# MKRFOX1200-LargePrototype.net
KiCad netlist of a schematic drawn in EAGLE
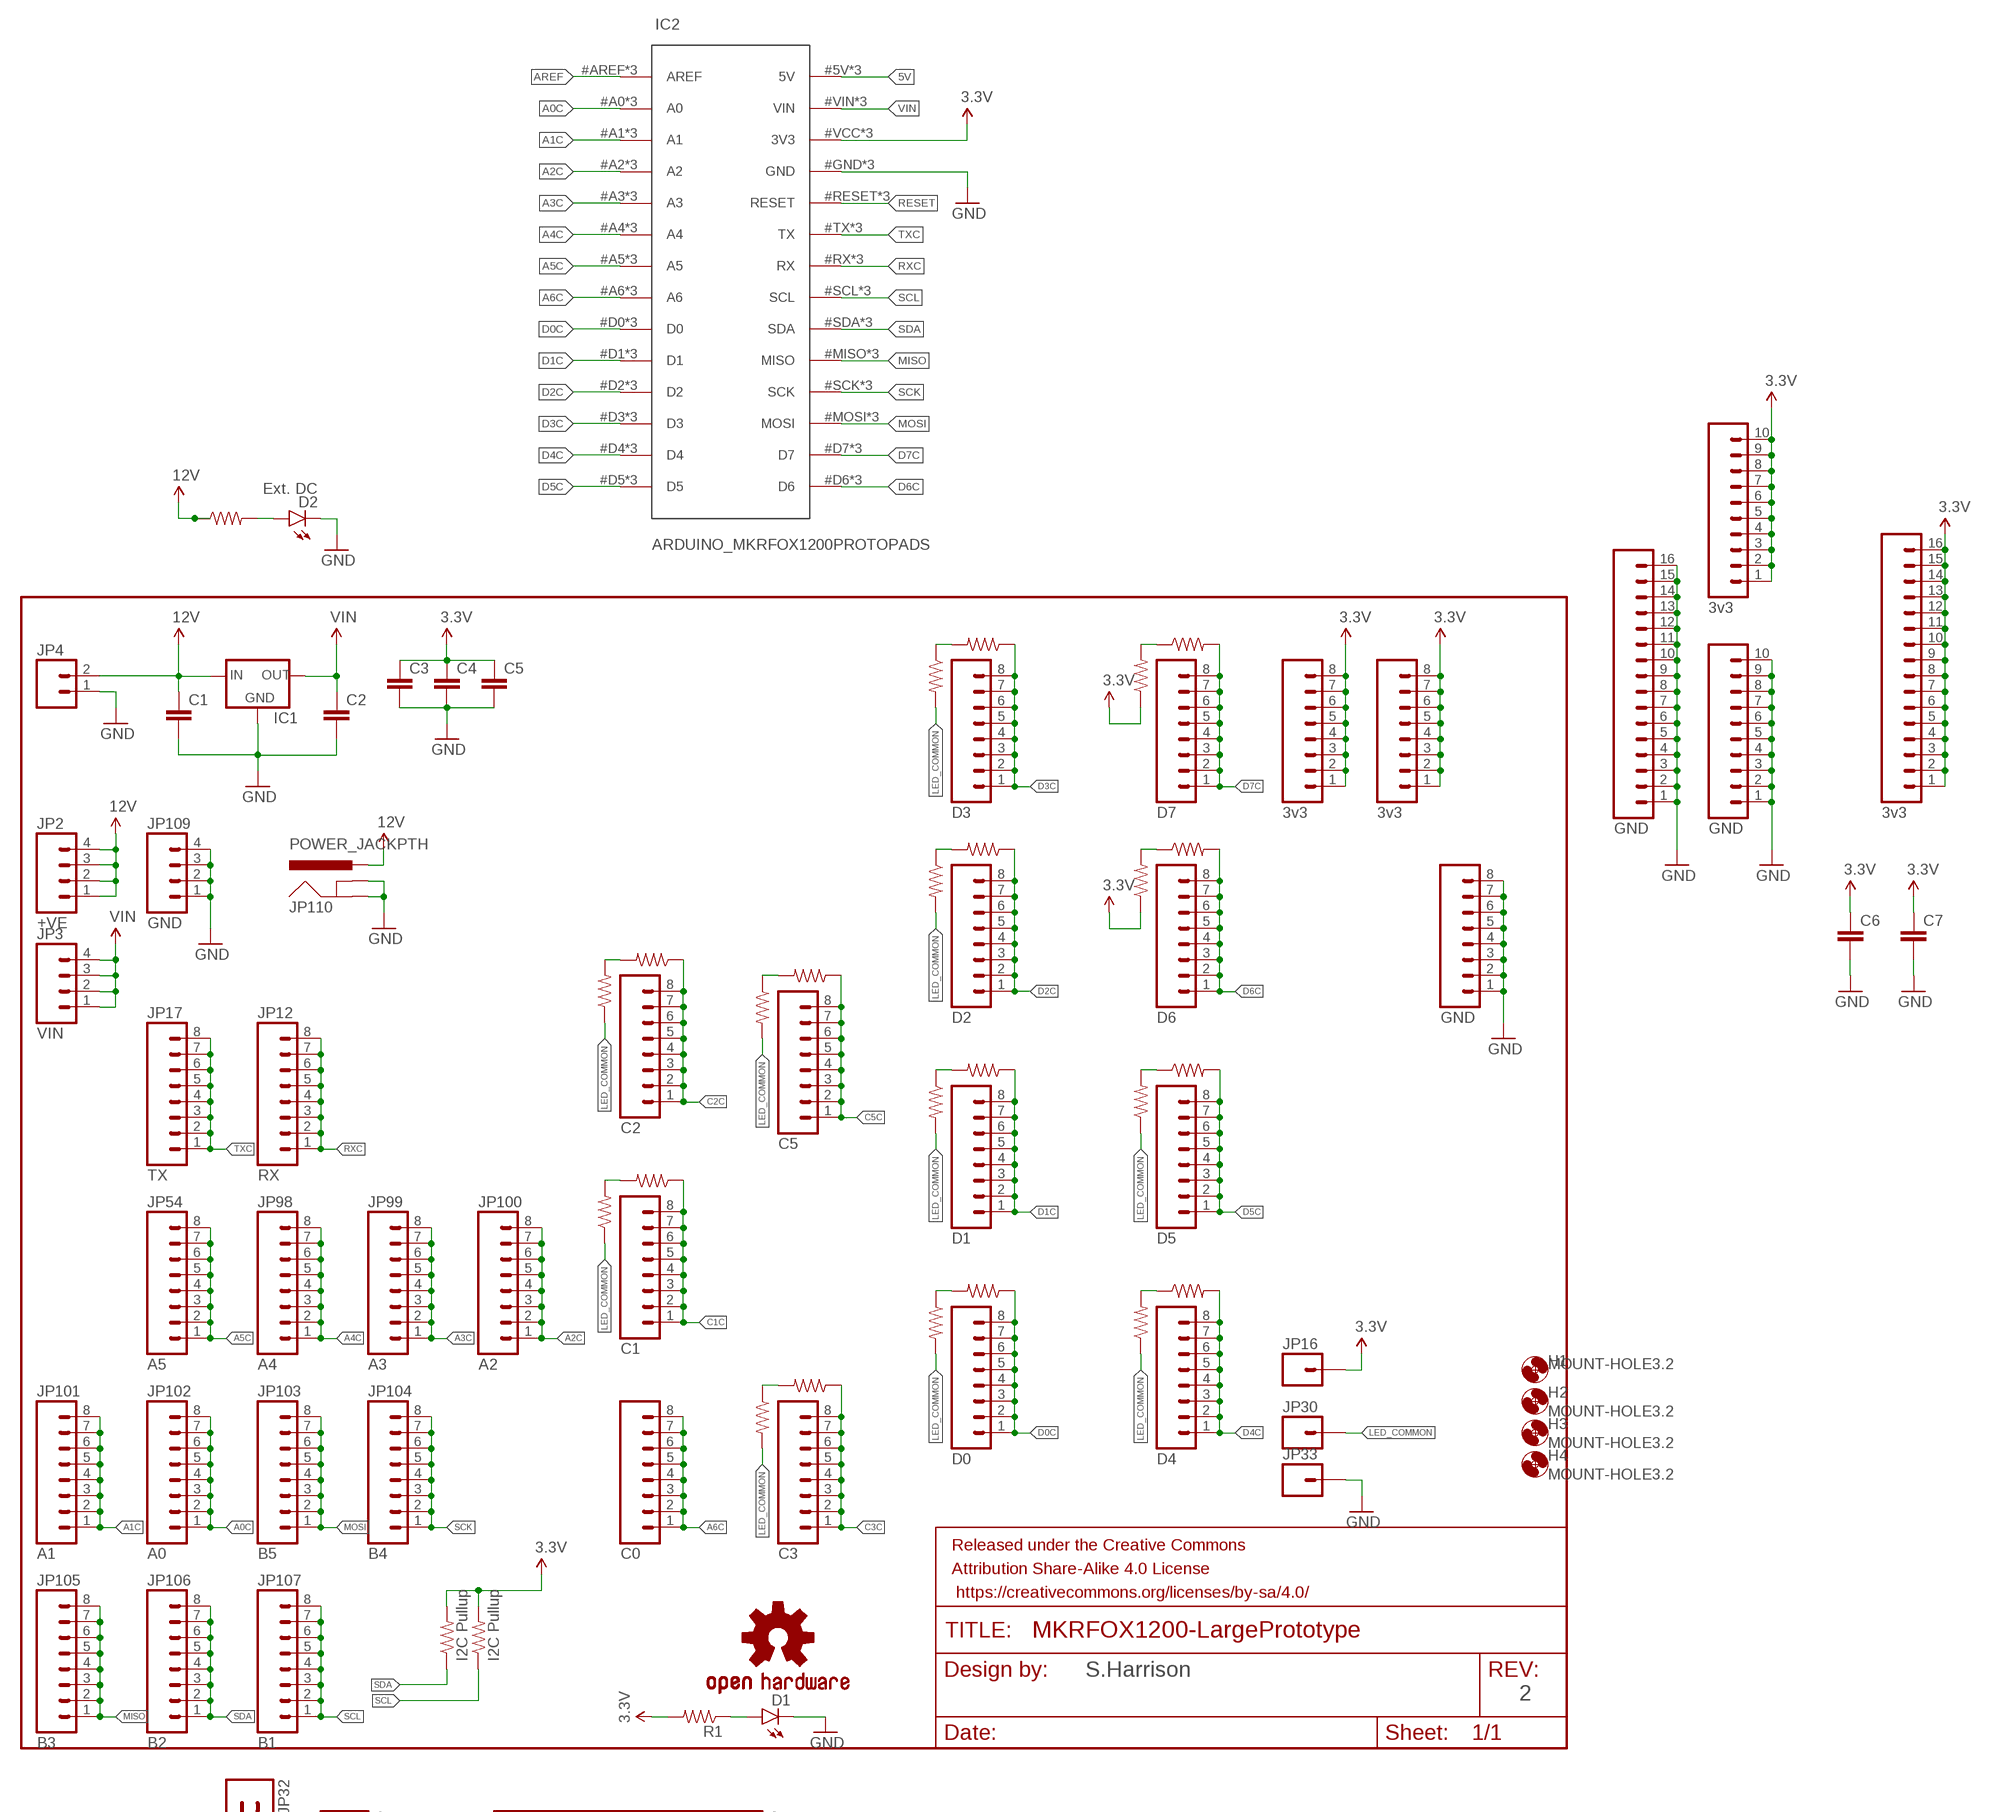
[diagram p0: schematic, sheet 1, part 1 of 2]
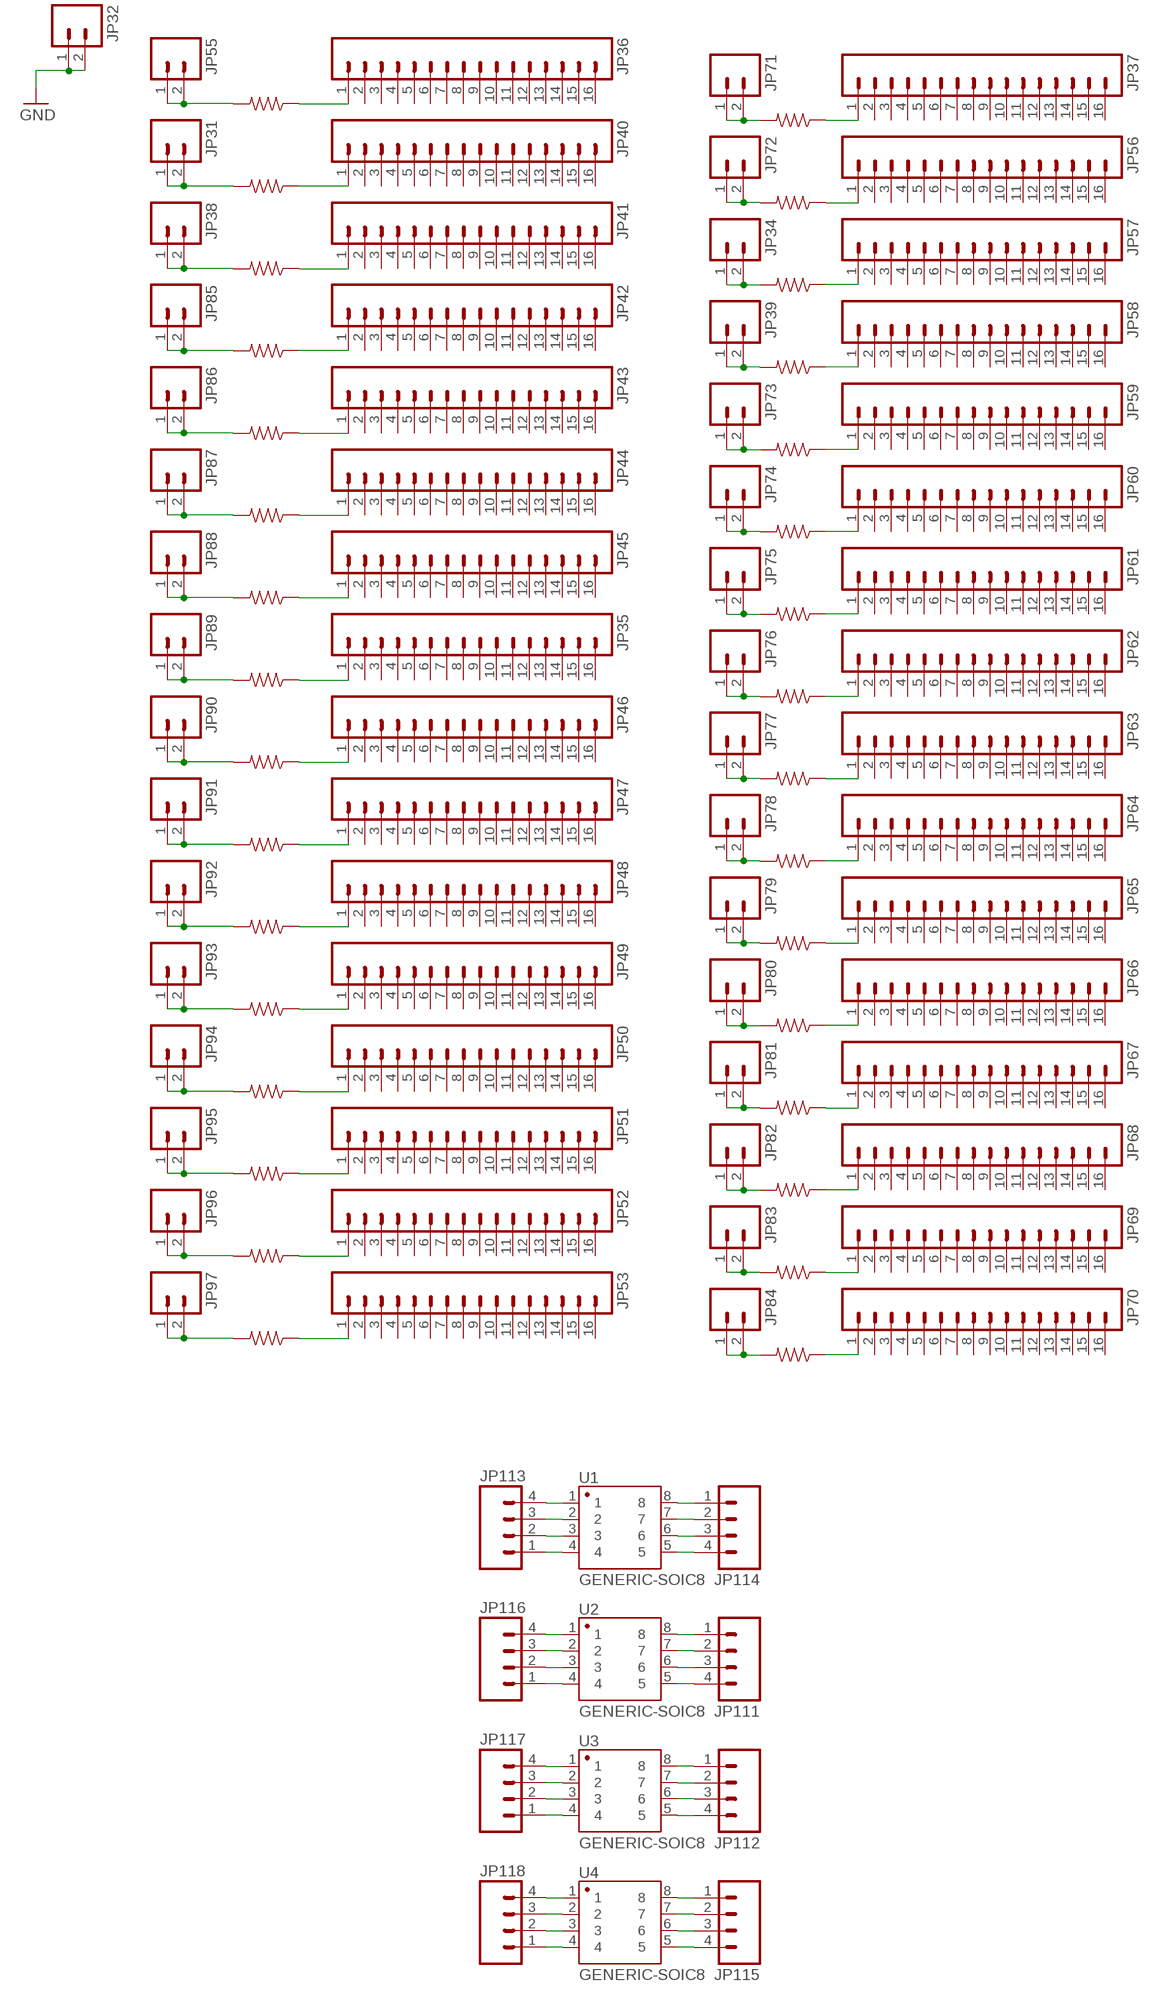
[diagram p1: schematic, sheet 1, part 2 of 2]

(export (version "E")
  (design (tool "Eeschema 10.0.6"))
  (components
    (comp (ref "3V1")
      (value "3v3")
      (footprint "eagle-import:1X08_ROUND")
      (libsource (lib "eagle-import") (part "M08"))
    )
    (comp (ref "3V3")
      (value "3v3")
      (footprint "eagle-import:1X08_ROUND")
      (libsource (lib "eagle-import") (part "M08"))
    )
    (comp (ref "C1")
      (value "1UF-25V-10%(0805)\"")
      (footprint "eagle-import:0805-CAP")
      (libsource (lib "eagle-import") (part "1UF-25V-10%(0805){dblquote}"))
    )
    (comp (ref "C2")
      (value "1UF-25V-10%(0805)\"")
      (footprint "eagle-import:0805-CAP")
      (libsource (lib "eagle-import") (part "1UF-25V-10%(0805){dblquote}"))
    )
    (comp (ref "C3")
      (value "1UF-25V-10%(0805)\"")
      (footprint "eagle-import:0805-CAP")
      (libsource (lib "eagle-import") (part "1UF-25V-10%(0805){dblquote}"))
    )
    (comp (ref "C4")
      (value "1UF-25V-10%(0805)\"")
      (footprint "eagle-import:0805-CAP")
      (libsource (lib "eagle-import") (part "1UF-25V-10%(0805){dblquote}"))
    )
    (comp (ref "C5")
      (value "1UF-25V-10%(0805)\"")
      (footprint "eagle-import:0805-CAP")
      (libsource (lib "eagle-import") (part "1UF-25V-10%(0805){dblquote}"))
    )
    (comp (ref "C6")
      (value "1UF-25V-10%(0805)\"")
      (footprint "eagle-import:0805-CAP")
      (libsource (lib "eagle-import") (part "1UF-25V-10%(0805){dblquote}"))
    )
    (comp (ref "C7")
      (value "1UF-25V-10%(0805)\"")
      (footprint "eagle-import:0805-CAP")
      (libsource (lib "eagle-import") (part "1UF-25V-10%(0805){dblquote}"))
    )
    (comp (ref "D1")
      (value "LED1206-BOTTOM")
      (footprint "eagle-import:LED-1206-BOTTOM")
      (libsource (lib "eagle-import") (part "LED1206-BOTTOM"))
    )
    (comp (ref "D2")
      (value "Ext. DC")
      (footprint "eagle-import:LED-1206")
      (libsource (lib "eagle-import") (part "LED-RED1206"))
    )
    (comp (ref "FRAME1")
      (value "FRAME-LETTER")
      (footprint "eagle-import:CREATIVE_COMMONS")
      (libsource (lib "eagle-import") (part "FRAME-LETTER"))
    )
    (comp (ref "H1")
      (value "MOUNT-HOLE3.2")
      (footprint "eagle-import:3,2")
      (libsource (lib "eagle-import") (part "MOUNT-HOLE3.2"))
    )
    (comp (ref "H2")
      (value "MOUNT-HOLE3.2")
      (footprint "eagle-import:3,2")
      (libsource (lib "eagle-import") (part "MOUNT-HOLE3.2"))
    )
    (comp (ref "H3")
      (value "MOUNT-HOLE3.2")
      (footprint "eagle-import:3,2")
      (libsource (lib "eagle-import") (part "MOUNT-HOLE3.2"))
    )
    (comp (ref "H4")
      (value "MOUNT-HOLE3.2")
      (footprint "eagle-import:3,2")
      (libsource (lib "eagle-import") (part "MOUNT-HOLE3.2"))
    )
    (comp (ref "IC1")
      (value "78XXS")
      (footprint "eagle-import:78XXS")
      (libsource (lib "eagle-import") (part "78XXS"))
    )
    (comp (ref "IC2")
      (value "ARDUINO_MKRFOX1200PROTOPADS")
      (footprint "eagle-import:ARDUINO_MKRFOX1200_PROTOPADS")
      (libsource (lib "eagle-import") (part "ARDUINO_MKRFOX1200PROTOPADS"))
    )
    (comp (ref "JP1")
      (value "D7")
      (footprint "eagle-import:1X08_ROUND")
      (libsource (lib "eagle-import") (part "M08"))
    )
    (comp (ref "JP2")
      (value "+VE")
      (footprint "eagle-import:1X04")
      (libsource (lib "eagle-import") (part "M04PTH"))
    )
    (comp (ref "JP3")
      (value "VIN")
      (footprint "eagle-import:1X04")
      (libsource (lib "eagle-import") (part "M04PTH"))
    )
    (comp (ref "JP4")
      (value "M025MM")
      (footprint "eagle-import:SCREWTERMINAL-5MM-2")
      (libsource (lib "eagle-import") (part "M025MM"))
    )
    (comp (ref "JP5")
      (value "3v3")
      (footprint "eagle-import:1X10")
      (libsource (lib "eagle-import") (part "M10SILK_FEMALE_PTH"))
    )
    (comp (ref "JP7")
      (value "D6")
      (footprint "eagle-import:1X08_ROUND")
      (libsource (lib "eagle-import") (part "M08"))
    )
    (comp (ref "JP10")
      (value "D5")
      (footprint "eagle-import:1X08_ROUND")
      (libsource (lib "eagle-import") (part "M08"))
    )
    (comp (ref "JP11")
      (value "GND")
      (footprint "eagle-import:1X10")
      (libsource (lib "eagle-import") (part "M10SILK_FEMALE_PTH"))
    )
    (comp (ref "JP12")
      (value "RX")
      (footprint "eagle-import:1X08_ROUND")
      (libsource (lib "eagle-import") (part "M08"))
    )
    (comp (ref "JP13")
      (value "3v3")
      (footprint "eagle-import:1X16")
      (libsource (lib "eagle-import") (part "M16PTH"))
    )
    (comp (ref "JP14")
      (value "GND")
      (footprint "eagle-import:1X16")
      (libsource (lib "eagle-import") (part "M16PTH"))
    )
    (comp (ref "JP16")
      (value "M01PTH")
      (footprint "eagle-import:1X01")
      (libsource (lib "eagle-import") (part "M01PTH"))
    )
    (comp (ref "JP17")
      (value "TX")
      (footprint "eagle-import:1X08_ROUND")
      (libsource (lib "eagle-import") (part "M08"))
    )
    (comp (ref "JP18")
      (value "D4")
      (footprint "eagle-import:1X08_ROUND")
      (libsource (lib "eagle-import") (part "M08"))
    )
    (comp (ref "JP19")
      (value "D3")
      (footprint "eagle-import:1X08_ROUND")
      (libsource (lib "eagle-import") (part "M08"))
    )
    (comp (ref "JP20")
      (value "D2")
      (footprint "eagle-import:1X08_ROUND")
      (libsource (lib "eagle-import") (part "M08"))
    )
    (comp (ref "JP21")
      (value "D1")
      (footprint "eagle-import:1X08_ROUND")
      (libsource (lib "eagle-import") (part "M08"))
    )
    (comp (ref "JP22")
      (value "D0")
      (footprint "eagle-import:1X08_ROUND")
      (libsource (lib "eagle-import") (part "M08"))
    )
    (comp (ref "JP23")
      (value "GND")
      (footprint "eagle-import:1X08_ROUND")
      (libsource (lib "eagle-import") (part "M08"))
    )
    (comp (ref "JP24")
      (value "C5")
      (footprint "eagle-import:1X08_ROUND")
      (libsource (lib "eagle-import") (part "M08"))
    )
    (comp (ref "JP26")
      (value "C3")
      (footprint "eagle-import:1X08_ROUND")
      (libsource (lib "eagle-import") (part "M08"))
    )
    (comp (ref "JP27")
      (value "C2")
      (footprint "eagle-import:1X08_ROUND")
      (libsource (lib "eagle-import") (part "M08"))
    )
    (comp (ref "JP28")
      (value "C1")
      (footprint "eagle-import:1X08_ROUND")
      (libsource (lib "eagle-import") (part "M08"))
    )
    (comp (ref "JP29")
      (value "C0")
      (footprint "eagle-import:1X08_ROUND")
      (libsource (lib "eagle-import") (part "M08"))
    )
    (comp (ref "JP30")
      (value "M01PTH")
      (footprint "eagle-import:1X01")
      (libsource (lib "eagle-import") (part "M01PTH"))
    )
    (comp (ref "JP31")
      (value "M02PTH")
      (footprint "eagle-import:1X02")
      (libsource (lib "eagle-import") (part "M02PTH"))
    )
    (comp (ref "JP32")
      (value "M02PTH")
      (footprint "eagle-import:1X02")
      (libsource (lib "eagle-import") (part "M02PTH"))
    )
    (comp (ref "JP33")
      (value "M01PTH")
      (footprint "eagle-import:1X01")
      (libsource (lib "eagle-import") (part "M01PTH"))
    )
    (comp (ref "JP34")
      (value "M02PTH")
      (footprint "eagle-import:1X02")
      (libsource (lib "eagle-import") (part "M02PTH"))
    )
    (comp (ref "JP35")
      (value "M161X16_NO_SILK")
      (footprint "eagle-import:1X16_NO_SILK")
      (libsource (lib "eagle-import") (part "M161X16_NO_SILK"))
    )
    (comp (ref "JP36")
      (value "M161X16_NO_SILK")
      (footprint "eagle-import:1X16_NO_SILK")
      (libsource (lib "eagle-import") (part "M161X16_NO_SILK"))
    )
    (comp (ref "JP37")
      (value "M161X16_NO_SILK")
      (footprint "eagle-import:1X16_NO_SILK")
      (libsource (lib "eagle-import") (part "M161X16_NO_SILK"))
    )
    (comp (ref "JP38")
      (value "M02PTH")
      (footprint "eagle-import:1X02")
      (libsource (lib "eagle-import") (part "M02PTH"))
    )
    (comp (ref "JP39")
      (value "M02PTH")
      (footprint "eagle-import:1X02")
      (libsource (lib "eagle-import") (part "M02PTH"))
    )
    (comp (ref "JP40")
      (value "M161X16_NO_SILK")
      (footprint "eagle-import:1X16_NO_SILK")
      (libsource (lib "eagle-import") (part "M161X16_NO_SILK"))
    )
    (comp (ref "JP41")
      (value "M161X16_NO_SILK")
      (footprint "eagle-import:1X16_NO_SILK")
      (libsource (lib "eagle-import") (part "M161X16_NO_SILK"))
    )
    (comp (ref "JP42")
      (value "M161X16_NO_SILK")
      (footprint "eagle-import:1X16_NO_SILK")
      (libsource (lib "eagle-import") (part "M161X16_NO_SILK"))
    )
    (comp (ref "JP43")
      (value "M161X16_NO_SILK")
      (footprint "eagle-import:1X16_NO_SILK")
      (libsource (lib "eagle-import") (part "M161X16_NO_SILK"))
    )
    (comp (ref "JP44")
      (value "M161X16_NO_SILK")
      (footprint "eagle-import:1X16_NO_SILK")
      (libsource (lib "eagle-import") (part "M161X16_NO_SILK"))
    )
    (comp (ref "JP45")
      (value "M161X16_NO_SILK")
      (footprint "eagle-import:1X16_NO_SILK")
      (libsource (lib "eagle-import") (part "M161X16_NO_SILK"))
    )
    (comp (ref "JP46")
      (value "M161X16_NO_SILK")
      (footprint "eagle-import:1X16_NO_SILK")
      (libsource (lib "eagle-import") (part "M161X16_NO_SILK"))
    )
    (comp (ref "JP47")
      (value "M161X16_NO_SILK")
      (footprint "eagle-import:1X16_NO_SILK")
      (libsource (lib "eagle-import") (part "M161X16_NO_SILK"))
    )
    (comp (ref "JP48")
      (value "M161X16_NO_SILK")
      (footprint "eagle-import:1X16_NO_SILK")
      (libsource (lib "eagle-import") (part "M161X16_NO_SILK"))
    )
    (comp (ref "JP49")
      (value "M161X16_NO_SILK")
      (footprint "eagle-import:1X16_NO_SILK")
      (libsource (lib "eagle-import") (part "M161X16_NO_SILK"))
    )
    (comp (ref "JP50")
      (value "M161X16_NO_SILK")
      (footprint "eagle-import:1X16_NO_SILK")
      (libsource (lib "eagle-import") (part "M161X16_NO_SILK"))
    )
    (comp (ref "JP51")
      (value "M161X16_NO_SILK")
      (footprint "eagle-import:1X16_NO_SILK")
      (libsource (lib "eagle-import") (part "M161X16_NO_SILK"))
    )
    (comp (ref "JP52")
      (value "M161X16_NO_SILK")
      (footprint "eagle-import:1X16_NO_SILK")
      (libsource (lib "eagle-import") (part "M161X16_NO_SILK"))
    )
    (comp (ref "JP53")
      (value "M161X16_NO_SILK")
      (footprint "eagle-import:1X16_NO_SILK")
      (libsource (lib "eagle-import") (part "M161X16_NO_SILK"))
    )
    (comp (ref "JP54")
      (value "A5")
      (footprint "eagle-import:1X08_ROUND")
      (libsource (lib "eagle-import") (part "M08"))
    )
    (comp (ref "JP55")
      (value "M02PTH")
      (footprint "eagle-import:1X02")
      (libsource (lib "eagle-import") (part "M02PTH"))
    )
    (comp (ref "JP56")
      (value "M161X16_NO_SILK")
      (footprint "eagle-import:1X16_NO_SILK")
      (libsource (lib "eagle-import") (part "M161X16_NO_SILK"))
    )
    (comp (ref "JP57")
      (value "M161X16_NO_SILK")
      (footprint "eagle-import:1X16_NO_SILK")
      (libsource (lib "eagle-import") (part "M161X16_NO_SILK"))
    )
    (comp (ref "JP58")
      (value "M161X16_NO_SILK")
      (footprint "eagle-import:1X16_NO_SILK")
      (libsource (lib "eagle-import") (part "M161X16_NO_SILK"))
    )
    (comp (ref "JP59")
      (value "M161X16_NO_SILK")
      (footprint "eagle-import:1X16_NO_SILK")
      (libsource (lib "eagle-import") (part "M161X16_NO_SILK"))
    )
    (comp (ref "JP60")
      (value "M161X16_NO_SILK")
      (footprint "eagle-import:1X16_NO_SILK")
      (libsource (lib "eagle-import") (part "M161X16_NO_SILK"))
    )
    (comp (ref "JP61")
      (value "M161X16_NO_SILK")
      (footprint "eagle-import:1X16_NO_SILK")
      (libsource (lib "eagle-import") (part "M161X16_NO_SILK"))
    )
    (comp (ref "JP62")
      (value "M161X16_NO_SILK")
      (footprint "eagle-import:1X16_NO_SILK")
      (libsource (lib "eagle-import") (part "M161X16_NO_SILK"))
    )
    (comp (ref "JP63")
      (value "M161X16_NO_SILK")
      (footprint "eagle-import:1X16_NO_SILK")
      (libsource (lib "eagle-import") (part "M161X16_NO_SILK"))
    )
    (comp (ref "JP64")
      (value "M161X16_NO_SILK")
      (footprint "eagle-import:1X16_NO_SILK")
      (libsource (lib "eagle-import") (part "M161X16_NO_SILK"))
    )
    (comp (ref "JP65")
      (value "M161X16_NO_SILK")
      (footprint "eagle-import:1X16_NO_SILK")
      (libsource (lib "eagle-import") (part "M161X16_NO_SILK"))
    )
    (comp (ref "JP66")
      (value "M161X16_NO_SILK")
      (footprint "eagle-import:1X16_NO_SILK")
      (libsource (lib "eagle-import") (part "M161X16_NO_SILK"))
    )
    (comp (ref "JP67")
      (value "M161X16_NO_SILK")
      (footprint "eagle-import:1X16_NO_SILK")
      (libsource (lib "eagle-import") (part "M161X16_NO_SILK"))
    )
    (comp (ref "JP68")
      (value "M161X16_NO_SILK")
      (footprint "eagle-import:1X16_NO_SILK")
      (libsource (lib "eagle-import") (part "M161X16_NO_SILK"))
    )
    (comp (ref "JP69")
      (value "M161X16_NO_SILK")
      (footprint "eagle-import:1X16_NO_SILK")
      (libsource (lib "eagle-import") (part "M161X16_NO_SILK"))
    )
    (comp (ref "JP70")
      (value "M161X16_NO_SILK")
      (footprint "eagle-import:1X16_NO_SILK")
      (libsource (lib "eagle-import") (part "M161X16_NO_SILK"))
    )
    (comp (ref "JP71")
      (value "M02PTH")
      (footprint "eagle-import:1X02")
      (libsource (lib "eagle-import") (part "M02PTH"))
    )
    (comp (ref "JP72")
      (value "M02PTH")
      (footprint "eagle-import:1X02")
      (libsource (lib "eagle-import") (part "M02PTH"))
    )
    (comp (ref "JP73")
      (value "M02PTH")
      (footprint "eagle-import:1X02")
      (libsource (lib "eagle-import") (part "M02PTH"))
    )
    (comp (ref "JP74")
      (value "M02PTH")
      (footprint "eagle-import:1X02")
      (libsource (lib "eagle-import") (part "M02PTH"))
    )
    (comp (ref "JP75")
      (value "M02PTH")
      (footprint "eagle-import:1X02")
      (libsource (lib "eagle-import") (part "M02PTH"))
    )
    (comp (ref "JP76")
      (value "M02PTH")
      (footprint "eagle-import:1X02")
      (libsource (lib "eagle-import") (part "M02PTH"))
    )
    (comp (ref "JP77")
      (value "M02PTH")
      (footprint "eagle-import:1X02")
      (libsource (lib "eagle-import") (part "M02PTH"))
    )
    (comp (ref "JP78")
      (value "M02PTH")
      (footprint "eagle-import:1X02")
      (libsource (lib "eagle-import") (part "M02PTH"))
    )
    (comp (ref "JP79")
      (value "M02PTH")
      (footprint "eagle-import:1X02")
      (libsource (lib "eagle-import") (part "M02PTH"))
    )
    (comp (ref "JP80")
      (value "M02PTH")
      (footprint "eagle-import:1X02")
      (libsource (lib "eagle-import") (part "M02PTH"))
    )
    (comp (ref "JP81")
      (value "M02PTH")
      (footprint "eagle-import:1X02")
      (libsource (lib "eagle-import") (part "M02PTH"))
    )
    (comp (ref "JP82")
      (value "M02PTH")
      (footprint "eagle-import:1X02")
      (libsource (lib "eagle-import") (part "M02PTH"))
    )
    (comp (ref "JP83")
      (value "M02PTH")
      (footprint "eagle-import:1X02")
      (libsource (lib "eagle-import") (part "M02PTH"))
    )
    (comp (ref "JP84")
      (value "M02PTH")
      (footprint "eagle-import:1X02")
      (libsource (lib "eagle-import") (part "M02PTH"))
    )
    (comp (ref "JP85")
      (value "M02PTH")
      (footprint "eagle-import:1X02")
      (libsource (lib "eagle-import") (part "M02PTH"))
    )
    (comp (ref "JP86")
      (value "M02PTH")
      (footprint "eagle-import:1X02")
      (libsource (lib "eagle-import") (part "M02PTH"))
    )
    (comp (ref "JP87")
      (value "M02PTH")
      (footprint "eagle-import:1X02")
      (libsource (lib "eagle-import") (part "M02PTH"))
    )
    (comp (ref "JP88")
      (value "M02PTH")
      (footprint "eagle-import:1X02")
      (libsource (lib "eagle-import") (part "M02PTH"))
    )
    (comp (ref "JP89")
      (value "M02PTH")
      (footprint "eagle-import:1X02")
      (libsource (lib "eagle-import") (part "M02PTH"))
    )
    (comp (ref "JP90")
      (value "M02PTH")
      (footprint "eagle-import:1X02")
      (libsource (lib "eagle-import") (part "M02PTH"))
    )
    (comp (ref "JP91")
      (value "M02PTH")
      (footprint "eagle-import:1X02")
      (libsource (lib "eagle-import") (part "M02PTH"))
    )
    (comp (ref "JP92")
      (value "M02PTH")
      (footprint "eagle-import:1X02")
      (libsource (lib "eagle-import") (part "M02PTH"))
    )
    (comp (ref "JP93")
      (value "M02PTH")
      (footprint "eagle-import:1X02")
      (libsource (lib "eagle-import") (part "M02PTH"))
    )
    (comp (ref "JP94")
      (value "M02PTH")
      (footprint "eagle-import:1X02")
      (libsource (lib "eagle-import") (part "M02PTH"))
    )
    (comp (ref "JP95")
      (value "M02PTH")
      (footprint "eagle-import:1X02")
      (libsource (lib "eagle-import") (part "M02PTH"))
    )
    (comp (ref "JP96")
      (value "M02PTH")
      (footprint "eagle-import:1X02")
      (libsource (lib "eagle-import") (part "M02PTH"))
    )
    (comp (ref "JP97")
      (value "M02PTH")
      (footprint "eagle-import:1X02")
      (libsource (lib "eagle-import") (part "M02PTH"))
    )
    (comp (ref "JP98")
      (value "A4")
      (footprint "eagle-import:1X08_ROUND")
      (libsource (lib "eagle-import") (part "M08"))
    )
    (comp (ref "JP99")
      (value "A3")
      (footprint "eagle-import:1X08_ROUND")
      (libsource (lib "eagle-import") (part "M08"))
    )
    (comp (ref "JP100")
      (value "A2")
      (footprint "eagle-import:1X08_ROUND")
      (libsource (lib "eagle-import") (part "M08"))
    )
    (comp (ref "JP101")
      (value "A1")
      (footprint "eagle-import:1X08_ROUND")
      (libsource (lib "eagle-import") (part "M08"))
    )
    (comp (ref "JP102")
      (value "A0")
      (footprint "eagle-import:1X08_ROUND")
      (libsource (lib "eagle-import") (part "M08"))
    )
    (comp (ref "JP103")
      (value "B5")
      (footprint "eagle-import:1X08_ROUND")
      (libsource (lib "eagle-import") (part "M08"))
    )
    (comp (ref "JP104")
      (value "B4")
      (footprint "eagle-import:1X08_ROUND")
      (libsource (lib "eagle-import") (part "M08"))
    )
    (comp (ref "JP105")
      (value "B3")
      (footprint "eagle-import:1X08_ROUND")
      (libsource (lib "eagle-import") (part "M08"))
    )
    (comp (ref "JP106")
      (value "B2")
      (footprint "eagle-import:1X08_ROUND")
      (libsource (lib "eagle-import") (part "M08"))
    )
    (comp (ref "JP107")
      (value "B1")
      (footprint "eagle-import:1X08_ROUND")
      (libsource (lib "eagle-import") (part "M08"))
    )
    (comp (ref "JP109")
      (value "GND")
      (footprint "eagle-import:1X04")
      (libsource (lib "eagle-import") (part "M04PTH"))
    )
    (comp (ref "JP110")
      (value "POWER_JACKPTH")
      (footprint "eagle-import:POWER_JACK_PTH")
      (libsource (lib "eagle-import") (part "POWER_JACKPTH"))
    )
    (comp (ref "JP111")
      (value "M04NO_SILK_ALL_ROUND")
      (footprint "eagle-import:1X04_NO_SILK_ALL_ROUND")
      (libsource (lib "eagle-import") (part "M04NO_SILK_ALL_ROUND"))
    )
    (comp (ref "JP112")
      (value "M04NO_SILK_ALL_ROUND")
      (footprint "eagle-import:1X04_NO_SILK_ALL_ROUND")
      (libsource (lib "eagle-import") (part "M04NO_SILK_ALL_ROUND"))
    )
    (comp (ref "JP113")
      (value "M04NO_SILK_ALL_ROUND")
      (footprint "eagle-import:1X04_NO_SILK_ALL_ROUND")
      (libsource (lib "eagle-import") (part "M04NO_SILK_ALL_ROUND"))
    )
    (comp (ref "JP114")
      (value "M04NO_SILK_ALL_ROUND")
      (footprint "eagle-import:1X04_NO_SILK_ALL_ROUND")
      (libsource (lib "eagle-import") (part "M04NO_SILK_ALL_ROUND"))
    )
    (comp (ref "JP115")
      (value "M04NO_SILK_ALL_ROUND")
      (footprint "eagle-import:1X04_NO_SILK_ALL_ROUND")
      (libsource (lib "eagle-import") (part "M04NO_SILK_ALL_ROUND"))
    )
    (comp (ref "JP116")
      (value "M04NO_SILK_ALL_ROUND")
      (footprint "eagle-import:1X04_NO_SILK_ALL_ROUND")
      (libsource (lib "eagle-import") (part "M04NO_SILK_ALL_ROUND"))
    )
    (comp (ref "JP117")
      (value "M04NO_SILK_ALL_ROUND")
      (footprint "eagle-import:1X04_NO_SILK_ALL_ROUND")
      (libsource (lib "eagle-import") (part "M04NO_SILK_ALL_ROUND"))
    )
    (comp (ref "JP118")
      (value "M04NO_SILK_ALL_ROUND")
      (footprint "eagle-import:1X04_NO_SILK_ALL_ROUND")
      (libsource (lib "eagle-import") (part "M04NO_SILK_ALL_ROUND"))
    )
    (comp (ref "LOGO3")
      (value "OSHW-LOGOM")
      (footprint "eagle-import:OSHW-LOGO-M")
      (libsource (lib "eagle-import") (part "OSHW-LOGOM"))
    )
    (comp (ref "R1")
      (value "RESISTOR1206")
      (footprint "eagle-import:1206")
      (libsource (lib "eagle-import") (part "RESISTOR1206"))
    )
    (comp (ref "R2")
      (value "RESISTOR1206")
      (footprint "eagle-import:1206")
      (libsource (lib "eagle-import") (part "RESISTOR1206"))
    )
    (comp (ref "R3")
      (value "RESISTOR1206")
      (footprint "eagle-import:1206")
      (libsource (lib "eagle-import") (part "RESISTOR1206"))
    )
    (comp (ref "R4")
      (value "RESISTOR1206")
      (footprint "eagle-import:1206")
      (libsource (lib "eagle-import") (part "RESISTOR1206"))
    )
    (comp (ref "R5")
      (value "RESISTOR1206")
      (footprint "eagle-import:1206")
      (libsource (lib "eagle-import") (part "RESISTOR1206"))
    )
    (comp (ref "R6")
      (value "RESISTOR1206")
      (footprint "eagle-import:1206")
      (libsource (lib "eagle-import") (part "RESISTOR1206"))
    )
    (comp (ref "R7")
      (value "RESISTOR1206")
      (footprint "eagle-import:1206")
      (libsource (lib "eagle-import") (part "RESISTOR1206"))
    )
    (comp (ref "R8")
      (value "RESISTOR1206")
      (footprint "eagle-import:1206")
      (libsource (lib "eagle-import") (part "RESISTOR1206"))
    )
    (comp (ref "R9")
      (value "RESISTOR1206")
      (footprint "eagle-import:1206")
      (libsource (lib "eagle-import") (part "RESISTOR1206"))
    )
    (comp (ref "R10")
      (value "RESISTOR1206")
      (footprint "eagle-import:1206")
      (libsource (lib "eagle-import") (part "RESISTOR1206"))
    )
    (comp (ref "R11")
      (value "RESISTOR1206")
      (footprint "eagle-import:1206")
      (libsource (lib "eagle-import") (part "RESISTOR1206"))
    )
    (comp (ref "R12")
      (value "RESISTOR1206")
      (footprint "eagle-import:1206")
      (libsource (lib "eagle-import") (part "RESISTOR1206"))
    )
    (comp (ref "R13")
      (value "RESISTOR1206")
      (footprint "eagle-import:1206")
      (libsource (lib "eagle-import") (part "RESISTOR1206"))
    )
    (comp (ref "R14")
      (value "RESISTOR1206")
      (footprint "eagle-import:1206")
      (libsource (lib "eagle-import") (part "RESISTOR1206"))
    )
    (comp (ref "R15")
      (value "RESISTOR1206")
      (footprint "eagle-import:1206")
      (libsource (lib "eagle-import") (part "RESISTOR1206"))
    )
    (comp (ref "R16")
      (value "RESISTOR1206")
      (footprint "eagle-import:1206")
      (libsource (lib "eagle-import") (part "RESISTOR1206"))
    )
    (comp (ref "R17")
      (value "RESISTOR1206")
      (footprint "eagle-import:1206")
      (libsource (lib "eagle-import") (part "RESISTOR1206"))
    )
    (comp (ref "R18")
      (value "RESISTOR1206")
      (footprint "eagle-import:1206")
      (libsource (lib "eagle-import") (part "RESISTOR1206"))
    )
    (comp (ref "R19")
      (value "RESISTOR1206")
      (footprint "eagle-import:1206")
      (libsource (lib "eagle-import") (part "RESISTOR1206"))
    )
    (comp (ref "R22")
      (value "RESISTOR1206")
      (footprint "eagle-import:1206")
      (libsource (lib "eagle-import") (part "RESISTOR1206"))
    )
    (comp (ref "R23")
      (value "RESISTOR1206")
      (footprint "eagle-import:1206")
      (libsource (lib "eagle-import") (part "RESISTOR1206"))
    )
    (comp (ref "R24")
      (value "RESISTOR1206")
      (footprint "eagle-import:1206")
      (libsource (lib "eagle-import") (part "RESISTOR1206"))
    )
    (comp (ref "R25")
      (value "RESISTOR1206")
      (footprint "eagle-import:1206")
      (libsource (lib "eagle-import") (part "RESISTOR1206"))
    )
    (comp (ref "R26")
      (value "RESISTOR1206")
      (footprint "eagle-import:1206")
      (libsource (lib "eagle-import") (part "RESISTOR1206"))
    )
    (comp (ref "R27")
      (value "RESISTOR1206")
      (footprint "eagle-import:1206")
      (libsource (lib "eagle-import") (part "RESISTOR1206"))
    )
    (comp (ref "R28")
      (value "RESISTOR1206")
      (footprint "eagle-import:1206")
      (libsource (lib "eagle-import") (part "RESISTOR1206"))
    )
    (comp (ref "R30")
      (value "RESISTOR1206")
      (footprint "eagle-import:1206")
      (libsource (lib "eagle-import") (part "RESISTOR1206"))
    )
    (comp (ref "R31")
      (value "RESISTOR1206")
      (footprint "eagle-import:1206")
      (libsource (lib "eagle-import") (part "RESISTOR1206"))
    )
    (comp (ref "R32")
      (value "RESISTOR1206")
      (footprint "eagle-import:1206")
      (libsource (lib "eagle-import") (part "RESISTOR1206"))
    )
    (comp (ref "R33")
      (value "RESISTOR1206")
      (footprint "eagle-import:1206")
      (libsource (lib "eagle-import") (part "RESISTOR1206"))
    )
    (comp (ref "R34")
      (value "RESISTOR1206")
      (footprint "eagle-import:1206")
      (libsource (lib "eagle-import") (part "RESISTOR1206"))
    )
    (comp (ref "R35")
      (value "RESISTOR1206")
      (footprint "eagle-import:1206")
      (libsource (lib "eagle-import") (part "RESISTOR1206"))
    )
    (comp (ref "R36")
      (value "RESISTOR1206")
      (footprint "eagle-import:1206")
      (libsource (lib "eagle-import") (part "RESISTOR1206"))
    )
    (comp (ref "R37")
      (value "RESISTOR1206")
      (footprint "eagle-import:1206")
      (libsource (lib "eagle-import") (part "RESISTOR1206"))
    )
    (comp (ref "R38")
      (value "RESISTOR1206")
      (footprint "eagle-import:1206")
      (libsource (lib "eagle-import") (part "RESISTOR1206"))
    )
    (comp (ref "R39")
      (value "RESISTOR1206")
      (footprint "eagle-import:1206")
      (libsource (lib "eagle-import") (part "RESISTOR1206"))
    )
    (comp (ref "R40")
      (value "RESISTOR1206")
      (footprint "eagle-import:1206")
      (libsource (lib "eagle-import") (part "RESISTOR1206"))
    )
    (comp (ref "R41")
      (value "RESISTOR1206")
      (footprint "eagle-import:1206")
      (libsource (lib "eagle-import") (part "RESISTOR1206"))
    )
    (comp (ref "R42")
      (value "RESISTOR1206")
      (footprint "eagle-import:1206")
      (libsource (lib "eagle-import") (part "RESISTOR1206"))
    )
    (comp (ref "R43")
      (value "RESISTOR1206")
      (footprint "eagle-import:1206")
      (libsource (lib "eagle-import") (part "RESISTOR1206"))
    )
    (comp (ref "R44")
      (value "RESISTOR1206")
      (footprint "eagle-import:1206")
      (libsource (lib "eagle-import") (part "RESISTOR1206"))
    )
    (comp (ref "R45")
      (value "RESISTOR1206")
      (footprint "eagle-import:1206")
      (libsource (lib "eagle-import") (part "RESISTOR1206"))
    )
    (comp (ref "R46")
      (value "RESISTOR1206")
      (footprint "eagle-import:1206")
      (libsource (lib "eagle-import") (part "RESISTOR1206"))
    )
    (comp (ref "R47")
      (value "RESISTOR1206")
      (footprint "eagle-import:1206")
      (libsource (lib "eagle-import") (part "RESISTOR1206"))
    )
    (comp (ref "R48")
      (value "RESISTOR1206")
      (footprint "eagle-import:1206")
      (libsource (lib "eagle-import") (part "RESISTOR1206"))
    )
    (comp (ref "R49")
      (value "RESISTOR1206")
      (footprint "eagle-import:1206")
      (libsource (lib "eagle-import") (part "RESISTOR1206"))
    )
    (comp (ref "R50")
      (value "RESISTOR1206")
      (footprint "eagle-import:1206")
      (libsource (lib "eagle-import") (part "RESISTOR1206"))
    )
    (comp (ref "R51")
      (value "RESISTOR1206")
      (footprint "eagle-import:1206")
      (libsource (lib "eagle-import") (part "RESISTOR1206"))
    )
    (comp (ref "R52")
      (value "RESISTOR1206")
      (footprint "eagle-import:1206")
      (libsource (lib "eagle-import") (part "RESISTOR1206"))
    )
    (comp (ref "R53")
      (value "RESISTOR1206")
      (footprint "eagle-import:1206")
      (libsource (lib "eagle-import") (part "RESISTOR1206"))
    )
    (comp (ref "R54")
      (value "RESISTOR1206")
      (footprint "eagle-import:1206")
      (libsource (lib "eagle-import") (part "RESISTOR1206"))
    )
    (comp (ref "R55")
      (value "RESISTOR1206")
      (footprint "eagle-import:1206")
      (libsource (lib "eagle-import") (part "RESISTOR1206"))
    )
    (comp (ref "R56")
      (value "RESISTOR1206")
      (footprint "eagle-import:1206")
      (libsource (lib "eagle-import") (part "RESISTOR1206"))
    )
    (comp (ref "R57")
      (value "RESISTOR1206")
      (footprint "eagle-import:1206")
      (libsource (lib "eagle-import") (part "RESISTOR1206"))
    )
    (comp (ref "R58")
      (value "RESISTOR1206")
      (footprint "eagle-import:1206")
      (libsource (lib "eagle-import") (part "RESISTOR1206"))
    )
    (comp (ref "R59")
      (value "RESISTOR1206")
      (footprint "eagle-import:1206")
      (libsource (lib "eagle-import") (part "RESISTOR1206"))
    )
    (comp (ref "R60")
      (value "RESISTOR1206")
      (footprint "eagle-import:1206")
      (libsource (lib "eagle-import") (part "RESISTOR1206"))
    )
    (comp (ref "R61")
      (value "RESISTOR1206")
      (footprint "eagle-import:1206")
      (libsource (lib "eagle-import") (part "RESISTOR1206"))
    )
    (comp (ref "R64")
      (value "I2C Pullup")
      (footprint "eagle-import:1206")
      (libsource (lib "eagle-import") (part "RESISTOR1206"))
    )
    (comp (ref "R65")
      (value "I2C Pullup")
      (footprint "eagle-import:1206")
      (libsource (lib "eagle-import") (part "RESISTOR1206"))
    )
    (comp (ref "U1")
      (value "GENERIC-SOIC8")
      (footprint "eagle-import:SO08-UNIVERSAL")
      (libsource (lib "eagle-import") (part "GENERIC-SOIC8"))
    )
    (comp (ref "U2")
      (value "GENERIC-SOIC8")
      (footprint "eagle-import:SO08-UNIVERSAL")
      (libsource (lib "eagle-import") (part "GENERIC-SOIC8"))
    )
    (comp (ref "U3")
      (value "GENERIC-SOIC8")
      (footprint "eagle-import:SO08-UNIVERSAL")
      (libsource (lib "eagle-import") (part "GENERIC-SOIC8"))
    )
    (comp (ref "U4")
      (value "GENERIC-SOIC8")
      (footprint "eagle-import:SO08-UNIVERSAL")
      (libsource (lib "eagle-import") (part "GENERIC-SOIC8"))
    )
  )
  (nets
    (net (code "1") (name "3.3V") (class "Default")
      (node (ref "3V1") (pin "1") (pinfunction "1_1") (pintype "passive"))
      (node (ref "3V1") (pin "2") (pinfunction "2_2") (pintype "passive"))
      (node (ref "3V1") (pin "3") (pinfunction "3_3") (pintype "passive"))
      (node (ref "3V1") (pin "4") (pinfunction "4_4") (pintype "passive"))
      (node (ref "3V1") (pin "5") (pinfunction "5_5") (pintype "passive"))
      (node (ref "3V1") (pin "6") (pinfunction "6_6") (pintype "passive"))
      (node (ref "3V1") (pin "7") (pinfunction "7_7") (pintype "passive"))
      (node (ref "3V1") (pin "8") (pinfunction "8_8") (pintype "passive"))
      (node (ref "3V3") (pin "1") (pinfunction "1_1") (pintype "passive"))
      (node (ref "3V3") (pin "2") (pinfunction "2_2") (pintype "passive"))
      (node (ref "3V3") (pin "3") (pinfunction "3_3") (pintype "passive"))
      (node (ref "3V3") (pin "4") (pinfunction "4_4") (pintype "passive"))
      (node (ref "3V3") (pin "5") (pinfunction "5_5") (pintype "passive"))
      (node (ref "3V3") (pin "6") (pinfunction "6_6") (pintype "passive"))
      (node (ref "3V3") (pin "7") (pinfunction "7_7") (pintype "passive"))
      (node (ref "3V3") (pin "8") (pinfunction "8_8") (pintype "passive"))
      (node (ref "C3") (pin "1") (pinfunction "1_1") (pintype "passive"))
      (node (ref "C4") (pin "1") (pinfunction "1_1") (pintype "passive"))
      (node (ref "C5") (pin "1") (pinfunction "1_1") (pintype "passive"))
      (node (ref "C6") (pin "1") (pinfunction "1_1") (pintype "passive"))
      (node (ref "C7") (pin "1") (pinfunction "1_1") (pintype "passive"))
      (node (ref "IC2") (pin "#VCC") (pinfunction "3V3_#VCC") (pintype "output"))
      (node (ref "IC2") (pin "@VCC") (pinfunction "3V3_@VCC") (pintype "output"))
      (node (ref "IC2") (pin "VCC") (pinfunction "3V3_VCC") (pintype "output"))
      (node (ref "JP13") (pin "1") (pinfunction "1_1") (pintype "passive"))
      (node (ref "JP13") (pin "10") (pinfunction "10_10") (pintype "passive"))
      (node (ref "JP13") (pin "11") (pinfunction "11_11") (pintype "passive"))
      (node (ref "JP13") (pin "12") (pinfunction "12_12") (pintype "passive"))
      (node (ref "JP13") (pin "13") (pinfunction "13_13") (pintype "passive"))
      (node (ref "JP13") (pin "14") (pinfunction "14_14") (pintype "passive"))
      (node (ref "JP13") (pin "15") (pinfunction "15_15") (pintype "passive"))
      (node (ref "JP13") (pin "16") (pinfunction "16_16") (pintype "passive"))
      (node (ref "JP13") (pin "2") (pinfunction "2_2") (pintype "passive"))
      (node (ref "JP13") (pin "3") (pinfunction "3_3") (pintype "passive"))
      (node (ref "JP13") (pin "4") (pinfunction "4_4") (pintype "passive"))
      (node (ref "JP13") (pin "5") (pinfunction "5_5") (pintype "passive"))
      (node (ref "JP13") (pin "6") (pinfunction "6_6") (pintype "passive"))
      (node (ref "JP13") (pin "7") (pinfunction "7_7") (pintype "passive"))
      (node (ref "JP13") (pin "8") (pinfunction "8_8") (pintype "passive"))
      (node (ref "JP13") (pin "9") (pinfunction "9_9") (pintype "passive"))
      (node (ref "JP16") (pin "1") (pinfunction "1_1") (pintype "passive"))
      (node (ref "JP5") (pin "1") (pinfunction "1_1") (pintype "passive"))
      (node (ref "JP5") (pin "10") (pinfunction "10_10") (pintype "passive"))
      (node (ref "JP5") (pin "2") (pinfunction "2_2") (pintype "passive"))
      (node (ref "JP5") (pin "3") (pinfunction "3_3") (pintype "passive"))
      (node (ref "JP5") (pin "4") (pinfunction "4_4") (pintype "passive"))
      (node (ref "JP5") (pin "5") (pinfunction "5_5") (pintype "passive"))
      (node (ref "JP5") (pin "6") (pinfunction "6_6") (pintype "passive"))
      (node (ref "JP5") (pin "7") (pinfunction "7_7") (pintype "passive"))
      (node (ref "JP5") (pin "8") (pinfunction "8_8") (pintype "passive"))
      (node (ref "JP5") (pin "9") (pinfunction "9_9") (pintype "passive"))
      (node (ref "R1") (pin "2") (pinfunction "2_2") (pintype "passive"))
      (node (ref "R2") (pin "1") (pinfunction "1_1") (pintype "passive"))
      (node (ref "R5") (pin "1") (pinfunction "1_1") (pintype "passive"))
      (node (ref "R64") (pin "2") (pinfunction "2_2") (pintype "passive"))
      (node (ref "R65") (pin "2") (pinfunction "2_2") (pintype "passive"))
    )
    (net (code "2") (name "5V") (class "Default")
      (node (ref "IC2") (pin "#5V") (pinfunction "5V_#5V") (pintype "output"))
      (node (ref "IC2") (pin "5V") (pinfunction "5V_5V") (pintype "output"))
      (node (ref "IC2") (pin "@5V") (pinfunction "5V_@5V") (pintype "output"))
    )
    (net (code "3") (name "12V") (class "Default")
      (node (ref "C1") (pin "1") (pinfunction "1_1") (pintype "passive"))
      (node (ref "IC1") (pin "IN") (pinfunction "IN_IN") (pintype "input"))
      (node (ref "JP110") (pin "PWR") (pinfunction "PWR_PWR") (pintype "bidirectional"))
      (node (ref "JP2") (pin "1") (pinfunction "1_1") (pintype "passive"))
      (node (ref "JP2") (pin "2") (pinfunction "2_2") (pintype "passive"))
      (node (ref "JP2") (pin "3") (pinfunction "3_3") (pintype "passive"))
      (node (ref "JP2") (pin "4") (pinfunction "4_4") (pintype "passive"))
      (node (ref "JP4") (pin "2") (pinfunction "2_2") (pintype "passive"))
      (node (ref "R28") (pin "1") (pinfunction "1_1") (pintype "passive"))
    )
    (net (code "4") (name "A0C") (class "Default")
      (node (ref "IC2") (pin "#A0") (pinfunction "A0_#A0") (pintype "bidirectional"))
      (node (ref "IC2") (pin "@A0") (pinfunction "A0_@A0") (pintype "bidirectional"))
      (node (ref "IC2") (pin "A0") (pinfunction "A0_A0") (pintype "bidirectional"))
      (node (ref "JP102") (pin "1") (pinfunction "1_1") (pintype "passive"))
      (node (ref "JP102") (pin "2") (pinfunction "2_2") (pintype "passive"))
      (node (ref "JP102") (pin "3") (pinfunction "3_3") (pintype "passive"))
      (node (ref "JP102") (pin "4") (pinfunction "4_4") (pintype "passive"))
      (node (ref "JP102") (pin "5") (pinfunction "5_5") (pintype "passive"))
      (node (ref "JP102") (pin "6") (pinfunction "6_6") (pintype "passive"))
      (node (ref "JP102") (pin "7") (pinfunction "7_7") (pintype "passive"))
      (node (ref "JP102") (pin "8") (pinfunction "8_8") (pintype "passive"))
    )
    (net (code "5") (name "A1C") (class "Default")
      (node (ref "IC2") (pin "#A1") (pinfunction "A1_#A1") (pintype "bidirectional"))
      (node (ref "IC2") (pin "@A1") (pinfunction "A1_@A1") (pintype "bidirectional"))
      (node (ref "IC2") (pin "A1") (pinfunction "A1_A1") (pintype "bidirectional"))
      (node (ref "JP101") (pin "1") (pinfunction "1_1") (pintype "passive"))
      (node (ref "JP101") (pin "2") (pinfunction "2_2") (pintype "passive"))
      (node (ref "JP101") (pin "3") (pinfunction "3_3") (pintype "passive"))
      (node (ref "JP101") (pin "4") (pinfunction "4_4") (pintype "passive"))
      (node (ref "JP101") (pin "5") (pinfunction "5_5") (pintype "passive"))
      (node (ref "JP101") (pin "6") (pinfunction "6_6") (pintype "passive"))
      (node (ref "JP101") (pin "7") (pinfunction "7_7") (pintype "passive"))
      (node (ref "JP101") (pin "8") (pinfunction "8_8") (pintype "passive"))
    )
    (net (code "6") (name "A2C") (class "Default")
      (node (ref "IC2") (pin "#A2") (pinfunction "A2_#A2") (pintype "bidirectional"))
      (node (ref "IC2") (pin "@A2") (pinfunction "A2_@A2") (pintype "bidirectional"))
      (node (ref "IC2") (pin "A2") (pinfunction "A2_A2") (pintype "bidirectional"))
      (node (ref "JP100") (pin "1") (pinfunction "1_1") (pintype "passive"))
      (node (ref "JP100") (pin "2") (pinfunction "2_2") (pintype "passive"))
      (node (ref "JP100") (pin "3") (pinfunction "3_3") (pintype "passive"))
      (node (ref "JP100") (pin "4") (pinfunction "4_4") (pintype "passive"))
      (node (ref "JP100") (pin "5") (pinfunction "5_5") (pintype "passive"))
      (node (ref "JP100") (pin "6") (pinfunction "6_6") (pintype "passive"))
      (node (ref "JP100") (pin "7") (pinfunction "7_7") (pintype "passive"))
      (node (ref "JP100") (pin "8") (pinfunction "8_8") (pintype "passive"))
    )
    (net (code "7") (name "A3C") (class "Default")
      (node (ref "IC2") (pin "#A3") (pinfunction "A3_#A3") (pintype "bidirectional"))
      (node (ref "IC2") (pin "@A3") (pinfunction "A3_@A3") (pintype "bidirectional"))
      (node (ref "IC2") (pin "A3") (pinfunction "A3_A3") (pintype "bidirectional"))
      (node (ref "JP99") (pin "1") (pinfunction "1_1") (pintype "passive"))
      (node (ref "JP99") (pin "2") (pinfunction "2_2") (pintype "passive"))
      (node (ref "JP99") (pin "3") (pinfunction "3_3") (pintype "passive"))
      (node (ref "JP99") (pin "4") (pinfunction "4_4") (pintype "passive"))
      (node (ref "JP99") (pin "5") (pinfunction "5_5") (pintype "passive"))
      (node (ref "JP99") (pin "6") (pinfunction "6_6") (pintype "passive"))
      (node (ref "JP99") (pin "7") (pinfunction "7_7") (pintype "passive"))
      (node (ref "JP99") (pin "8") (pinfunction "8_8") (pintype "passive"))
    )
    (net (code "8") (name "A4C") (class "Default")
      (node (ref "IC2") (pin "#A4") (pinfunction "A4_#A4") (pintype "bidirectional"))
      (node (ref "IC2") (pin "@A4") (pinfunction "A4_@A4") (pintype "bidirectional"))
      (node (ref "IC2") (pin "A4") (pinfunction "A4_A4") (pintype "bidirectional"))
      (node (ref "JP98") (pin "1") (pinfunction "1_1") (pintype "passive"))
      (node (ref "JP98") (pin "2") (pinfunction "2_2") (pintype "passive"))
      (node (ref "JP98") (pin "3") (pinfunction "3_3") (pintype "passive"))
      (node (ref "JP98") (pin "4") (pinfunction "4_4") (pintype "passive"))
      (node (ref "JP98") (pin "5") (pinfunction "5_5") (pintype "passive"))
      (node (ref "JP98") (pin "6") (pinfunction "6_6") (pintype "passive"))
      (node (ref "JP98") (pin "7") (pinfunction "7_7") (pintype "passive"))
      (node (ref "JP98") (pin "8") (pinfunction "8_8") (pintype "passive"))
    )
    (net (code "9") (name "A5C") (class "Default")
      (node (ref "IC2") (pin "#A5") (pinfunction "A5_#A5") (pintype "bidirectional"))
      (node (ref "IC2") (pin "@A5") (pinfunction "A5_@A5") (pintype "bidirectional"))
      (node (ref "IC2") (pin "A5") (pinfunction "A5_A5") (pintype "bidirectional"))
      (node (ref "JP54") (pin "1") (pinfunction "1_1") (pintype "passive"))
      (node (ref "JP54") (pin "2") (pinfunction "2_2") (pintype "passive"))
      (node (ref "JP54") (pin "3") (pinfunction "3_3") (pintype "passive"))
      (node (ref "JP54") (pin "4") (pinfunction "4_4") (pintype "passive"))
      (node (ref "JP54") (pin "5") (pinfunction "5_5") (pintype "passive"))
      (node (ref "JP54") (pin "6") (pinfunction "6_6") (pintype "passive"))
      (node (ref "JP54") (pin "7") (pinfunction "7_7") (pintype "passive"))
      (node (ref "JP54") (pin "8") (pinfunction "8_8") (pintype "passive"))
    )
    (net (code "10") (name "A6C") (class "Default")
      (node (ref "IC2") (pin "#A6") (pinfunction "A6_#A6") (pintype "bidirectional"))
      (node (ref "IC2") (pin "@A6") (pinfunction "A6_@A6") (pintype "bidirectional"))
      (node (ref "IC2") (pin "A6") (pinfunction "A6_A6") (pintype "bidirectional"))
      (node (ref "JP29") (pin "1") (pinfunction "1_1") (pintype "passive"))
      (node (ref "JP29") (pin "2") (pinfunction "2_2") (pintype "passive"))
      (node (ref "JP29") (pin "3") (pinfunction "3_3") (pintype "passive"))
      (node (ref "JP29") (pin "4") (pinfunction "4_4") (pintype "passive"))
      (node (ref "JP29") (pin "5") (pinfunction "5_5") (pintype "passive"))
      (node (ref "JP29") (pin "6") (pinfunction "6_6") (pintype "passive"))
      (node (ref "JP29") (pin "7") (pinfunction "7_7") (pintype "passive"))
      (node (ref "JP29") (pin "8") (pinfunction "8_8") (pintype "passive"))
    )
    (net (code "11") (name "AREF") (class "Default")
      (node (ref "IC2") (pin "#AREF") (pinfunction "AREF_#AREF") (pintype "bidirectional"))
      (node (ref "IC2") (pin "@AREF") (pinfunction "AREF_@AREF") (pintype "bidirectional"))
      (node (ref "IC2") (pin "AREF") (pinfunction "AREF_AREF") (pintype "bidirectional"))
    )
    (net (code "12") (name "C1C") (class "Default")
      (node (ref "JP28") (pin "1") (pinfunction "1_1") (pintype "passive"))
      (node (ref "JP28") (pin "2") (pinfunction "2_2") (pintype "passive"))
      (node (ref "JP28") (pin "3") (pinfunction "3_3") (pintype "passive"))
      (node (ref "JP28") (pin "4") (pinfunction "4_4") (pintype "passive"))
      (node (ref "JP28") (pin "5") (pinfunction "5_5") (pintype "passive"))
      (node (ref "JP28") (pin "6") (pinfunction "6_6") (pintype "passive"))
      (node (ref "JP28") (pin "7") (pinfunction "7_7") (pintype "passive"))
      (node (ref "JP28") (pin "8") (pinfunction "8_8") (pintype "passive"))
      (node (ref "R26") (pin "1") (pinfunction "1_1") (pintype "passive"))
    )
    (net (code "13") (name "C2C") (class "Default")
      (node (ref "JP27") (pin "1") (pinfunction "1_1") (pintype "passive"))
      (node (ref "JP27") (pin "2") (pinfunction "2_2") (pintype "passive"))
      (node (ref "JP27") (pin "3") (pinfunction "3_3") (pintype "passive"))
      (node (ref "JP27") (pin "4") (pinfunction "4_4") (pintype "passive"))
      (node (ref "JP27") (pin "5") (pinfunction "5_5") (pintype "passive"))
      (node (ref "JP27") (pin "6") (pinfunction "6_6") (pintype "passive"))
      (node (ref "JP27") (pin "7") (pinfunction "7_7") (pintype "passive"))
      (node (ref "JP27") (pin "8") (pinfunction "8_8") (pintype "passive"))
      (node (ref "R24") (pin "1") (pinfunction "1_1") (pintype "passive"))
    )
    (net (code "14") (name "C3C") (class "Default")
      (node (ref "JP26") (pin "1") (pinfunction "1_1") (pintype "passive"))
      (node (ref "JP26") (pin "2") (pinfunction "2_2") (pintype "passive"))
      (node (ref "JP26") (pin "3") (pinfunction "3_3") (pintype "passive"))
      (node (ref "JP26") (pin "4") (pinfunction "4_4") (pintype "passive"))
      (node (ref "JP26") (pin "5") (pinfunction "5_5") (pintype "passive"))
      (node (ref "JP26") (pin "6") (pinfunction "6_6") (pintype "passive"))
      (node (ref "JP26") (pin "7") (pinfunction "7_7") (pintype "passive"))
      (node (ref "JP26") (pin "8") (pinfunction "8_8") (pintype "passive"))
      (node (ref "R22") (pin "1") (pinfunction "1_1") (pintype "passive"))
    )
    (net (code "15") (name "C5C") (class "Default")
      (node (ref "JP24") (pin "1") (pinfunction "1_1") (pintype "passive"))
      (node (ref "JP24") (pin "2") (pinfunction "2_2") (pintype "passive"))
      (node (ref "JP24") (pin "3") (pinfunction "3_3") (pintype "passive"))
      (node (ref "JP24") (pin "4") (pinfunction "4_4") (pintype "passive"))
      (node (ref "JP24") (pin "5") (pinfunction "5_5") (pintype "passive"))
      (node (ref "JP24") (pin "6") (pinfunction "6_6") (pintype "passive"))
      (node (ref "JP24") (pin "7") (pinfunction "7_7") (pintype "passive"))
      (node (ref "JP24") (pin "8") (pinfunction "8_8") (pintype "passive"))
      (node (ref "R18") (pin "1") (pinfunction "1_1") (pintype "passive"))
    )
    (net (code "16") (name "D0C") (class "Default")
      (node (ref "IC2") (pin "#D0") (pinfunction "D0_#D0") (pintype "bidirectional"))
      (node (ref "IC2") (pin "@D0") (pinfunction "D0_@D0") (pintype "bidirectional"))
      (node (ref "IC2") (pin "D0") (pinfunction "D0_D0") (pintype "bidirectional"))
      (node (ref "JP22") (pin "1") (pinfunction "1_1") (pintype "passive"))
      (node (ref "JP22") (pin "2") (pinfunction "2_2") (pintype "passive"))
      (node (ref "JP22") (pin "3") (pinfunction "3_3") (pintype "passive"))
      (node (ref "JP22") (pin "4") (pinfunction "4_4") (pintype "passive"))
      (node (ref "JP22") (pin "5") (pinfunction "5_5") (pintype "passive"))
      (node (ref "JP22") (pin "6") (pinfunction "6_6") (pintype "passive"))
      (node (ref "JP22") (pin "7") (pinfunction "7_7") (pintype "passive"))
      (node (ref "JP22") (pin "8") (pinfunction "8_8") (pintype "passive"))
      (node (ref "R16") (pin "1") (pinfunction "1_1") (pintype "passive"))
    )
    (net (code "17") (name "D1C") (class "Default")
      (node (ref "IC2") (pin "#D1") (pinfunction "D1_#D1") (pintype "bidirectional"))
      (node (ref "IC2") (pin "@D1") (pinfunction "D1_@D1") (pintype "bidirectional"))
      (node (ref "IC2") (pin "D1") (pinfunction "D1_D1") (pintype "bidirectional"))
      (node (ref "JP21") (pin "1") (pinfunction "1_1") (pintype "passive"))
      (node (ref "JP21") (pin "2") (pinfunction "2_2") (pintype "passive"))
      (node (ref "JP21") (pin "3") (pinfunction "3_3") (pintype "passive"))
      (node (ref "JP21") (pin "4") (pinfunction "4_4") (pintype "passive"))
      (node (ref "JP21") (pin "5") (pinfunction "5_5") (pintype "passive"))
      (node (ref "JP21") (pin "6") (pinfunction "6_6") (pintype "passive"))
      (node (ref "JP21") (pin "7") (pinfunction "7_7") (pintype "passive"))
      (node (ref "JP21") (pin "8") (pinfunction "8_8") (pintype "passive"))
      (node (ref "R14") (pin "1") (pinfunction "1_1") (pintype "passive"))
    )
    (net (code "18") (name "D2C") (class "Default")
      (node (ref "IC2") (pin "#D2") (pinfunction "D2_#D2") (pintype "bidirectional"))
      (node (ref "IC2") (pin "@D2") (pinfunction "D2_@D2") (pintype "bidirectional"))
      (node (ref "IC2") (pin "D2") (pinfunction "D2_D2") (pintype "bidirectional"))
      (node (ref "JP20") (pin "1") (pinfunction "1_1") (pintype "passive"))
      (node (ref "JP20") (pin "2") (pinfunction "2_2") (pintype "passive"))
      (node (ref "JP20") (pin "3") (pinfunction "3_3") (pintype "passive"))
      (node (ref "JP20") (pin "4") (pinfunction "4_4") (pintype "passive"))
      (node (ref "JP20") (pin "5") (pinfunction "5_5") (pintype "passive"))
      (node (ref "JP20") (pin "6") (pinfunction "6_6") (pintype "passive"))
      (node (ref "JP20") (pin "7") (pinfunction "7_7") (pintype "passive"))
      (node (ref "JP20") (pin "8") (pinfunction "8_8") (pintype "passive"))
      (node (ref "R12") (pin "1") (pinfunction "1_1") (pintype "passive"))
    )
    (net (code "19") (name "D3C") (class "Default")
      (node (ref "IC2") (pin "#D3") (pinfunction "D3_#D3") (pintype "bidirectional"))
      (node (ref "IC2") (pin "@D3") (pinfunction "D3_@D3") (pintype "bidirectional"))
      (node (ref "IC2") (pin "D3") (pinfunction "D3_D3") (pintype "bidirectional"))
      (node (ref "JP19") (pin "1") (pinfunction "1_1") (pintype "passive"))
      (node (ref "JP19") (pin "2") (pinfunction "2_2") (pintype "passive"))
      (node (ref "JP19") (pin "3") (pinfunction "3_3") (pintype "passive"))
      (node (ref "JP19") (pin "4") (pinfunction "4_4") (pintype "passive"))
      (node (ref "JP19") (pin "5") (pinfunction "5_5") (pintype "passive"))
      (node (ref "JP19") (pin "6") (pinfunction "6_6") (pintype "passive"))
      (node (ref "JP19") (pin "7") (pinfunction "7_7") (pintype "passive"))
      (node (ref "JP19") (pin "8") (pinfunction "8_8") (pintype "passive"))
      (node (ref "R10") (pin "1") (pinfunction "1_1") (pintype "passive"))
    )
    (net (code "20") (name "D4C") (class "Default")
      (node (ref "IC2") (pin "#D4") (pinfunction "D4_#D4") (pintype "bidirectional"))
      (node (ref "IC2") (pin "@D4") (pinfunction "D4_@D4") (pintype "bidirectional"))
      (node (ref "IC2") (pin "D4") (pinfunction "D4_D4") (pintype "bidirectional"))
      (node (ref "JP18") (pin "1") (pinfunction "1_1") (pintype "passive"))
      (node (ref "JP18") (pin "2") (pinfunction "2_2") (pintype "passive"))
      (node (ref "JP18") (pin "3") (pinfunction "3_3") (pintype "passive"))
      (node (ref "JP18") (pin "4") (pinfunction "4_4") (pintype "passive"))
      (node (ref "JP18") (pin "5") (pinfunction "5_5") (pintype "passive"))
      (node (ref "JP18") (pin "6") (pinfunction "6_6") (pintype "passive"))
      (node (ref "JP18") (pin "7") (pinfunction "7_7") (pintype "passive"))
      (node (ref "JP18") (pin "8") (pinfunction "8_8") (pintype "passive"))
      (node (ref "R8") (pin "2") (pinfunction "2_2") (pintype "passive"))
    )
    (net (code "21") (name "D5C") (class "Default")
      (node (ref "IC2") (pin "#D5") (pinfunction "D5_#D5") (pintype "bidirectional"))
      (node (ref "IC2") (pin "@D5") (pinfunction "D5_@D5") (pintype "bidirectional"))
      (node (ref "IC2") (pin "D5") (pinfunction "D5_D5") (pintype "bidirectional"))
      (node (ref "JP10") (pin "1") (pinfunction "1_1") (pintype "passive"))
      (node (ref "JP10") (pin "2") (pinfunction "2_2") (pintype "passive"))
      (node (ref "JP10") (pin "3") (pinfunction "3_3") (pintype "passive"))
      (node (ref "JP10") (pin "4") (pinfunction "4_4") (pintype "passive"))
      (node (ref "JP10") (pin "5") (pinfunction "5_5") (pintype "passive"))
      (node (ref "JP10") (pin "6") (pinfunction "6_6") (pintype "passive"))
      (node (ref "JP10") (pin "7") (pinfunction "7_7") (pintype "passive"))
      (node (ref "JP10") (pin "8") (pinfunction "8_8") (pintype "passive"))
      (node (ref "R6") (pin "2") (pinfunction "2_2") (pintype "passive"))
    )
    (net (code "22") (name "D6C") (class "Default")
      (node (ref "IC2") (pin "#D6") (pinfunction "D6_#D6") (pintype "bidirectional"))
      (node (ref "IC2") (pin "@D6") (pinfunction "D6_@D6") (pintype "bidirectional"))
      (node (ref "IC2") (pin "D6") (pinfunction "D6_D6") (pintype "bidirectional"))
      (node (ref "JP7") (pin "1") (pinfunction "1_1") (pintype "passive"))
      (node (ref "JP7") (pin "2") (pinfunction "2_2") (pintype "passive"))
      (node (ref "JP7") (pin "3") (pinfunction "3_3") (pintype "passive"))
      (node (ref "JP7") (pin "4") (pinfunction "4_4") (pintype "passive"))
      (node (ref "JP7") (pin "5") (pinfunction "5_5") (pintype "passive"))
      (node (ref "JP7") (pin "6") (pinfunction "6_6") (pintype "passive"))
      (node (ref "JP7") (pin "7") (pinfunction "7_7") (pintype "passive"))
      (node (ref "JP7") (pin "8") (pinfunction "8_8") (pintype "passive"))
      (node (ref "R4") (pin "2") (pinfunction "2_2") (pintype "passive"))
    )
    (net (code "23") (name "D7C") (class "Default")
      (node (ref "IC2") (pin "#D7") (pinfunction "D7_#D7") (pintype "bidirectional"))
      (node (ref "IC2") (pin "@D7") (pinfunction "D7_@D7") (pintype "bidirectional"))
      (node (ref "IC2") (pin "D7") (pinfunction "D7_D7") (pintype "bidirectional"))
      (node (ref "JP1") (pin "1") (pinfunction "1_1") (pintype "passive"))
      (node (ref "JP1") (pin "2") (pinfunction "2_2") (pintype "passive"))
      (node (ref "JP1") (pin "3") (pinfunction "3_3") (pintype "passive"))
      (node (ref "JP1") (pin "4") (pinfunction "4_4") (pintype "passive"))
      (node (ref "JP1") (pin "5") (pinfunction "5_5") (pintype "passive"))
      (node (ref "JP1") (pin "6") (pinfunction "6_6") (pintype "passive"))
      (node (ref "JP1") (pin "7") (pinfunction "7_7") (pintype "passive"))
      (node (ref "JP1") (pin "8") (pinfunction "8_8") (pintype "passive"))
      (node (ref "R3") (pin "2") (pinfunction "2_2") (pintype "passive"))
    )
    (net (code "24") (name "GND") (class "Default")
      (node (ref "C1") (pin "2") (pinfunction "2_2") (pintype "passive"))
      (node (ref "C2") (pin "2") (pinfunction "2_2") (pintype "passive"))
      (node (ref "C3") (pin "2") (pinfunction "2_2") (pintype "passive"))
      (node (ref "C4") (pin "2") (pinfunction "2_2") (pintype "passive"))
      (node (ref "C5") (pin "2") (pinfunction "2_2") (pintype "passive"))
      (node (ref "C6") (pin "2") (pinfunction "2_2") (pintype "passive"))
      (node (ref "C7") (pin "2") (pinfunction "2_2") (pintype "passive"))
      (node (ref "D1") (pin "C") (pinfunction "C_C") (pintype "passive"))
      (node (ref "D2") (pin "C") (pinfunction "C_C") (pintype "passive"))
      (node (ref "IC1") (pin "GND") (pinfunction "GND_GND") (pintype "input"))
      (node (ref "IC2") (pin "#GND") (pinfunction "GND_#GND") (pintype "power_in"))
      (node (ref "IC2") (pin "@GND") (pinfunction "GND_@GND") (pintype "power_in"))
      (node (ref "IC2") (pin "GND") (pinfunction "GND_GND") (pintype "power_in"))
      (node (ref "JP109") (pin "1") (pinfunction "1_1") (pintype "passive"))
      (node (ref "JP109") (pin "2") (pinfunction "2_2") (pintype "passive"))
      (node (ref "JP109") (pin "3") (pinfunction "3_3") (pintype "passive"))
      (node (ref "JP109") (pin "4") (pinfunction "4_4") (pintype "passive"))
      (node (ref "JP11") (pin "1") (pinfunction "1_1") (pintype "passive"))
      (node (ref "JP11") (pin "10") (pinfunction "10_10") (pintype "passive"))
      (node (ref "JP11") (pin "2") (pinfunction "2_2") (pintype "passive"))
      (node (ref "JP11") (pin "3") (pinfunction "3_3") (pintype "passive"))
      (node (ref "JP11") (pin "4") (pinfunction "4_4") (pintype "passive"))
      (node (ref "JP11") (pin "5") (pinfunction "5_5") (pintype "passive"))
      (node (ref "JP11") (pin "6") (pinfunction "6_6") (pintype "passive"))
      (node (ref "JP11") (pin "7") (pinfunction "7_7") (pintype "passive"))
      (node (ref "JP11") (pin "8") (pinfunction "8_8") (pintype "passive"))
      (node (ref "JP11") (pin "9") (pinfunction "9_9") (pintype "passive"))
      (node (ref "JP110") (pin "GND") (pinfunction "GND_GND") (pintype "bidirectional"))
      (node (ref "JP110") (pin "GNDBREAK") (pinfunction "GNDBREAK_GNDBREAK") (pintype "bidirectional"))
      (node (ref "JP14") (pin "1") (pinfunction "1_1") (pintype "passive"))
      (node (ref "JP14") (pin "10") (pinfunction "10_10") (pintype "passive"))
      (node (ref "JP14") (pin "11") (pinfunction "11_11") (pintype "passive"))
      (node (ref "JP14") (pin "12") (pinfunction "12_12") (pintype "passive"))
      (node (ref "JP14") (pin "13") (pinfunction "13_13") (pintype "passive"))
      (node (ref "JP14") (pin "14") (pinfunction "14_14") (pintype "passive"))
      (node (ref "JP14") (pin "15") (pinfunction "15_15") (pintype "passive"))
      (node (ref "JP14") (pin "16") (pinfunction "16_16") (pintype "passive"))
      (node (ref "JP14") (pin "2") (pinfunction "2_2") (pintype "passive"))
      (node (ref "JP14") (pin "3") (pinfunction "3_3") (pintype "passive"))
      (node (ref "JP14") (pin "4") (pinfunction "4_4") (pintype "passive"))
      (node (ref "JP14") (pin "5") (pinfunction "5_5") (pintype "passive"))
      (node (ref "JP14") (pin "6") (pinfunction "6_6") (pintype "passive"))
      (node (ref "JP14") (pin "7") (pinfunction "7_7") (pintype "passive"))
      (node (ref "JP14") (pin "8") (pinfunction "8_8") (pintype "passive"))
      (node (ref "JP14") (pin "9") (pinfunction "9_9") (pintype "passive"))
      (node (ref "JP23") (pin "1") (pinfunction "1_1") (pintype "passive"))
      (node (ref "JP23") (pin "2") (pinfunction "2_2") (pintype "passive"))
      (node (ref "JP23") (pin "3") (pinfunction "3_3") (pintype "passive"))
      (node (ref "JP23") (pin "4") (pinfunction "4_4") (pintype "passive"))
      (node (ref "JP23") (pin "5") (pinfunction "5_5") (pintype "passive"))
      (node (ref "JP23") (pin "6") (pinfunction "6_6") (pintype "passive"))
      (node (ref "JP23") (pin "7") (pinfunction "7_7") (pintype "passive"))
      (node (ref "JP23") (pin "8") (pinfunction "8_8") (pintype "passive"))
      (node (ref "JP32") (pin "1") (pinfunction "1_1") (pintype "passive"))
      (node (ref "JP32") (pin "2") (pinfunction "2_2") (pintype "passive"))
      (node (ref "JP33") (pin "1") (pinfunction "1_1") (pintype "passive"))
      (node (ref "JP4") (pin "1") (pinfunction "1_1") (pintype "passive"))
    )
    (net (code "25") (name "LED_COMMON") (class "Default")
      (node (ref "JP30") (pin "1") (pinfunction "1_1") (pintype "passive"))
      (node (ref "R11") (pin "2") (pinfunction "2_2") (pintype "passive"))
      (node (ref "R13") (pin "2") (pinfunction "2_2") (pintype "passive"))
      (node (ref "R15") (pin "2") (pinfunction "2_2") (pintype "passive"))
      (node (ref "R17") (pin "2") (pinfunction "2_2") (pintype "passive"))
      (node (ref "R19") (pin "2") (pinfunction "2_2") (pintype "passive"))
      (node (ref "R23") (pin "2") (pinfunction "2_2") (pintype "passive"))
      (node (ref "R25") (pin "1") (pinfunction "1_1") (pintype "passive"))
      (node (ref "R27") (pin "1") (pinfunction "1_1") (pintype "passive"))
      (node (ref "R7") (pin "1") (pinfunction "1_1") (pintype "passive"))
      (node (ref "R9") (pin "1") (pinfunction "1_1") (pintype "passive"))
    )
    (net (code "26") (name "MISO") (class "Default")
      (node (ref "IC2") (pin "#MISO") (pinfunction "MISO_#MISO") (pintype "bidirectional"))
      (node (ref "IC2") (pin "@MISO") (pinfunction "MISO_@MISO") (pintype "bidirectional"))
      (node (ref "IC2") (pin "MISO") (pinfunction "MISO_MISO") (pintype "bidirectional"))
      (node (ref "JP105") (pin "1") (pinfunction "1_1") (pintype "passive"))
      (node (ref "JP105") (pin "2") (pinfunction "2_2") (pintype "passive"))
      (node (ref "JP105") (pin "3") (pinfunction "3_3") (pintype "passive"))
      (node (ref "JP105") (pin "4") (pinfunction "4_4") (pintype "passive"))
      (node (ref "JP105") (pin "5") (pinfunction "5_5") (pintype "passive"))
      (node (ref "JP105") (pin "6") (pinfunction "6_6") (pintype "passive"))
      (node (ref "JP105") (pin "7") (pinfunction "7_7") (pintype "passive"))
      (node (ref "JP105") (pin "8") (pinfunction "8_8") (pintype "passive"))
    )
    (net (code "27") (name "MOSI") (class "Default")
      (node (ref "IC2") (pin "#MOSI") (pinfunction "MOSI_#MOSI") (pintype "bidirectional"))
      (node (ref "IC2") (pin "@MOSI") (pinfunction "MOSI_@MOSI") (pintype "bidirectional"))
      (node (ref "IC2") (pin "MOSI") (pinfunction "MOSI_MOSI") (pintype "bidirectional"))
      (node (ref "JP103") (pin "1") (pinfunction "1_1") (pintype "passive"))
      (node (ref "JP103") (pin "2") (pinfunction "2_2") (pintype "passive"))
      (node (ref "JP103") (pin "3") (pinfunction "3_3") (pintype "passive"))
      (node (ref "JP103") (pin "4") (pinfunction "4_4") (pintype "passive"))
      (node (ref "JP103") (pin "5") (pinfunction "5_5") (pintype "passive"))
      (node (ref "JP103") (pin "6") (pinfunction "6_6") (pintype "passive"))
      (node (ref "JP103") (pin "7") (pinfunction "7_7") (pintype "passive"))
      (node (ref "JP103") (pin "8") (pinfunction "8_8") (pintype "passive"))
    )
    (net (code "28") (name "Net-(D1-PadA)") (class "Default")
      (node (ref "D1") (pin "A") (pinfunction "A_A") (pintype "passive"))
      (node (ref "R1") (pin "1") (pinfunction "1_1") (pintype "passive"))
    )
    (net (code "29") (name "Net-(D2-PadA)") (class "Default")
      (node (ref "D2") (pin "A") (pinfunction "A_A") (pintype "passive"))
      (node (ref "R28") (pin "2") (pinfunction "2_2") (pintype "passive"))
    )
    (net (code "30") (name "Net-(JP31-Pad1)") (class "Default")
      (node (ref "JP31") (pin "1") (pinfunction "1_1") (pintype "passive"))
      (node (ref "JP31") (pin "2") (pinfunction "2_2") (pintype "passive"))
      (node (ref "R31") (pin "2") (pinfunction "2_2") (pintype "passive"))
    )
    (net (code "31") (name "Net-(JP34-Pad1)") (class "Default")
      (node (ref "JP34") (pin "1") (pinfunction "1_1") (pintype "passive"))
      (node (ref "JP34") (pin "2") (pinfunction "2_2") (pintype "passive"))
      (node (ref "R48") (pin "2") (pinfunction "2_2") (pintype "passive"))
    )
    (net (code "32") (name "Net-(JP35-Pad1)") (class "Default")
      (node (ref "JP35") (pin "1") (pinfunction "1_1") (pintype "passive"))
      (node (ref "R37") (pin "1") (pinfunction "1_1") (pintype "passive"))
    )
    (net (code "33") (name "Net-(JP36-Pad1)") (class "Default")
      (node (ref "JP36") (pin "1") (pinfunction "1_1") (pintype "passive"))
      (node (ref "R30") (pin "1") (pinfunction "1_1") (pintype "passive"))
    )
    (net (code "34") (name "Net-(JP37-Pad1)") (class "Default")
      (node (ref "JP37") (pin "1") (pinfunction "1_1") (pintype "passive"))
      (node (ref "R46") (pin "1") (pinfunction "1_1") (pintype "passive"))
    )
    (net (code "35") (name "Net-(JP38-Pad1)") (class "Default")
      (node (ref "JP38") (pin "1") (pinfunction "1_1") (pintype "passive"))
      (node (ref "JP38") (pin "2") (pinfunction "2_2") (pintype "passive"))
      (node (ref "R32") (pin "2") (pinfunction "2_2") (pintype "passive"))
    )
    (net (code "36") (name "Net-(JP39-Pad1)") (class "Default")
      (node (ref "JP39") (pin "1") (pinfunction "1_1") (pintype "passive"))
      (node (ref "JP39") (pin "2") (pinfunction "2_2") (pintype "passive"))
      (node (ref "R49") (pin "2") (pinfunction "2_2") (pintype "passive"))
    )
    (net (code "37") (name "Net-(JP40-Pad1)") (class "Default")
      (node (ref "JP40") (pin "1") (pinfunction "1_1") (pintype "passive"))
      (node (ref "R31") (pin "1") (pinfunction "1_1") (pintype "passive"))
    )
    (net (code "38") (name "Net-(JP41-Pad1)") (class "Default")
      (node (ref "JP41") (pin "1") (pinfunction "1_1") (pintype "passive"))
      (node (ref "R32") (pin "1") (pinfunction "1_1") (pintype "passive"))
    )
    (net (code "39") (name "Net-(JP42-Pad1)") (class "Default")
      (node (ref "JP42") (pin "1") (pinfunction "1_1") (pintype "passive"))
      (node (ref "R33") (pin "1") (pinfunction "1_1") (pintype "passive"))
    )
    (net (code "40") (name "Net-(JP43-Pad1)") (class "Default")
      (node (ref "JP43") (pin "1") (pinfunction "1_1") (pintype "passive"))
      (node (ref "R34") (pin "1") (pinfunction "1_1") (pintype "passive"))
    )
    (net (code "41") (name "Net-(JP44-Pad1)") (class "Default")
      (node (ref "JP44") (pin "1") (pinfunction "1_1") (pintype "passive"))
      (node (ref "R35") (pin "1") (pinfunction "1_1") (pintype "passive"))
    )
    (net (code "42") (name "Net-(JP45-Pad1)") (class "Default")
      (node (ref "JP45") (pin "1") (pinfunction "1_1") (pintype "passive"))
      (node (ref "R36") (pin "1") (pinfunction "1_1") (pintype "passive"))
    )
    (net (code "43") (name "Net-(JP46-Pad1)") (class "Default")
      (node (ref "JP46") (pin "1") (pinfunction "1_1") (pintype "passive"))
      (node (ref "R38") (pin "1") (pinfunction "1_1") (pintype "passive"))
    )
    (net (code "44") (name "Net-(JP47-Pad1)") (class "Default")
      (node (ref "JP47") (pin "1") (pinfunction "1_1") (pintype "passive"))
      (node (ref "R39") (pin "1") (pinfunction "1_1") (pintype "passive"))
    )
    (net (code "45") (name "Net-(JP48-Pad1)") (class "Default")
      (node (ref "JP48") (pin "1") (pinfunction "1_1") (pintype "passive"))
      (node (ref "R40") (pin "1") (pinfunction "1_1") (pintype "passive"))
    )
    (net (code "46") (name "Net-(JP49-Pad1)") (class "Default")
      (node (ref "JP49") (pin "1") (pinfunction "1_1") (pintype "passive"))
      (node (ref "R41") (pin "1") (pinfunction "1_1") (pintype "passive"))
    )
    (net (code "47") (name "Net-(JP50-Pad1)") (class "Default")
      (node (ref "JP50") (pin "1") (pinfunction "1_1") (pintype "passive"))
      (node (ref "R42") (pin "1") (pinfunction "1_1") (pintype "passive"))
    )
    (net (code "48") (name "Net-(JP51-Pad1)") (class "Default")
      (node (ref "JP51") (pin "1") (pinfunction "1_1") (pintype "passive"))
      (node (ref "R43") (pin "1") (pinfunction "1_1") (pintype "passive"))
    )
    (net (code "49") (name "Net-(JP52-Pad1)") (class "Default")
      (node (ref "JP52") (pin "1") (pinfunction "1_1") (pintype "passive"))
      (node (ref "R44") (pin "1") (pinfunction "1_1") (pintype "passive"))
    )
    (net (code "50") (name "Net-(JP53-Pad1)") (class "Default")
      (node (ref "JP53") (pin "1") (pinfunction "1_1") (pintype "passive"))
      (node (ref "R45") (pin "1") (pinfunction "1_1") (pintype "passive"))
    )
    (net (code "51") (name "Net-(JP55-Pad1)") (class "Default")
      (node (ref "JP55") (pin "1") (pinfunction "1_1") (pintype "passive"))
      (node (ref "JP55") (pin "2") (pinfunction "2_2") (pintype "passive"))
      (node (ref "R30") (pin "2") (pinfunction "2_2") (pintype "passive"))
    )
    (net (code "52") (name "Net-(JP56-Pad1)") (class "Default")
      (node (ref "JP56") (pin "1") (pinfunction "1_1") (pintype "passive"))
      (node (ref "R47") (pin "1") (pinfunction "1_1") (pintype "passive"))
    )
    (net (code "53") (name "Net-(JP57-Pad1)") (class "Default")
      (node (ref "JP57") (pin "1") (pinfunction "1_1") (pintype "passive"))
      (node (ref "R48") (pin "1") (pinfunction "1_1") (pintype "passive"))
    )
    (net (code "54") (name "Net-(JP58-Pad1)") (class "Default")
      (node (ref "JP58") (pin "1") (pinfunction "1_1") (pintype "passive"))
      (node (ref "R49") (pin "1") (pinfunction "1_1") (pintype "passive"))
    )
    (net (code "55") (name "Net-(JP59-Pad1)") (class "Default")
      (node (ref "JP59") (pin "1") (pinfunction "1_1") (pintype "passive"))
      (node (ref "R50") (pin "1") (pinfunction "1_1") (pintype "passive"))
    )
    (net (code "56") (name "Net-(JP60-Pad1)") (class "Default")
      (node (ref "JP60") (pin "1") (pinfunction "1_1") (pintype "passive"))
      (node (ref "R51") (pin "1") (pinfunction "1_1") (pintype "passive"))
    )
    (net (code "57") (name "Net-(JP61-Pad1)") (class "Default")
      (node (ref "JP61") (pin "1") (pinfunction "1_1") (pintype "passive"))
      (node (ref "R52") (pin "1") (pinfunction "1_1") (pintype "passive"))
    )
    (net (code "58") (name "Net-(JP62-Pad1)") (class "Default")
      (node (ref "JP62") (pin "1") (pinfunction "1_1") (pintype "passive"))
      (node (ref "R53") (pin "1") (pinfunction "1_1") (pintype "passive"))
    )
    (net (code "59") (name "Net-(JP63-Pad1)") (class "Default")
      (node (ref "JP63") (pin "1") (pinfunction "1_1") (pintype "passive"))
      (node (ref "R54") (pin "1") (pinfunction "1_1") (pintype "passive"))
    )
    (net (code "60") (name "Net-(JP64-Pad1)") (class "Default")
      (node (ref "JP64") (pin "1") (pinfunction "1_1") (pintype "passive"))
      (node (ref "R55") (pin "1") (pinfunction "1_1") (pintype "passive"))
    )
    (net (code "61") (name "Net-(JP65-Pad1)") (class "Default")
      (node (ref "JP65") (pin "1") (pinfunction "1_1") (pintype "passive"))
      (node (ref "R56") (pin "1") (pinfunction "1_1") (pintype "passive"))
    )
    (net (code "62") (name "Net-(JP66-Pad1)") (class "Default")
      (node (ref "JP66") (pin "1") (pinfunction "1_1") (pintype "passive"))
      (node (ref "R57") (pin "1") (pinfunction "1_1") (pintype "passive"))
    )
    (net (code "63") (name "Net-(JP67-Pad1)") (class "Default")
      (node (ref "JP67") (pin "1") (pinfunction "1_1") (pintype "passive"))
      (node (ref "R58") (pin "1") (pinfunction "1_1") (pintype "passive"))
    )
    (net (code "64") (name "Net-(JP68-Pad1)") (class "Default")
      (node (ref "JP68") (pin "1") (pinfunction "1_1") (pintype "passive"))
      (node (ref "R59") (pin "1") (pinfunction "1_1") (pintype "passive"))
    )
    (net (code "65") (name "Net-(JP69-Pad1)") (class "Default")
      (node (ref "JP69") (pin "1") (pinfunction "1_1") (pintype "passive"))
      (node (ref "R60") (pin "1") (pinfunction "1_1") (pintype "passive"))
    )
    (net (code "66") (name "Net-(JP70-Pad1)") (class "Default")
      (node (ref "JP70") (pin "1") (pinfunction "1_1") (pintype "passive"))
      (node (ref "R61") (pin "1") (pinfunction "1_1") (pintype "passive"))
    )
    (net (code "67") (name "Net-(JP71-Pad1)") (class "Default")
      (node (ref "JP71") (pin "1") (pinfunction "1_1") (pintype "passive"))
      (node (ref "JP71") (pin "2") (pinfunction "2_2") (pintype "passive"))
      (node (ref "R46") (pin "2") (pinfunction "2_2") (pintype "passive"))
    )
    (net (code "68") (name "Net-(JP72-Pad1)") (class "Default")
      (node (ref "JP72") (pin "1") (pinfunction "1_1") (pintype "passive"))
      (node (ref "JP72") (pin "2") (pinfunction "2_2") (pintype "passive"))
      (node (ref "R47") (pin "2") (pinfunction "2_2") (pintype "passive"))
    )
    (net (code "69") (name "Net-(JP73-Pad1)") (class "Default")
      (node (ref "JP73") (pin "1") (pinfunction "1_1") (pintype "passive"))
      (node (ref "JP73") (pin "2") (pinfunction "2_2") (pintype "passive"))
      (node (ref "R50") (pin "2") (pinfunction "2_2") (pintype "passive"))
    )
    (net (code "70") (name "Net-(JP74-Pad1)") (class "Default")
      (node (ref "JP74") (pin "1") (pinfunction "1_1") (pintype "passive"))
      (node (ref "JP74") (pin "2") (pinfunction "2_2") (pintype "passive"))
      (node (ref "R51") (pin "2") (pinfunction "2_2") (pintype "passive"))
    )
    (net (code "71") (name "Net-(JP75-Pad1)") (class "Default")
      (node (ref "JP75") (pin "1") (pinfunction "1_1") (pintype "passive"))
      (node (ref "JP75") (pin "2") (pinfunction "2_2") (pintype "passive"))
      (node (ref "R52") (pin "2") (pinfunction "2_2") (pintype "passive"))
    )
    (net (code "72") (name "Net-(JP76-Pad1)") (class "Default")
      (node (ref "JP76") (pin "1") (pinfunction "1_1") (pintype "passive"))
      (node (ref "JP76") (pin "2") (pinfunction "2_2") (pintype "passive"))
      (node (ref "R53") (pin "2") (pinfunction "2_2") (pintype "passive"))
    )
    (net (code "73") (name "Net-(JP77-Pad1)") (class "Default")
      (node (ref "JP77") (pin "1") (pinfunction "1_1") (pintype "passive"))
      (node (ref "JP77") (pin "2") (pinfunction "2_2") (pintype "passive"))
      (node (ref "R54") (pin "2") (pinfunction "2_2") (pintype "passive"))
    )
    (net (code "74") (name "Net-(JP78-Pad1)") (class "Default")
      (node (ref "JP78") (pin "1") (pinfunction "1_1") (pintype "passive"))
      (node (ref "JP78") (pin "2") (pinfunction "2_2") (pintype "passive"))
      (node (ref "R55") (pin "2") (pinfunction "2_2") (pintype "passive"))
    )
    (net (code "75") (name "Net-(JP79-Pad1)") (class "Default")
      (node (ref "JP79") (pin "1") (pinfunction "1_1") (pintype "passive"))
      (node (ref "JP79") (pin "2") (pinfunction "2_2") (pintype "passive"))
      (node (ref "R56") (pin "2") (pinfunction "2_2") (pintype "passive"))
    )
    (net (code "76") (name "Net-(JP80-Pad1)") (class "Default")
      (node (ref "JP80") (pin "1") (pinfunction "1_1") (pintype "passive"))
      (node (ref "JP80") (pin "2") (pinfunction "2_2") (pintype "passive"))
      (node (ref "R57") (pin "2") (pinfunction "2_2") (pintype "passive"))
    )
    (net (code "77") (name "Net-(JP81-Pad1)") (class "Default")
      (node (ref "JP81") (pin "1") (pinfunction "1_1") (pintype "passive"))
      (node (ref "JP81") (pin "2") (pinfunction "2_2") (pintype "passive"))
      (node (ref "R58") (pin "2") (pinfunction "2_2") (pintype "passive"))
    )
    (net (code "78") (name "Net-(JP82-Pad1)") (class "Default")
      (node (ref "JP82") (pin "1") (pinfunction "1_1") (pintype "passive"))
      (node (ref "JP82") (pin "2") (pinfunction "2_2") (pintype "passive"))
      (node (ref "R59") (pin "2") (pinfunction "2_2") (pintype "passive"))
    )
    (net (code "79") (name "Net-(JP83-Pad1)") (class "Default")
      (node (ref "JP83") (pin "1") (pinfunction "1_1") (pintype "passive"))
      (node (ref "JP83") (pin "2") (pinfunction "2_2") (pintype "passive"))
      (node (ref "R60") (pin "2") (pinfunction "2_2") (pintype "passive"))
    )
    (net (code "80") (name "Net-(JP84-Pad1)") (class "Default")
      (node (ref "JP84") (pin "1") (pinfunction "1_1") (pintype "passive"))
      (node (ref "JP84") (pin "2") (pinfunction "2_2") (pintype "passive"))
      (node (ref "R61") (pin "2") (pinfunction "2_2") (pintype "passive"))
    )
    (net (code "81") (name "Net-(JP85-Pad1)") (class "Default")
      (node (ref "JP85") (pin "1") (pinfunction "1_1") (pintype "passive"))
      (node (ref "JP85") (pin "2") (pinfunction "2_2") (pintype "passive"))
      (node (ref "R33") (pin "2") (pinfunction "2_2") (pintype "passive"))
    )
    (net (code "82") (name "Net-(JP86-Pad1)") (class "Default")
      (node (ref "JP86") (pin "1") (pinfunction "1_1") (pintype "passive"))
      (node (ref "JP86") (pin "2") (pinfunction "2_2") (pintype "passive"))
      (node (ref "R34") (pin "2") (pinfunction "2_2") (pintype "passive"))
    )
    (net (code "83") (name "Net-(JP87-Pad1)") (class "Default")
      (node (ref "JP87") (pin "1") (pinfunction "1_1") (pintype "passive"))
      (node (ref "JP87") (pin "2") (pinfunction "2_2") (pintype "passive"))
      (node (ref "R35") (pin "2") (pinfunction "2_2") (pintype "passive"))
    )
    (net (code "84") (name "Net-(JP88-Pad1)") (class "Default")
      (node (ref "JP88") (pin "1") (pinfunction "1_1") (pintype "passive"))
      (node (ref "JP88") (pin "2") (pinfunction "2_2") (pintype "passive"))
      (node (ref "R36") (pin "2") (pinfunction "2_2") (pintype "passive"))
    )
    (net (code "85") (name "Net-(JP89-Pad1)") (class "Default")
      (node (ref "JP89") (pin "1") (pinfunction "1_1") (pintype "passive"))
      (node (ref "JP89") (pin "2") (pinfunction "2_2") (pintype "passive"))
      (node (ref "R37") (pin "2") (pinfunction "2_2") (pintype "passive"))
    )
    (net (code "86") (name "Net-(JP90-Pad1)") (class "Default")
      (node (ref "JP90") (pin "1") (pinfunction "1_1") (pintype "passive"))
      (node (ref "JP90") (pin "2") (pinfunction "2_2") (pintype "passive"))
      (node (ref "R38") (pin "2") (pinfunction "2_2") (pintype "passive"))
    )
    (net (code "87") (name "Net-(JP91-Pad1)") (class "Default")
      (node (ref "JP91") (pin "1") (pinfunction "1_1") (pintype "passive"))
      (node (ref "JP91") (pin "2") (pinfunction "2_2") (pintype "passive"))
      (node (ref "R39") (pin "2") (pinfunction "2_2") (pintype "passive"))
    )
    (net (code "88") (name "Net-(JP92-Pad1)") (class "Default")
      (node (ref "JP92") (pin "1") (pinfunction "1_1") (pintype "passive"))
      (node (ref "JP92") (pin "2") (pinfunction "2_2") (pintype "passive"))
      (node (ref "R40") (pin "2") (pinfunction "2_2") (pintype "passive"))
    )
    (net (code "89") (name "Net-(JP93-Pad1)") (class "Default")
      (node (ref "JP93") (pin "1") (pinfunction "1_1") (pintype "passive"))
      (node (ref "JP93") (pin "2") (pinfunction "2_2") (pintype "passive"))
      (node (ref "R41") (pin "2") (pinfunction "2_2") (pintype "passive"))
    )
    (net (code "90") (name "Net-(JP94-Pad1)") (class "Default")
      (node (ref "JP94") (pin "1") (pinfunction "1_1") (pintype "passive"))
      (node (ref "JP94") (pin "2") (pinfunction "2_2") (pintype "passive"))
      (node (ref "R42") (pin "2") (pinfunction "2_2") (pintype "passive"))
    )
    (net (code "91") (name "Net-(JP95-Pad1)") (class "Default")
      (node (ref "JP95") (pin "1") (pinfunction "1_1") (pintype "passive"))
      (node (ref "JP95") (pin "2") (pinfunction "2_2") (pintype "passive"))
      (node (ref "R43") (pin "2") (pinfunction "2_2") (pintype "passive"))
    )
    (net (code "92") (name "Net-(JP96-Pad1)") (class "Default")
      (node (ref "JP96") (pin "1") (pinfunction "1_1") (pintype "passive"))
      (node (ref "JP96") (pin "2") (pinfunction "2_2") (pintype "passive"))
      (node (ref "R44") (pin "2") (pinfunction "2_2") (pintype "passive"))
    )
    (net (code "93") (name "Net-(JP97-Pad1)") (class "Default")
      (node (ref "JP97") (pin "1") (pinfunction "1_1") (pintype "passive"))
      (node (ref "JP97") (pin "2") (pinfunction "2_2") (pintype "passive"))
      (node (ref "R45") (pin "2") (pinfunction "2_2") (pintype "passive"))
    )
    (net (code "94") (name "Net-(JP111-Pad1)") (class "Default")
      (node (ref "JP111") (pin "1") (pinfunction "1_1") (pintype "passive"))
      (node (ref "U2") (pin "8") (pinfunction "8_8") (pintype "bidirectional"))
    )
    (net (code "95") (name "Net-(JP111-Pad2)") (class "Default")
      (node (ref "JP111") (pin "2") (pinfunction "2_2") (pintype "passive"))
      (node (ref "U2") (pin "7") (pinfunction "7_7") (pintype "bidirectional"))
    )
    (net (code "96") (name "Net-(JP111-Pad3)") (class "Default")
      (node (ref "JP111") (pin "3") (pinfunction "3_3") (pintype "passive"))
      (node (ref "U2") (pin "6") (pinfunction "6_6") (pintype "bidirectional"))
    )
    (net (code "97") (name "Net-(JP111-Pad4)") (class "Default")
      (node (ref "JP111") (pin "4") (pinfunction "4_4") (pintype "passive"))
      (node (ref "U2") (pin "5") (pinfunction "5_5") (pintype "bidirectional"))
    )
    (net (code "98") (name "Net-(JP112-Pad1)") (class "Default")
      (node (ref "JP112") (pin "1") (pinfunction "1_1") (pintype "passive"))
      (node (ref "U3") (pin "8") (pinfunction "8_8") (pintype "bidirectional"))
    )
    (net (code "99") (name "Net-(JP112-Pad2)") (class "Default")
      (node (ref "JP112") (pin "2") (pinfunction "2_2") (pintype "passive"))
      (node (ref "U3") (pin "7") (pinfunction "7_7") (pintype "bidirectional"))
    )
    (net (code "100") (name "Net-(JP112-Pad3)") (class "Default")
      (node (ref "JP112") (pin "3") (pinfunction "3_3") (pintype "passive"))
      (node (ref "U3") (pin "6") (pinfunction "6_6") (pintype "bidirectional"))
    )
    (net (code "101") (name "Net-(JP112-Pad4)") (class "Default")
      (node (ref "JP112") (pin "4") (pinfunction "4_4") (pintype "passive"))
      (node (ref "U3") (pin "5") (pinfunction "5_5") (pintype "bidirectional"))
    )
    (net (code "102") (name "Net-(JP113-Pad1)") (class "Default")
      (node (ref "JP113") (pin "1") (pinfunction "1_1") (pintype "passive"))
      (node (ref "U1") (pin "4") (pinfunction "4_4") (pintype "bidirectional"))
    )
    (net (code "103") (name "Net-(JP113-Pad2)") (class "Default")
      (node (ref "JP113") (pin "2") (pinfunction "2_2") (pintype "passive"))
      (node (ref "U1") (pin "3") (pinfunction "3_3") (pintype "bidirectional"))
    )
    (net (code "104") (name "Net-(JP113-Pad3)") (class "Default")
      (node (ref "JP113") (pin "3") (pinfunction "3_3") (pintype "passive"))
      (node (ref "U1") (pin "2") (pinfunction "2_2") (pintype "bidirectional"))
    )
    (net (code "105") (name "Net-(JP113-Pad4)") (class "Default")
      (node (ref "JP113") (pin "4") (pinfunction "4_4") (pintype "passive"))
      (node (ref "U1") (pin "1") (pinfunction "1_1") (pintype "bidirectional"))
    )
    (net (code "106") (name "Net-(JP114-Pad1)") (class "Default")
      (node (ref "JP114") (pin "1") (pinfunction "1_1") (pintype "passive"))
      (node (ref "U1") (pin "8") (pinfunction "8_8") (pintype "bidirectional"))
    )
    (net (code "107") (name "Net-(JP114-Pad2)") (class "Default")
      (node (ref "JP114") (pin "2") (pinfunction "2_2") (pintype "passive"))
      (node (ref "U1") (pin "7") (pinfunction "7_7") (pintype "bidirectional"))
    )
    (net (code "108") (name "Net-(JP114-Pad3)") (class "Default")
      (node (ref "JP114") (pin "3") (pinfunction "3_3") (pintype "passive"))
      (node (ref "U1") (pin "6") (pinfunction "6_6") (pintype "bidirectional"))
    )
    (net (code "109") (name "Net-(JP114-Pad4)") (class "Default")
      (node (ref "JP114") (pin "4") (pinfunction "4_4") (pintype "passive"))
      (node (ref "U1") (pin "5") (pinfunction "5_5") (pintype "bidirectional"))
    )
    (net (code "110") (name "Net-(JP115-Pad1)") (class "Default")
      (node (ref "JP115") (pin "1") (pinfunction "1_1") (pintype "passive"))
      (node (ref "U4") (pin "8") (pinfunction "8_8") (pintype "bidirectional"))
    )
    (net (code "111") (name "Net-(JP115-Pad2)") (class "Default")
      (node (ref "JP115") (pin "2") (pinfunction "2_2") (pintype "passive"))
      (node (ref "U4") (pin "7") (pinfunction "7_7") (pintype "bidirectional"))
    )
    (net (code "112") (name "Net-(JP115-Pad3)") (class "Default")
      (node (ref "JP115") (pin "3") (pinfunction "3_3") (pintype "passive"))
      (node (ref "U4") (pin "6") (pinfunction "6_6") (pintype "bidirectional"))
    )
    (net (code "113") (name "Net-(JP115-Pad4)") (class "Default")
      (node (ref "JP115") (pin "4") (pinfunction "4_4") (pintype "passive"))
      (node (ref "U4") (pin "5") (pinfunction "5_5") (pintype "bidirectional"))
    )
    (net (code "114") (name "Net-(JP116-Pad1)") (class "Default")
      (node (ref "JP116") (pin "1") (pinfunction "1_1") (pintype "passive"))
      (node (ref "U2") (pin "4") (pinfunction "4_4") (pintype "bidirectional"))
    )
    (net (code "115") (name "Net-(JP116-Pad2)") (class "Default")
      (node (ref "JP116") (pin "2") (pinfunction "2_2") (pintype "passive"))
      (node (ref "U2") (pin "3") (pinfunction "3_3") (pintype "bidirectional"))
    )
    (net (code "116") (name "Net-(JP116-Pad3)") (class "Default")
      (node (ref "JP116") (pin "3") (pinfunction "3_3") (pintype "passive"))
      (node (ref "U2") (pin "2") (pinfunction "2_2") (pintype "bidirectional"))
    )
    (net (code "117") (name "Net-(JP116-Pad4)") (class "Default")
      (node (ref "JP116") (pin "4") (pinfunction "4_4") (pintype "passive"))
      (node (ref "U2") (pin "1") (pinfunction "1_1") (pintype "bidirectional"))
    )
    (net (code "118") (name "Net-(JP117-Pad1)") (class "Default")
      (node (ref "JP117") (pin "1") (pinfunction "1_1") (pintype "passive"))
      (node (ref "U3") (pin "4") (pinfunction "4_4") (pintype "bidirectional"))
    )
    (net (code "119") (name "Net-(JP117-Pad2)") (class "Default")
      (node (ref "JP117") (pin "2") (pinfunction "2_2") (pintype "passive"))
      (node (ref "U3") (pin "3") (pinfunction "3_3") (pintype "bidirectional"))
    )
    (net (code "120") (name "Net-(JP117-Pad3)") (class "Default")
      (node (ref "JP117") (pin "3") (pinfunction "3_3") (pintype "passive"))
      (node (ref "U3") (pin "2") (pinfunction "2_2") (pintype "bidirectional"))
    )
    (net (code "121") (name "Net-(JP117-Pad4)") (class "Default")
      (node (ref "JP117") (pin "4") (pinfunction "4_4") (pintype "passive"))
      (node (ref "U3") (pin "1") (pinfunction "1_1") (pintype "bidirectional"))
    )
    (net (code "122") (name "Net-(JP118-Pad1)") (class "Default")
      (node (ref "JP118") (pin "1") (pinfunction "1_1") (pintype "passive"))
      (node (ref "U4") (pin "4") (pinfunction "4_4") (pintype "bidirectional"))
    )
    (net (code "123") (name "Net-(JP118-Pad2)") (class "Default")
      (node (ref "JP118") (pin "2") (pinfunction "2_2") (pintype "passive"))
      (node (ref "U4") (pin "3") (pinfunction "3_3") (pintype "bidirectional"))
    )
    (net (code "124") (name "Net-(JP118-Pad3)") (class "Default")
      (node (ref "JP118") (pin "3") (pinfunction "3_3") (pintype "passive"))
      (node (ref "U4") (pin "2") (pinfunction "2_2") (pintype "bidirectional"))
    )
    (net (code "125") (name "Net-(JP118-Pad4)") (class "Default")
      (node (ref "JP118") (pin "4") (pinfunction "4_4") (pintype "passive"))
      (node (ref "U4") (pin "1") (pinfunction "1_1") (pintype "bidirectional"))
    )
    (net (code "126") (name "Net-(R2-Pad2)") (class "Default")
      (node (ref "R2") (pin "2") (pinfunction "2_2") (pintype "passive"))
      (node (ref "R3") (pin "1") (pinfunction "1_1") (pintype "passive"))
    )
    (net (code "127") (name "Net-(R4-Pad1)") (class "Default")
      (node (ref "R4") (pin "1") (pinfunction "1_1") (pintype "passive"))
      (node (ref "R5") (pin "2") (pinfunction "2_2") (pintype "passive"))
    )
    (net (code "128") (name "Net-(R6-Pad1)") (class "Default")
      (node (ref "R6") (pin "1") (pinfunction "1_1") (pintype "passive"))
      (node (ref "R7") (pin "2") (pinfunction "2_2") (pintype "passive"))
    )
    (net (code "129") (name "Net-(R8-Pad1)") (class "Default")
      (node (ref "R8") (pin "1") (pinfunction "1_1") (pintype "passive"))
      (node (ref "R9") (pin "2") (pinfunction "2_2") (pintype "passive"))
    )
    (net (code "130") (name "Net-(R10-Pad2)") (class "Default")
      (node (ref "R10") (pin "2") (pinfunction "2_2") (pintype "passive"))
      (node (ref "R11") (pin "1") (pinfunction "1_1") (pintype "passive"))
    )
    (net (code "131") (name "Net-(R12-Pad2)") (class "Default")
      (node (ref "R12") (pin "2") (pinfunction "2_2") (pintype "passive"))
      (node (ref "R13") (pin "1") (pinfunction "1_1") (pintype "passive"))
    )
    (net (code "132") (name "Net-(R14-Pad2)") (class "Default")
      (node (ref "R14") (pin "2") (pinfunction "2_2") (pintype "passive"))
      (node (ref "R15") (pin "1") (pinfunction "1_1") (pintype "passive"))
    )
    (net (code "133") (name "Net-(R16-Pad2)") (class "Default")
      (node (ref "R16") (pin "2") (pinfunction "2_2") (pintype "passive"))
      (node (ref "R17") (pin "1") (pinfunction "1_1") (pintype "passive"))
    )
    (net (code "134") (name "Net-(R18-Pad2)") (class "Default")
      (node (ref "R18") (pin "2") (pinfunction "2_2") (pintype "passive"))
      (node (ref "R19") (pin "1") (pinfunction "1_1") (pintype "passive"))
    )
    (net (code "135") (name "Net-(R22-Pad2)") (class "Default")
      (node (ref "R22") (pin "2") (pinfunction "2_2") (pintype "passive"))
      (node (ref "R23") (pin "1") (pinfunction "1_1") (pintype "passive"))
    )
    (net (code "136") (name "Net-(R24-Pad2)") (class "Default")
      (node (ref "R24") (pin "2") (pinfunction "2_2") (pintype "passive"))
      (node (ref "R25") (pin "2") (pinfunction "2_2") (pintype "passive"))
    )
    (net (code "137") (name "Net-(R26-Pad2)") (class "Default")
      (node (ref "R26") (pin "2") (pinfunction "2_2") (pintype "passive"))
      (node (ref "R27") (pin "2") (pinfunction "2_2") (pintype "passive"))
    )
    (net (code "138") (name "RESET") (class "Default")
      (node (ref "IC2") (pin "#RESET") (pinfunction "RESET_#RESET") (pintype "bidirectional"))
      (node (ref "IC2") (pin "@RESET") (pinfunction "RESET_@RESET") (pintype "bidirectional"))
      (node (ref "IC2") (pin "RESET") (pinfunction "RESET_RESET") (pintype "bidirectional"))
    )
    (net (code "139") (name "RXC") (class "Default")
      (node (ref "IC2") (pin "#RX") (pinfunction "RX_#RX") (pintype "bidirectional"))
      (node (ref "IC2") (pin "@RX") (pinfunction "RX_@RX") (pintype "bidirectional"))
      (node (ref "IC2") (pin "RX") (pinfunction "RX_RX") (pintype "bidirectional"))
      (node (ref "JP12") (pin "1") (pinfunction "1_1") (pintype "passive"))
      (node (ref "JP12") (pin "2") (pinfunction "2_2") (pintype "passive"))
      (node (ref "JP12") (pin "3") (pinfunction "3_3") (pintype "passive"))
      (node (ref "JP12") (pin "4") (pinfunction "4_4") (pintype "passive"))
      (node (ref "JP12") (pin "5") (pinfunction "5_5") (pintype "passive"))
      (node (ref "JP12") (pin "6") (pinfunction "6_6") (pintype "passive"))
      (node (ref "JP12") (pin "7") (pinfunction "7_7") (pintype "passive"))
      (node (ref "JP12") (pin "8") (pinfunction "8_8") (pintype "passive"))
    )
    (net (code "140") (name "SCK") (class "Default")
      (node (ref "IC2") (pin "#SCK") (pinfunction "SCK_#SCK") (pintype "bidirectional"))
      (node (ref "IC2") (pin "@SCK") (pinfunction "SCK_@SCK") (pintype "bidirectional"))
      (node (ref "IC2") (pin "SCK") (pinfunction "SCK_SCK") (pintype "bidirectional"))
      (node (ref "JP104") (pin "1") (pinfunction "1_1") (pintype "passive"))
      (node (ref "JP104") (pin "2") (pinfunction "2_2") (pintype "passive"))
      (node (ref "JP104") (pin "3") (pinfunction "3_3") (pintype "passive"))
      (node (ref "JP104") (pin "4") (pinfunction "4_4") (pintype "passive"))
      (node (ref "JP104") (pin "5") (pinfunction "5_5") (pintype "passive"))
      (node (ref "JP104") (pin "6") (pinfunction "6_6") (pintype "passive"))
      (node (ref "JP104") (pin "7") (pinfunction "7_7") (pintype "passive"))
      (node (ref "JP104") (pin "8") (pinfunction "8_8") (pintype "passive"))
    )
    (net (code "141") (name "SCL") (class "Default")
      (node (ref "IC2") (pin "#SCL") (pinfunction "SCL_#SCL") (pintype "bidirectional"))
      (node (ref "IC2") (pin "@SCL") (pinfunction "SCL_@SCL") (pintype "bidirectional"))
      (node (ref "IC2") (pin "SCL") (pinfunction "SCL_SCL") (pintype "bidirectional"))
      (node (ref "JP107") (pin "1") (pinfunction "1_1") (pintype "passive"))
      (node (ref "JP107") (pin "2") (pinfunction "2_2") (pintype "passive"))
      (node (ref "JP107") (pin "3") (pinfunction "3_3") (pintype "passive"))
      (node (ref "JP107") (pin "4") (pinfunction "4_4") (pintype "passive"))
      (node (ref "JP107") (pin "5") (pinfunction "5_5") (pintype "passive"))
      (node (ref "JP107") (pin "6") (pinfunction "6_6") (pintype "passive"))
      (node (ref "JP107") (pin "7") (pinfunction "7_7") (pintype "passive"))
      (node (ref "JP107") (pin "8") (pinfunction "8_8") (pintype "passive"))
      (node (ref "R64") (pin "1") (pinfunction "1_1") (pintype "passive"))
    )
    (net (code "142") (name "SDA") (class "Default")
      (node (ref "IC2") (pin "#SDA") (pinfunction "SDA_#SDA") (pintype "bidirectional"))
      (node (ref "IC2") (pin "@SDA") (pinfunction "SDA_@SDA") (pintype "bidirectional"))
      (node (ref "IC2") (pin "SDA") (pinfunction "SDA_SDA") (pintype "bidirectional"))
      (node (ref "JP106") (pin "1") (pinfunction "1_1") (pintype "passive"))
      (node (ref "JP106") (pin "2") (pinfunction "2_2") (pintype "passive"))
      (node (ref "JP106") (pin "3") (pinfunction "3_3") (pintype "passive"))
      (node (ref "JP106") (pin "4") (pinfunction "4_4") (pintype "passive"))
      (node (ref "JP106") (pin "5") (pinfunction "5_5") (pintype "passive"))
      (node (ref "JP106") (pin "6") (pinfunction "6_6") (pintype "passive"))
      (node (ref "JP106") (pin "7") (pinfunction "7_7") (pintype "passive"))
      (node (ref "JP106") (pin "8") (pinfunction "8_8") (pintype "passive"))
      (node (ref "R65") (pin "1") (pinfunction "1_1") (pintype "passive"))
    )
    (net (code "143") (name "TXC") (class "Default")
      (node (ref "IC2") (pin "#TX") (pinfunction "TX_#TX") (pintype "bidirectional"))
      (node (ref "IC2") (pin "@TX") (pinfunction "TX_@TX") (pintype "bidirectional"))
      (node (ref "IC2") (pin "TX") (pinfunction "TX_TX") (pintype "bidirectional"))
      (node (ref "JP17") (pin "1") (pinfunction "1_1") (pintype "passive"))
      (node (ref "JP17") (pin "2") (pinfunction "2_2") (pintype "passive"))
      (node (ref "JP17") (pin "3") (pinfunction "3_3") (pintype "passive"))
      (node (ref "JP17") (pin "4") (pinfunction "4_4") (pintype "passive"))
      (node (ref "JP17") (pin "5") (pinfunction "5_5") (pintype "passive"))
      (node (ref "JP17") (pin "6") (pinfunction "6_6") (pintype "passive"))
      (node (ref "JP17") (pin "7") (pinfunction "7_7") (pintype "passive"))
      (node (ref "JP17") (pin "8") (pinfunction "8_8") (pintype "passive"))
    )
    (net (code "144") (name "VIN") (class "Default")
      (node (ref "C2") (pin "1") (pinfunction "1_1") (pintype "passive"))
      (node (ref "IC1") (pin "OUT") (pinfunction "OUT_OUT") (pintype "passive"))
      (node (ref "IC2") (pin "#VIN") (pinfunction "VIN_#VIN") (pintype "input"))
      (node (ref "IC2") (pin "@VIN") (pinfunction "VIN_@VIN") (pintype "input"))
      (node (ref "IC2") (pin "VIN") (pinfunction "VIN_VIN") (pintype "input"))
      (node (ref "JP3") (pin "1") (pinfunction "1_1") (pintype "passive"))
      (node (ref "JP3") (pin "2") (pinfunction "2_2") (pintype "passive"))
      (node (ref "JP3") (pin "3") (pinfunction "3_3") (pintype "passive"))
      (node (ref "JP3") (pin "4") (pinfunction "4_4") (pintype "passive"))
    )
    (net (code "145") (name "unconnected-(JP35-Pad2)") (class "Default")
      (node (ref "JP35") (pin "2") (pinfunction "2_2") (pintype "passive"))
    )
    (net (code "146") (name "unconnected-(JP35-Pad3)") (class "Default")
      (node (ref "JP35") (pin "3") (pinfunction "3_3") (pintype "passive"))
    )
    (net (code "147") (name "unconnected-(JP35-Pad4)") (class "Default")
      (node (ref "JP35") (pin "4") (pinfunction "4_4") (pintype "passive"))
    )
    (net (code "148") (name "unconnected-(JP35-Pad5)") (class "Default")
      (node (ref "JP35") (pin "5") (pinfunction "5_5") (pintype "passive"))
    )
    (net (code "149") (name "unconnected-(JP35-Pad6)") (class "Default")
      (node (ref "JP35") (pin "6") (pinfunction "6_6") (pintype "passive"))
    )
    (net (code "150") (name "unconnected-(JP35-Pad7)") (class "Default")
      (node (ref "JP35") (pin "7") (pinfunction "7_7") (pintype "passive"))
    )
    (net (code "151") (name "unconnected-(JP35-Pad8)") (class "Default")
      (node (ref "JP35") (pin "8") (pinfunction "8_8") (pintype "passive"))
    )
    (net (code "152") (name "unconnected-(JP35-Pad9)") (class "Default")
      (node (ref "JP35") (pin "9") (pinfunction "9_9") (pintype "passive"))
    )
    (net (code "153") (name "unconnected-(JP35-Pad10)") (class "Default")
      (node (ref "JP35") (pin "10") (pinfunction "10_10") (pintype "passive"))
    )
    (net (code "154") (name "unconnected-(JP35-Pad11)") (class "Default")
      (node (ref "JP35") (pin "11") (pinfunction "11_11") (pintype "passive"))
    )
    (net (code "155") (name "unconnected-(JP35-Pad12)") (class "Default")
      (node (ref "JP35") (pin "12") (pinfunction "12_12") (pintype "passive"))
    )
    (net (code "156") (name "unconnected-(JP35-Pad13)") (class "Default")
      (node (ref "JP35") (pin "13") (pinfunction "13_13") (pintype "passive"))
    )
    (net (code "157") (name "unconnected-(JP35-Pad14)") (class "Default")
      (node (ref "JP35") (pin "14") (pinfunction "14_14") (pintype "passive"))
    )
    (net (code "158") (name "unconnected-(JP35-Pad15)") (class "Default")
      (node (ref "JP35") (pin "15") (pinfunction "15_15") (pintype "passive"))
    )
    (net (code "159") (name "unconnected-(JP35-Pad16)") (class "Default")
      (node (ref "JP35") (pin "16") (pinfunction "16_16") (pintype "passive"))
    )
    (net (code "160") (name "unconnected-(JP36-Pad2)") (class "Default")
      (node (ref "JP36") (pin "2") (pinfunction "2_2") (pintype "passive"))
    )
    (net (code "161") (name "unconnected-(JP36-Pad3)") (class "Default")
      (node (ref "JP36") (pin "3") (pinfunction "3_3") (pintype "passive"))
    )
    (net (code "162") (name "unconnected-(JP36-Pad4)") (class "Default")
      (node (ref "JP36") (pin "4") (pinfunction "4_4") (pintype "passive"))
    )
    (net (code "163") (name "unconnected-(JP36-Pad5)") (class "Default")
      (node (ref "JP36") (pin "5") (pinfunction "5_5") (pintype "passive"))
    )
    (net (code "164") (name "unconnected-(JP36-Pad6)") (class "Default")
      (node (ref "JP36") (pin "6") (pinfunction "6_6") (pintype "passive"))
    )
    (net (code "165") (name "unconnected-(JP36-Pad7)") (class "Default")
      (node (ref "JP36") (pin "7") (pinfunction "7_7") (pintype "passive"))
    )
    (net (code "166") (name "unconnected-(JP36-Pad8)") (class "Default")
      (node (ref "JP36") (pin "8") (pinfunction "8_8") (pintype "passive"))
    )
    (net (code "167") (name "unconnected-(JP36-Pad9)") (class "Default")
      (node (ref "JP36") (pin "9") (pinfunction "9_9") (pintype "passive"))
    )
    (net (code "168") (name "unconnected-(JP36-Pad10)") (class "Default")
      (node (ref "JP36") (pin "10") (pinfunction "10_10") (pintype "passive"))
    )
    (net (code "169") (name "unconnected-(JP36-Pad11)") (class "Default")
      (node (ref "JP36") (pin "11") (pinfunction "11_11") (pintype "passive"))
    )
    (net (code "170") (name "unconnected-(JP36-Pad12)") (class "Default")
      (node (ref "JP36") (pin "12") (pinfunction "12_12") (pintype "passive"))
    )
    (net (code "171") (name "unconnected-(JP36-Pad13)") (class "Default")
      (node (ref "JP36") (pin "13") (pinfunction "13_13") (pintype "passive"))
    )
    (net (code "172") (name "unconnected-(JP36-Pad14)") (class "Default")
      (node (ref "JP36") (pin "14") (pinfunction "14_14") (pintype "passive"))
    )
    (net (code "173") (name "unconnected-(JP36-Pad15)") (class "Default")
      (node (ref "JP36") (pin "15") (pinfunction "15_15") (pintype "passive"))
    )
    (net (code "174") (name "unconnected-(JP36-Pad16)") (class "Default")
      (node (ref "JP36") (pin "16") (pinfunction "16_16") (pintype "passive"))
    )
    (net (code "175") (name "unconnected-(JP37-Pad2)") (class "Default")
      (node (ref "JP37") (pin "2") (pinfunction "2_2") (pintype "passive"))
    )
    (net (code "176") (name "unconnected-(JP37-Pad3)") (class "Default")
      (node (ref "JP37") (pin "3") (pinfunction "3_3") (pintype "passive"))
    )
    (net (code "177") (name "unconnected-(JP37-Pad4)") (class "Default")
      (node (ref "JP37") (pin "4") (pinfunction "4_4") (pintype "passive"))
    )
    (net (code "178") (name "unconnected-(JP37-Pad5)") (class "Default")
      (node (ref "JP37") (pin "5") (pinfunction "5_5") (pintype "passive"))
    )
    (net (code "179") (name "unconnected-(JP37-Pad6)") (class "Default")
      (node (ref "JP37") (pin "6") (pinfunction "6_6") (pintype "passive"))
    )
    (net (code "180") (name "unconnected-(JP37-Pad7)") (class "Default")
      (node (ref "JP37") (pin "7") (pinfunction "7_7") (pintype "passive"))
    )
    (net (code "181") (name "unconnected-(JP37-Pad8)") (class "Default")
      (node (ref "JP37") (pin "8") (pinfunction "8_8") (pintype "passive"))
    )
    (net (code "182") (name "unconnected-(JP37-Pad9)") (class "Default")
      (node (ref "JP37") (pin "9") (pinfunction "9_9") (pintype "passive"))
    )
    (net (code "183") (name "unconnected-(JP37-Pad10)") (class "Default")
      (node (ref "JP37") (pin "10") (pinfunction "10_10") (pintype "passive"))
    )
    (net (code "184") (name "unconnected-(JP37-Pad11)") (class "Default")
      (node (ref "JP37") (pin "11") (pinfunction "11_11") (pintype "passive"))
    )
    (net (code "185") (name "unconnected-(JP37-Pad12)") (class "Default")
      (node (ref "JP37") (pin "12") (pinfunction "12_12") (pintype "passive"))
    )
    (net (code "186") (name "unconnected-(JP37-Pad13)") (class "Default")
      (node (ref "JP37") (pin "13") (pinfunction "13_13") (pintype "passive"))
    )
    (net (code "187") (name "unconnected-(JP37-Pad14)") (class "Default")
      (node (ref "JP37") (pin "14") (pinfunction "14_14") (pintype "passive"))
    )
    (net (code "188") (name "unconnected-(JP37-Pad15)") (class "Default")
      (node (ref "JP37") (pin "15") (pinfunction "15_15") (pintype "passive"))
    )
    (net (code "189") (name "unconnected-(JP37-Pad16)") (class "Default")
      (node (ref "JP37") (pin "16") (pinfunction "16_16") (pintype "passive"))
    )
    (net (code "190") (name "unconnected-(JP40-Pad2)") (class "Default")
      (node (ref "JP40") (pin "2") (pinfunction "2_2") (pintype "passive"))
    )
    (net (code "191") (name "unconnected-(JP40-Pad3)") (class "Default")
      (node (ref "JP40") (pin "3") (pinfunction "3_3") (pintype "passive"))
    )
    (net (code "192") (name "unconnected-(JP40-Pad4)") (class "Default")
      (node (ref "JP40") (pin "4") (pinfunction "4_4") (pintype "passive"))
    )
    (net (code "193") (name "unconnected-(JP40-Pad5)") (class "Default")
      (node (ref "JP40") (pin "5") (pinfunction "5_5") (pintype "passive"))
    )
    (net (code "194") (name "unconnected-(JP40-Pad6)") (class "Default")
      (node (ref "JP40") (pin "6") (pinfunction "6_6") (pintype "passive"))
    )
    (net (code "195") (name "unconnected-(JP40-Pad7)") (class "Default")
      (node (ref "JP40") (pin "7") (pinfunction "7_7") (pintype "passive"))
    )
    (net (code "196") (name "unconnected-(JP40-Pad8)") (class "Default")
      (node (ref "JP40") (pin "8") (pinfunction "8_8") (pintype "passive"))
    )
    (net (code "197") (name "unconnected-(JP40-Pad9)") (class "Default")
      (node (ref "JP40") (pin "9") (pinfunction "9_9") (pintype "passive"))
    )
    (net (code "198") (name "unconnected-(JP40-Pad10)") (class "Default")
      (node (ref "JP40") (pin "10") (pinfunction "10_10") (pintype "passive"))
    )
    (net (code "199") (name "unconnected-(JP40-Pad11)") (class "Default")
      (node (ref "JP40") (pin "11") (pinfunction "11_11") (pintype "passive"))
    )
    (net (code "200") (name "unconnected-(JP40-Pad12)") (class "Default")
      (node (ref "JP40") (pin "12") (pinfunction "12_12") (pintype "passive"))
    )
    (net (code "201") (name "unconnected-(JP40-Pad13)") (class "Default")
      (node (ref "JP40") (pin "13") (pinfunction "13_13") (pintype "passive"))
    )
    (net (code "202") (name "unconnected-(JP40-Pad14)") (class "Default")
      (node (ref "JP40") (pin "14") (pinfunction "14_14") (pintype "passive"))
    )
    (net (code "203") (name "unconnected-(JP40-Pad15)") (class "Default")
      (node (ref "JP40") (pin "15") (pinfunction "15_15") (pintype "passive"))
    )
    (net (code "204") (name "unconnected-(JP40-Pad16)") (class "Default")
      (node (ref "JP40") (pin "16") (pinfunction "16_16") (pintype "passive"))
    )
    (net (code "205") (name "unconnected-(JP41-Pad2)") (class "Default")
      (node (ref "JP41") (pin "2") (pinfunction "2_2") (pintype "passive"))
    )
    (net (code "206") (name "unconnected-(JP41-Pad3)") (class "Default")
      (node (ref "JP41") (pin "3") (pinfunction "3_3") (pintype "passive"))
    )
    (net (code "207") (name "unconnected-(JP41-Pad4)") (class "Default")
      (node (ref "JP41") (pin "4") (pinfunction "4_4") (pintype "passive"))
    )
    (net (code "208") (name "unconnected-(JP41-Pad5)") (class "Default")
      (node (ref "JP41") (pin "5") (pinfunction "5_5") (pintype "passive"))
    )
    (net (code "209") (name "unconnected-(JP41-Pad6)") (class "Default")
      (node (ref "JP41") (pin "6") (pinfunction "6_6") (pintype "passive"))
    )
    (net (code "210") (name "unconnected-(JP41-Pad7)") (class "Default")
      (node (ref "JP41") (pin "7") (pinfunction "7_7") (pintype "passive"))
    )
    (net (code "211") (name "unconnected-(JP41-Pad8)") (class "Default")
      (node (ref "JP41") (pin "8") (pinfunction "8_8") (pintype "passive"))
    )
    (net (code "212") (name "unconnected-(JP41-Pad9)") (class "Default")
      (node (ref "JP41") (pin "9") (pinfunction "9_9") (pintype "passive"))
    )
    (net (code "213") (name "unconnected-(JP41-Pad10)") (class "Default")
      (node (ref "JP41") (pin "10") (pinfunction "10_10") (pintype "passive"))
    )
    (net (code "214") (name "unconnected-(JP41-Pad11)") (class "Default")
      (node (ref "JP41") (pin "11") (pinfunction "11_11") (pintype "passive"))
    )
    (net (code "215") (name "unconnected-(JP41-Pad12)") (class "Default")
      (node (ref "JP41") (pin "12") (pinfunction "12_12") (pintype "passive"))
    )
    (net (code "216") (name "unconnected-(JP41-Pad13)") (class "Default")
      (node (ref "JP41") (pin "13") (pinfunction "13_13") (pintype "passive"))
    )
    (net (code "217") (name "unconnected-(JP41-Pad14)") (class "Default")
      (node (ref "JP41") (pin "14") (pinfunction "14_14") (pintype "passive"))
    )
    (net (code "218") (name "unconnected-(JP41-Pad15)") (class "Default")
      (node (ref "JP41") (pin "15") (pinfunction "15_15") (pintype "passive"))
    )
    (net (code "219") (name "unconnected-(JP41-Pad16)") (class "Default")
      (node (ref "JP41") (pin "16") (pinfunction "16_16") (pintype "passive"))
    )
    (net (code "220") (name "unconnected-(JP42-Pad2)") (class "Default")
      (node (ref "JP42") (pin "2") (pinfunction "2_2") (pintype "passive"))
    )
    (net (code "221") (name "unconnected-(JP42-Pad3)") (class "Default")
      (node (ref "JP42") (pin "3") (pinfunction "3_3") (pintype "passive"))
    )
    (net (code "222") (name "unconnected-(JP42-Pad4)") (class "Default")
      (node (ref "JP42") (pin "4") (pinfunction "4_4") (pintype "passive"))
    )
    (net (code "223") (name "unconnected-(JP42-Pad5)") (class "Default")
      (node (ref "JP42") (pin "5") (pinfunction "5_5") (pintype "passive"))
    )
    (net (code "224") (name "unconnected-(JP42-Pad6)") (class "Default")
      (node (ref "JP42") (pin "6") (pinfunction "6_6") (pintype "passive"))
    )
    (net (code "225") (name "unconnected-(JP42-Pad7)") (class "Default")
      (node (ref "JP42") (pin "7") (pinfunction "7_7") (pintype "passive"))
    )
    (net (code "226") (name "unconnected-(JP42-Pad8)") (class "Default")
      (node (ref "JP42") (pin "8") (pinfunction "8_8") (pintype "passive"))
    )
    (net (code "227") (name "unconnected-(JP42-Pad9)") (class "Default")
      (node (ref "JP42") (pin "9") (pinfunction "9_9") (pintype "passive"))
    )
    (net (code "228") (name "unconnected-(JP42-Pad10)") (class "Default")
      (node (ref "JP42") (pin "10") (pinfunction "10_10") (pintype "passive"))
    )
    (net (code "229") (name "unconnected-(JP42-Pad11)") (class "Default")
      (node (ref "JP42") (pin "11") (pinfunction "11_11") (pintype "passive"))
    )
    (net (code "230") (name "unconnected-(JP42-Pad12)") (class "Default")
      (node (ref "JP42") (pin "12") (pinfunction "12_12") (pintype "passive"))
    )
    (net (code "231") (name "unconnected-(JP42-Pad13)") (class "Default")
      (node (ref "JP42") (pin "13") (pinfunction "13_13") (pintype "passive"))
    )
    (net (code "232") (name "unconnected-(JP42-Pad14)") (class "Default")
      (node (ref "JP42") (pin "14") (pinfunction "14_14") (pintype "passive"))
    )
    (net (code "233") (name "unconnected-(JP42-Pad15)") (class "Default")
      (node (ref "JP42") (pin "15") (pinfunction "15_15") (pintype "passive"))
    )
    (net (code "234") (name "unconnected-(JP42-Pad16)") (class "Default")
      (node (ref "JP42") (pin "16") (pinfunction "16_16") (pintype "passive"))
    )
    (net (code "235") (name "unconnected-(JP43-Pad2)") (class "Default")
      (node (ref "JP43") (pin "2") (pinfunction "2_2") (pintype "passive"))
    )
    (net (code "236") (name "unconnected-(JP43-Pad3)") (class "Default")
      (node (ref "JP43") (pin "3") (pinfunction "3_3") (pintype "passive"))
    )
    (net (code "237") (name "unconnected-(JP43-Pad4)") (class "Default")
      (node (ref "JP43") (pin "4") (pinfunction "4_4") (pintype "passive"))
    )
    (net (code "238") (name "unconnected-(JP43-Pad5)") (class "Default")
      (node (ref "JP43") (pin "5") (pinfunction "5_5") (pintype "passive"))
    )
    (net (code "239") (name "unconnected-(JP43-Pad6)") (class "Default")
      (node (ref "JP43") (pin "6") (pinfunction "6_6") (pintype "passive"))
    )
    (net (code "240") (name "unconnected-(JP43-Pad7)") (class "Default")
      (node (ref "JP43") (pin "7") (pinfunction "7_7") (pintype "passive"))
    )
    (net (code "241") (name "unconnected-(JP43-Pad8)") (class "Default")
      (node (ref "JP43") (pin "8") (pinfunction "8_8") (pintype "passive"))
    )
    (net (code "242") (name "unconnected-(JP43-Pad9)") (class "Default")
      (node (ref "JP43") (pin "9") (pinfunction "9_9") (pintype "passive"))
    )
    (net (code "243") (name "unconnected-(JP43-Pad10)") (class "Default")
      (node (ref "JP43") (pin "10") (pinfunction "10_10") (pintype "passive"))
    )
    (net (code "244") (name "unconnected-(JP43-Pad11)") (class "Default")
      (node (ref "JP43") (pin "11") (pinfunction "11_11") (pintype "passive"))
    )
    (net (code "245") (name "unconnected-(JP43-Pad12)") (class "Default")
      (node (ref "JP43") (pin "12") (pinfunction "12_12") (pintype "passive"))
    )
    (net (code "246") (name "unconnected-(JP43-Pad13)") (class "Default")
      (node (ref "JP43") (pin "13") (pinfunction "13_13") (pintype "passive"))
    )
    (net (code "247") (name "unconnected-(JP43-Pad14)") (class "Default")
      (node (ref "JP43") (pin "14") (pinfunction "14_14") (pintype "passive"))
    )
    (net (code "248") (name "unconnected-(JP43-Pad15)") (class "Default")
      (node (ref "JP43") (pin "15") (pinfunction "15_15") (pintype "passive"))
    )
    (net (code "249") (name "unconnected-(JP43-Pad16)") (class "Default")
      (node (ref "JP43") (pin "16") (pinfunction "16_16") (pintype "passive"))
    )
    (net (code "250") (name "unconnected-(JP44-Pad2)") (class "Default")
      (node (ref "JP44") (pin "2") (pinfunction "2_2") (pintype "passive"))
    )
    (net (code "251") (name "unconnected-(JP44-Pad3)") (class "Default")
      (node (ref "JP44") (pin "3") (pinfunction "3_3") (pintype "passive"))
    )
    (net (code "252") (name "unconnected-(JP44-Pad4)") (class "Default")
      (node (ref "JP44") (pin "4") (pinfunction "4_4") (pintype "passive"))
    )
    (net (code "253") (name "unconnected-(JP44-Pad5)") (class "Default")
      (node (ref "JP44") (pin "5") (pinfunction "5_5") (pintype "passive"))
    )
    (net (code "254") (name "unconnected-(JP44-Pad6)") (class "Default")
      (node (ref "JP44") (pin "6") (pinfunction "6_6") (pintype "passive"))
    )
    (net (code "255") (name "unconnected-(JP44-Pad7)") (class "Default")
      (node (ref "JP44") (pin "7") (pinfunction "7_7") (pintype "passive"))
    )
    (net (code "256") (name "unconnected-(JP44-Pad8)") (class "Default")
      (node (ref "JP44") (pin "8") (pinfunction "8_8") (pintype "passive"))
    )
    (net (code "257") (name "unconnected-(JP44-Pad9)") (class "Default")
      (node (ref "JP44") (pin "9") (pinfunction "9_9") (pintype "passive"))
    )
    (net (code "258") (name "unconnected-(JP44-Pad10)") (class "Default")
      (node (ref "JP44") (pin "10") (pinfunction "10_10") (pintype "passive"))
    )
    (net (code "259") (name "unconnected-(JP44-Pad11)") (class "Default")
      (node (ref "JP44") (pin "11") (pinfunction "11_11") (pintype "passive"))
    )
    (net (code "260") (name "unconnected-(JP44-Pad12)") (class "Default")
      (node (ref "JP44") (pin "12") (pinfunction "12_12") (pintype "passive"))
    )
    (net (code "261") (name "unconnected-(JP44-Pad13)") (class "Default")
      (node (ref "JP44") (pin "13") (pinfunction "13_13") (pintype "passive"))
    )
    (net (code "262") (name "unconnected-(JP44-Pad14)") (class "Default")
      (node (ref "JP44") (pin "14") (pinfunction "14_14") (pintype "passive"))
    )
    (net (code "263") (name "unconnected-(JP44-Pad15)") (class "Default")
      (node (ref "JP44") (pin "15") (pinfunction "15_15") (pintype "passive"))
    )
    (net (code "264") (name "unconnected-(JP44-Pad16)") (class "Default")
      (node (ref "JP44") (pin "16") (pinfunction "16_16") (pintype "passive"))
    )
    (net (code "265") (name "unconnected-(JP45-Pad2)") (class "Default")
      (node (ref "JP45") (pin "2") (pinfunction "2_2") (pintype "passive"))
    )
    (net (code "266") (name "unconnected-(JP45-Pad3)") (class "Default")
      (node (ref "JP45") (pin "3") (pinfunction "3_3") (pintype "passive"))
    )
    (net (code "267") (name "unconnected-(JP45-Pad4)") (class "Default")
      (node (ref "JP45") (pin "4") (pinfunction "4_4") (pintype "passive"))
    )
    (net (code "268") (name "unconnected-(JP45-Pad5)") (class "Default")
      (node (ref "JP45") (pin "5") (pinfunction "5_5") (pintype "passive"))
    )
    (net (code "269") (name "unconnected-(JP45-Pad6)") (class "Default")
      (node (ref "JP45") (pin "6") (pinfunction "6_6") (pintype "passive"))
    )
    (net (code "270") (name "unconnected-(JP45-Pad7)") (class "Default")
      (node (ref "JP45") (pin "7") (pinfunction "7_7") (pintype "passive"))
    )
    (net (code "271") (name "unconnected-(JP45-Pad8)") (class "Default")
      (node (ref "JP45") (pin "8") (pinfunction "8_8") (pintype "passive"))
    )
    (net (code "272") (name "unconnected-(JP45-Pad9)") (class "Default")
      (node (ref "JP45") (pin "9") (pinfunction "9_9") (pintype "passive"))
    )
    (net (code "273") (name "unconnected-(JP45-Pad10)") (class "Default")
      (node (ref "JP45") (pin "10") (pinfunction "10_10") (pintype "passive"))
    )
    (net (code "274") (name "unconnected-(JP45-Pad11)") (class "Default")
      (node (ref "JP45") (pin "11") (pinfunction "11_11") (pintype "passive"))
    )
    (net (code "275") (name "unconnected-(JP45-Pad12)") (class "Default")
      (node (ref "JP45") (pin "12") (pinfunction "12_12") (pintype "passive"))
    )
    (net (code "276") (name "unconnected-(JP45-Pad13)") (class "Default")
      (node (ref "JP45") (pin "13") (pinfunction "13_13") (pintype "passive"))
    )
    (net (code "277") (name "unconnected-(JP45-Pad14)") (class "Default")
      (node (ref "JP45") (pin "14") (pinfunction "14_14") (pintype "passive"))
    )
    (net (code "278") (name "unconnected-(JP45-Pad15)") (class "Default")
      (node (ref "JP45") (pin "15") (pinfunction "15_15") (pintype "passive"))
    )
    (net (code "279") (name "unconnected-(JP45-Pad16)") (class "Default")
      (node (ref "JP45") (pin "16") (pinfunction "16_16") (pintype "passive"))
    )
    (net (code "280") (name "unconnected-(JP46-Pad2)") (class "Default")
      (node (ref "JP46") (pin "2") (pinfunction "2_2") (pintype "passive"))
    )
    (net (code "281") (name "unconnected-(JP46-Pad3)") (class "Default")
      (node (ref "JP46") (pin "3") (pinfunction "3_3") (pintype "passive"))
    )
    (net (code "282") (name "unconnected-(JP46-Pad4)") (class "Default")
      (node (ref "JP46") (pin "4") (pinfunction "4_4") (pintype "passive"))
    )
    (net (code "283") (name "unconnected-(JP46-Pad5)") (class "Default")
      (node (ref "JP46") (pin "5") (pinfunction "5_5") (pintype "passive"))
    )
    (net (code "284") (name "unconnected-(JP46-Pad6)") (class "Default")
      (node (ref "JP46") (pin "6") (pinfunction "6_6") (pintype "passive"))
    )
    (net (code "285") (name "unconnected-(JP46-Pad7)") (class "Default")
      (node (ref "JP46") (pin "7") (pinfunction "7_7") (pintype "passive"))
    )
    (net (code "286") (name "unconnected-(JP46-Pad8)") (class "Default")
      (node (ref "JP46") (pin "8") (pinfunction "8_8") (pintype "passive"))
    )
    (net (code "287") (name "unconnected-(JP46-Pad9)") (class "Default")
      (node (ref "JP46") (pin "9") (pinfunction "9_9") (pintype "passive"))
    )
    (net (code "288") (name "unconnected-(JP46-Pad10)") (class "Default")
      (node (ref "JP46") (pin "10") (pinfunction "10_10") (pintype "passive"))
    )
    (net (code "289") (name "unconnected-(JP46-Pad11)") (class "Default")
      (node (ref "JP46") (pin "11") (pinfunction "11_11") (pintype "passive"))
    )
    (net (code "290") (name "unconnected-(JP46-Pad12)") (class "Default")
      (node (ref "JP46") (pin "12") (pinfunction "12_12") (pintype "passive"))
    )
    (net (code "291") (name "unconnected-(JP46-Pad13)") (class "Default")
      (node (ref "JP46") (pin "13") (pinfunction "13_13") (pintype "passive"))
    )
    (net (code "292") (name "unconnected-(JP46-Pad14)") (class "Default")
      (node (ref "JP46") (pin "14") (pinfunction "14_14") (pintype "passive"))
    )
    (net (code "293") (name "unconnected-(JP46-Pad15)") (class "Default")
      (node (ref "JP46") (pin "15") (pinfunction "15_15") (pintype "passive"))
    )
    (net (code "294") (name "unconnected-(JP46-Pad16)") (class "Default")
      (node (ref "JP46") (pin "16") (pinfunction "16_16") (pintype "passive"))
    )
    (net (code "295") (name "unconnected-(JP47-Pad2)") (class "Default")
      (node (ref "JP47") (pin "2") (pinfunction "2_2") (pintype "passive"))
    )
    (net (code "296") (name "unconnected-(JP47-Pad3)") (class "Default")
      (node (ref "JP47") (pin "3") (pinfunction "3_3") (pintype "passive"))
    )
    (net (code "297") (name "unconnected-(JP47-Pad4)") (class "Default")
      (node (ref "JP47") (pin "4") (pinfunction "4_4") (pintype "passive"))
    )
    (net (code "298") (name "unconnected-(JP47-Pad5)") (class "Default")
      (node (ref "JP47") (pin "5") (pinfunction "5_5") (pintype "passive"))
    )
    (net (code "299") (name "unconnected-(JP47-Pad6)") (class "Default")
      (node (ref "JP47") (pin "6") (pinfunction "6_6") (pintype "passive"))
    )
    (net (code "300") (name "unconnected-(JP47-Pad7)") (class "Default")
      (node (ref "JP47") (pin "7") (pinfunction "7_7") (pintype "passive"))
    )
    (net (code "301") (name "unconnected-(JP47-Pad8)") (class "Default")
      (node (ref "JP47") (pin "8") (pinfunction "8_8") (pintype "passive"))
    )
    (net (code "302") (name "unconnected-(JP47-Pad9)") (class "Default")
      (node (ref "JP47") (pin "9") (pinfunction "9_9") (pintype "passive"))
    )
    (net (code "303") (name "unconnected-(JP47-Pad10)") (class "Default")
      (node (ref "JP47") (pin "10") (pinfunction "10_10") (pintype "passive"))
    )
    (net (code "304") (name "unconnected-(JP47-Pad11)") (class "Default")
      (node (ref "JP47") (pin "11") (pinfunction "11_11") (pintype "passive"))
    )
    (net (code "305") (name "unconnected-(JP47-Pad12)") (class "Default")
      (node (ref "JP47") (pin "12") (pinfunction "12_12") (pintype "passive"))
    )
    (net (code "306") (name "unconnected-(JP47-Pad13)") (class "Default")
      (node (ref "JP47") (pin "13") (pinfunction "13_13") (pintype "passive"))
    )
    (net (code "307") (name "unconnected-(JP47-Pad14)") (class "Default")
      (node (ref "JP47") (pin "14") (pinfunction "14_14") (pintype "passive"))
    )
    (net (code "308") (name "unconnected-(JP47-Pad15)") (class "Default")
      (node (ref "JP47") (pin "15") (pinfunction "15_15") (pintype "passive"))
    )
    (net (code "309") (name "unconnected-(JP47-Pad16)") (class "Default")
      (node (ref "JP47") (pin "16") (pinfunction "16_16") (pintype "passive"))
    )
    (net (code "310") (name "unconnected-(JP48-Pad2)") (class "Default")
      (node (ref "JP48") (pin "2") (pinfunction "2_2") (pintype "passive"))
    )
    (net (code "311") (name "unconnected-(JP48-Pad3)") (class "Default")
      (node (ref "JP48") (pin "3") (pinfunction "3_3") (pintype "passive"))
    )
    (net (code "312") (name "unconnected-(JP48-Pad4)") (class "Default")
      (node (ref "JP48") (pin "4") (pinfunction "4_4") (pintype "passive"))
    )
    (net (code "313") (name "unconnected-(JP48-Pad5)") (class "Default")
      (node (ref "JP48") (pin "5") (pinfunction "5_5") (pintype "passive"))
    )
    (net (code "314") (name "unconnected-(JP48-Pad6)") (class "Default")
      (node (ref "JP48") (pin "6") (pinfunction "6_6") (pintype "passive"))
    )
    (net (code "315") (name "unconnected-(JP48-Pad7)") (class "Default")
      (node (ref "JP48") (pin "7") (pinfunction "7_7") (pintype "passive"))
    )
    (net (code "316") (name "unconnected-(JP48-Pad8)") (class "Default")
      (node (ref "JP48") (pin "8") (pinfunction "8_8") (pintype "passive"))
    )
    (net (code "317") (name "unconnected-(JP48-Pad9)") (class "Default")
      (node (ref "JP48") (pin "9") (pinfunction "9_9") (pintype "passive"))
    )
    (net (code "318") (name "unconnected-(JP48-Pad10)") (class "Default")
      (node (ref "JP48") (pin "10") (pinfunction "10_10") (pintype "passive"))
    )
    (net (code "319") (name "unconnected-(JP48-Pad11)") (class "Default")
      (node (ref "JP48") (pin "11") (pinfunction "11_11") (pintype "passive"))
    )
    (net (code "320") (name "unconnected-(JP48-Pad12)") (class "Default")
      (node (ref "JP48") (pin "12") (pinfunction "12_12") (pintype "passive"))
    )
    (net (code "321") (name "unconnected-(JP48-Pad13)") (class "Default")
      (node (ref "JP48") (pin "13") (pinfunction "13_13") (pintype "passive"))
    )
    (net (code "322") (name "unconnected-(JP48-Pad14)") (class "Default")
      (node (ref "JP48") (pin "14") (pinfunction "14_14") (pintype "passive"))
    )
    (net (code "323") (name "unconnected-(JP48-Pad15)") (class "Default")
      (node (ref "JP48") (pin "15") (pinfunction "15_15") (pintype "passive"))
    )
    (net (code "324") (name "unconnected-(JP48-Pad16)") (class "Default")
      (node (ref "JP48") (pin "16") (pinfunction "16_16") (pintype "passive"))
    )
    (net (code "325") (name "unconnected-(JP49-Pad2)") (class "Default")
      (node (ref "JP49") (pin "2") (pinfunction "2_2") (pintype "passive"))
    )
    (net (code "326") (name "unconnected-(JP49-Pad3)") (class "Default")
      (node (ref "JP49") (pin "3") (pinfunction "3_3") (pintype "passive"))
    )
    (net (code "327") (name "unconnected-(JP49-Pad4)") (class "Default")
      (node (ref "JP49") (pin "4") (pinfunction "4_4") (pintype "passive"))
    )
    (net (code "328") (name "unconnected-(JP49-Pad5)") (class "Default")
      (node (ref "JP49") (pin "5") (pinfunction "5_5") (pintype "passive"))
    )
    (net (code "329") (name "unconnected-(JP49-Pad6)") (class "Default")
      (node (ref "JP49") (pin "6") (pinfunction "6_6") (pintype "passive"))
    )
    (net (code "330") (name "unconnected-(JP49-Pad7)") (class "Default")
      (node (ref "JP49") (pin "7") (pinfunction "7_7") (pintype "passive"))
    )
    (net (code "331") (name "unconnected-(JP49-Pad8)") (class "Default")
      (node (ref "JP49") (pin "8") (pinfunction "8_8") (pintype "passive"))
    )
    (net (code "332") (name "unconnected-(JP49-Pad9)") (class "Default")
      (node (ref "JP49") (pin "9") (pinfunction "9_9") (pintype "passive"))
    )
    (net (code "333") (name "unconnected-(JP49-Pad10)") (class "Default")
      (node (ref "JP49") (pin "10") (pinfunction "10_10") (pintype "passive"))
    )
    (net (code "334") (name "unconnected-(JP49-Pad11)") (class "Default")
      (node (ref "JP49") (pin "11") (pinfunction "11_11") (pintype "passive"))
    )
    (net (code "335") (name "unconnected-(JP49-Pad12)") (class "Default")
      (node (ref "JP49") (pin "12") (pinfunction "12_12") (pintype "passive"))
    )
    (net (code "336") (name "unconnected-(JP49-Pad13)") (class "Default")
      (node (ref "JP49") (pin "13") (pinfunction "13_13") (pintype "passive"))
    )
    (net (code "337") (name "unconnected-(JP49-Pad14)") (class "Default")
      (node (ref "JP49") (pin "14") (pinfunction "14_14") (pintype "passive"))
    )
    (net (code "338") (name "unconnected-(JP49-Pad15)") (class "Default")
      (node (ref "JP49") (pin "15") (pinfunction "15_15") (pintype "passive"))
    )
    (net (code "339") (name "unconnected-(JP49-Pad16)") (class "Default")
      (node (ref "JP49") (pin "16") (pinfunction "16_16") (pintype "passive"))
    )
    (net (code "340") (name "unconnected-(JP50-Pad2)") (class "Default")
      (node (ref "JP50") (pin "2") (pinfunction "2_2") (pintype "passive"))
    )
    (net (code "341") (name "unconnected-(JP50-Pad3)") (class "Default")
      (node (ref "JP50") (pin "3") (pinfunction "3_3") (pintype "passive"))
    )
    (net (code "342") (name "unconnected-(JP50-Pad4)") (class "Default")
      (node (ref "JP50") (pin "4") (pinfunction "4_4") (pintype "passive"))
    )
    (net (code "343") (name "unconnected-(JP50-Pad5)") (class "Default")
      (node (ref "JP50") (pin "5") (pinfunction "5_5") (pintype "passive"))
    )
    (net (code "344") (name "unconnected-(JP50-Pad6)") (class "Default")
      (node (ref "JP50") (pin "6") (pinfunction "6_6") (pintype "passive"))
    )
    (net (code "345") (name "unconnected-(JP50-Pad7)") (class "Default")
      (node (ref "JP50") (pin "7") (pinfunction "7_7") (pintype "passive"))
    )
    (net (code "346") (name "unconnected-(JP50-Pad8)") (class "Default")
      (node (ref "JP50") (pin "8") (pinfunction "8_8") (pintype "passive"))
    )
    (net (code "347") (name "unconnected-(JP50-Pad9)") (class "Default")
      (node (ref "JP50") (pin "9") (pinfunction "9_9") (pintype "passive"))
    )
    (net (code "348") (name "unconnected-(JP50-Pad10)") (class "Default")
      (node (ref "JP50") (pin "10") (pinfunction "10_10") (pintype "passive"))
    )
    (net (code "349") (name "unconnected-(JP50-Pad11)") (class "Default")
      (node (ref "JP50") (pin "11") (pinfunction "11_11") (pintype "passive"))
    )
    (net (code "350") (name "unconnected-(JP50-Pad12)") (class "Default")
      (node (ref "JP50") (pin "12") (pinfunction "12_12") (pintype "passive"))
    )
    (net (code "351") (name "unconnected-(JP50-Pad13)") (class "Default")
      (node (ref "JP50") (pin "13") (pinfunction "13_13") (pintype "passive"))
    )
    (net (code "352") (name "unconnected-(JP50-Pad14)") (class "Default")
      (node (ref "JP50") (pin "14") (pinfunction "14_14") (pintype "passive"))
    )
    (net (code "353") (name "unconnected-(JP50-Pad15)") (class "Default")
      (node (ref "JP50") (pin "15") (pinfunction "15_15") (pintype "passive"))
    )
    (net (code "354") (name "unconnected-(JP50-Pad16)") (class "Default")
      (node (ref "JP50") (pin "16") (pinfunction "16_16") (pintype "passive"))
    )
    (net (code "355") (name "unconnected-(JP51-Pad2)") (class "Default")
      (node (ref "JP51") (pin "2") (pinfunction "2_2") (pintype "passive"))
    )
    (net (code "356") (name "unconnected-(JP51-Pad3)") (class "Default")
      (node (ref "JP51") (pin "3") (pinfunction "3_3") (pintype "passive"))
    )
    (net (code "357") (name "unconnected-(JP51-Pad4)") (class "Default")
      (node (ref "JP51") (pin "4") (pinfunction "4_4") (pintype "passive"))
    )
    (net (code "358") (name "unconnected-(JP51-Pad5)") (class "Default")
      (node (ref "JP51") (pin "5") (pinfunction "5_5") (pintype "passive"))
    )
    (net (code "359") (name "unconnected-(JP51-Pad6)") (class "Default")
      (node (ref "JP51") (pin "6") (pinfunction "6_6") (pintype "passive"))
    )
    (net (code "360") (name "unconnected-(JP51-Pad7)") (class "Default")
      (node (ref "JP51") (pin "7") (pinfunction "7_7") (pintype "passive"))
    )
    (net (code "361") (name "unconnected-(JP51-Pad8)") (class "Default")
      (node (ref "JP51") (pin "8") (pinfunction "8_8") (pintype "passive"))
    )
    (net (code "362") (name "unconnected-(JP51-Pad9)") (class "Default")
      (node (ref "JP51") (pin "9") (pinfunction "9_9") (pintype "passive"))
    )
    (net (code "363") (name "unconnected-(JP51-Pad10)") (class "Default")
      (node (ref "JP51") (pin "10") (pinfunction "10_10") (pintype "passive"))
    )
    (net (code "364") (name "unconnected-(JP51-Pad11)") (class "Default")
      (node (ref "JP51") (pin "11") (pinfunction "11_11") (pintype "passive"))
    )
    (net (code "365") (name "unconnected-(JP51-Pad12)") (class "Default")
      (node (ref "JP51") (pin "12") (pinfunction "12_12") (pintype "passive"))
    )
    (net (code "366") (name "unconnected-(JP51-Pad13)") (class "Default")
      (node (ref "JP51") (pin "13") (pinfunction "13_13") (pintype "passive"))
    )
    (net (code "367") (name "unconnected-(JP51-Pad14)") (class "Default")
      (node (ref "JP51") (pin "14") (pinfunction "14_14") (pintype "passive"))
    )
    (net (code "368") (name "unconnected-(JP51-Pad15)") (class "Default")
      (node (ref "JP51") (pin "15") (pinfunction "15_15") (pintype "passive"))
    )
    (net (code "369") (name "unconnected-(JP51-Pad16)") (class "Default")
      (node (ref "JP51") (pin "16") (pinfunction "16_16") (pintype "passive"))
    )
    (net (code "370") (name "unconnected-(JP52-Pad2)") (class "Default")
      (node (ref "JP52") (pin "2") (pinfunction "2_2") (pintype "passive"))
    )
    (net (code "371") (name "unconnected-(JP52-Pad3)") (class "Default")
      (node (ref "JP52") (pin "3") (pinfunction "3_3") (pintype "passive"))
    )
    (net (code "372") (name "unconnected-(JP52-Pad4)") (class "Default")
      (node (ref "JP52") (pin "4") (pinfunction "4_4") (pintype "passive"))
    )
    (net (code "373") (name "unconnected-(JP52-Pad5)") (class "Default")
      (node (ref "JP52") (pin "5") (pinfunction "5_5") (pintype "passive"))
    )
    (net (code "374") (name "unconnected-(JP52-Pad6)") (class "Default")
      (node (ref "JP52") (pin "6") (pinfunction "6_6") (pintype "passive"))
    )
    (net (code "375") (name "unconnected-(JP52-Pad7)") (class "Default")
      (node (ref "JP52") (pin "7") (pinfunction "7_7") (pintype "passive"))
    )
    (net (code "376") (name "unconnected-(JP52-Pad8)") (class "Default")
      (node (ref "JP52") (pin "8") (pinfunction "8_8") (pintype "passive"))
    )
    (net (code "377") (name "unconnected-(JP52-Pad9)") (class "Default")
      (node (ref "JP52") (pin "9") (pinfunction "9_9") (pintype "passive"))
    )
    (net (code "378") (name "unconnected-(JP52-Pad10)") (class "Default")
      (node (ref "JP52") (pin "10") (pinfunction "10_10") (pintype "passive"))
    )
    (net (code "379") (name "unconnected-(JP52-Pad11)") (class "Default")
      (node (ref "JP52") (pin "11") (pinfunction "11_11") (pintype "passive"))
    )
    (net (code "380") (name "unconnected-(JP52-Pad12)") (class "Default")
      (node (ref "JP52") (pin "12") (pinfunction "12_12") (pintype "passive"))
    )
    (net (code "381") (name "unconnected-(JP52-Pad13)") (class "Default")
      (node (ref "JP52") (pin "13") (pinfunction "13_13") (pintype "passive"))
    )
    (net (code "382") (name "unconnected-(JP52-Pad14)") (class "Default")
      (node (ref "JP52") (pin "14") (pinfunction "14_14") (pintype "passive"))
    )
    (net (code "383") (name "unconnected-(JP52-Pad15)") (class "Default")
      (node (ref "JP52") (pin "15") (pinfunction "15_15") (pintype "passive"))
    )
    (net (code "384") (name "unconnected-(JP52-Pad16)") (class "Default")
      (node (ref "JP52") (pin "16") (pinfunction "16_16") (pintype "passive"))
    )
    (net (code "385") (name "unconnected-(JP53-Pad2)") (class "Default")
      (node (ref "JP53") (pin "2") (pinfunction "2_2") (pintype "passive"))
    )
    (net (code "386") (name "unconnected-(JP53-Pad3)") (class "Default")
      (node (ref "JP53") (pin "3") (pinfunction "3_3") (pintype "passive"))
    )
    (net (code "387") (name "unconnected-(JP53-Pad4)") (class "Default")
      (node (ref "JP53") (pin "4") (pinfunction "4_4") (pintype "passive"))
    )
    (net (code "388") (name "unconnected-(JP53-Pad5)") (class "Default")
      (node (ref "JP53") (pin "5") (pinfunction "5_5") (pintype "passive"))
    )
    (net (code "389") (name "unconnected-(JP53-Pad6)") (class "Default")
      (node (ref "JP53") (pin "6") (pinfunction "6_6") (pintype "passive"))
    )
    (net (code "390") (name "unconnected-(JP53-Pad7)") (class "Default")
      (node (ref "JP53") (pin "7") (pinfunction "7_7") (pintype "passive"))
    )
    (net (code "391") (name "unconnected-(JP53-Pad8)") (class "Default")
      (node (ref "JP53") (pin "8") (pinfunction "8_8") (pintype "passive"))
    )
    (net (code "392") (name "unconnected-(JP53-Pad9)") (class "Default")
      (node (ref "JP53") (pin "9") (pinfunction "9_9") (pintype "passive"))
    )
    (net (code "393") (name "unconnected-(JP53-Pad10)") (class "Default")
      (node (ref "JP53") (pin "10") (pinfunction "10_10") (pintype "passive"))
    )
    (net (code "394") (name "unconnected-(JP53-Pad11)") (class "Default")
      (node (ref "JP53") (pin "11") (pinfunction "11_11") (pintype "passive"))
    )
    (net (code "395") (name "unconnected-(JP53-Pad12)") (class "Default")
      (node (ref "JP53") (pin "12") (pinfunction "12_12") (pintype "passive"))
    )
    (net (code "396") (name "unconnected-(JP53-Pad13)") (class "Default")
      (node (ref "JP53") (pin "13") (pinfunction "13_13") (pintype "passive"))
    )
    (net (code "397") (name "unconnected-(JP53-Pad14)") (class "Default")
      (node (ref "JP53") (pin "14") (pinfunction "14_14") (pintype "passive"))
    )
    (net (code "398") (name "unconnected-(JP53-Pad15)") (class "Default")
      (node (ref "JP53") (pin "15") (pinfunction "15_15") (pintype "passive"))
    )
    (net (code "399") (name "unconnected-(JP53-Pad16)") (class "Default")
      (node (ref "JP53") (pin "16") (pinfunction "16_16") (pintype "passive"))
    )
    (net (code "400") (name "unconnected-(JP56-Pad2)") (class "Default")
      (node (ref "JP56") (pin "2") (pinfunction "2_2") (pintype "passive"))
    )
    (net (code "401") (name "unconnected-(JP56-Pad3)") (class "Default")
      (node (ref "JP56") (pin "3") (pinfunction "3_3") (pintype "passive"))
    )
    (net (code "402") (name "unconnected-(JP56-Pad4)") (class "Default")
      (node (ref "JP56") (pin "4") (pinfunction "4_4") (pintype "passive"))
    )
    (net (code "403") (name "unconnected-(JP56-Pad5)") (class "Default")
      (node (ref "JP56") (pin "5") (pinfunction "5_5") (pintype "passive"))
    )
    (net (code "404") (name "unconnected-(JP56-Pad6)") (class "Default")
      (node (ref "JP56") (pin "6") (pinfunction "6_6") (pintype "passive"))
    )
    (net (code "405") (name "unconnected-(JP56-Pad7)") (class "Default")
      (node (ref "JP56") (pin "7") (pinfunction "7_7") (pintype "passive"))
    )
    (net (code "406") (name "unconnected-(JP56-Pad8)") (class "Default")
      (node (ref "JP56") (pin "8") (pinfunction "8_8") (pintype "passive"))
    )
    (net (code "407") (name "unconnected-(JP56-Pad9)") (class "Default")
      (node (ref "JP56") (pin "9") (pinfunction "9_9") (pintype "passive"))
    )
    (net (code "408") (name "unconnected-(JP56-Pad10)") (class "Default")
      (node (ref "JP56") (pin "10") (pinfunction "10_10") (pintype "passive"))
    )
    (net (code "409") (name "unconnected-(JP56-Pad11)") (class "Default")
      (node (ref "JP56") (pin "11") (pinfunction "11_11") (pintype "passive"))
    )
    (net (code "410") (name "unconnected-(JP56-Pad12)") (class "Default")
      (node (ref "JP56") (pin "12") (pinfunction "12_12") (pintype "passive"))
    )
    (net (code "411") (name "unconnected-(JP56-Pad13)") (class "Default")
      (node (ref "JP56") (pin "13") (pinfunction "13_13") (pintype "passive"))
    )
    (net (code "412") (name "unconnected-(JP56-Pad14)") (class "Default")
      (node (ref "JP56") (pin "14") (pinfunction "14_14") (pintype "passive"))
    )
    (net (code "413") (name "unconnected-(JP56-Pad15)") (class "Default")
      (node (ref "JP56") (pin "15") (pinfunction "15_15") (pintype "passive"))
    )
    (net (code "414") (name "unconnected-(JP56-Pad16)") (class "Default")
      (node (ref "JP56") (pin "16") (pinfunction "16_16") (pintype "passive"))
    )
    (net (code "415") (name "unconnected-(JP57-Pad2)") (class "Default")
      (node (ref "JP57") (pin "2") (pinfunction "2_2") (pintype "passive"))
    )
    (net (code "416") (name "unconnected-(JP57-Pad3)") (class "Default")
      (node (ref "JP57") (pin "3") (pinfunction "3_3") (pintype "passive"))
    )
    (net (code "417") (name "unconnected-(JP57-Pad4)") (class "Default")
      (node (ref "JP57") (pin "4") (pinfunction "4_4") (pintype "passive"))
    )
    (net (code "418") (name "unconnected-(JP57-Pad5)") (class "Default")
      (node (ref "JP57") (pin "5") (pinfunction "5_5") (pintype "passive"))
    )
    (net (code "419") (name "unconnected-(JP57-Pad6)") (class "Default")
      (node (ref "JP57") (pin "6") (pinfunction "6_6") (pintype "passive"))
    )
    (net (code "420") (name "unconnected-(JP57-Pad7)") (class "Default")
      (node (ref "JP57") (pin "7") (pinfunction "7_7") (pintype "passive"))
    )
    (net (code "421") (name "unconnected-(JP57-Pad8)") (class "Default")
      (node (ref "JP57") (pin "8") (pinfunction "8_8") (pintype "passive"))
    )
    (net (code "422") (name "unconnected-(JP57-Pad9)") (class "Default")
      (node (ref "JP57") (pin "9") (pinfunction "9_9") (pintype "passive"))
    )
    (net (code "423") (name "unconnected-(JP57-Pad10)") (class "Default")
      (node (ref "JP57") (pin "10") (pinfunction "10_10") (pintype "passive"))
    )
    (net (code "424") (name "unconnected-(JP57-Pad11)") (class "Default")
      (node (ref "JP57") (pin "11") (pinfunction "11_11") (pintype "passive"))
    )
    (net (code "425") (name "unconnected-(JP57-Pad12)") (class "Default")
      (node (ref "JP57") (pin "12") (pinfunction "12_12") (pintype "passive"))
    )
    (net (code "426") (name "unconnected-(JP57-Pad13)") (class "Default")
      (node (ref "JP57") (pin "13") (pinfunction "13_13") (pintype "passive"))
    )
    (net (code "427") (name "unconnected-(JP57-Pad14)") (class "Default")
      (node (ref "JP57") (pin "14") (pinfunction "14_14") (pintype "passive"))
    )
    (net (code "428") (name "unconnected-(JP57-Pad15)") (class "Default")
      (node (ref "JP57") (pin "15") (pinfunction "15_15") (pintype "passive"))
    )
    (net (code "429") (name "unconnected-(JP57-Pad16)") (class "Default")
      (node (ref "JP57") (pin "16") (pinfunction "16_16") (pintype "passive"))
    )
    (net (code "430") (name "unconnected-(JP58-Pad2)") (class "Default")
      (node (ref "JP58") (pin "2") (pinfunction "2_2") (pintype "passive"))
    )
    (net (code "431") (name "unconnected-(JP58-Pad3)") (class "Default")
      (node (ref "JP58") (pin "3") (pinfunction "3_3") (pintype "passive"))
    )
    (net (code "432") (name "unconnected-(JP58-Pad4)") (class "Default")
      (node (ref "JP58") (pin "4") (pinfunction "4_4") (pintype "passive"))
    )
    (net (code "433") (name "unconnected-(JP58-Pad5)") (class "Default")
      (node (ref "JP58") (pin "5") (pinfunction "5_5") (pintype "passive"))
    )
    (net (code "434") (name "unconnected-(JP58-Pad6)") (class "Default")
      (node (ref "JP58") (pin "6") (pinfunction "6_6") (pintype "passive"))
    )
    (net (code "435") (name "unconnected-(JP58-Pad7)") (class "Default")
      (node (ref "JP58") (pin "7") (pinfunction "7_7") (pintype "passive"))
    )
    (net (code "436") (name "unconnected-(JP58-Pad8)") (class "Default")
      (node (ref "JP58") (pin "8") (pinfunction "8_8") (pintype "passive"))
    )
    (net (code "437") (name "unconnected-(JP58-Pad9)") (class "Default")
      (node (ref "JP58") (pin "9") (pinfunction "9_9") (pintype "passive"))
    )
    (net (code "438") (name "unconnected-(JP58-Pad10)") (class "Default")
      (node (ref "JP58") (pin "10") (pinfunction "10_10") (pintype "passive"))
    )
    (net (code "439") (name "unconnected-(JP58-Pad11)") (class "Default")
      (node (ref "JP58") (pin "11") (pinfunction "11_11") (pintype "passive"))
    )
    (net (code "440") (name "unconnected-(JP58-Pad12)") (class "Default")
      (node (ref "JP58") (pin "12") (pinfunction "12_12") (pintype "passive"))
    )
    (net (code "441") (name "unconnected-(JP58-Pad13)") (class "Default")
      (node (ref "JP58") (pin "13") (pinfunction "13_13") (pintype "passive"))
    )
    (net (code "442") (name "unconnected-(JP58-Pad14)") (class "Default")
      (node (ref "JP58") (pin "14") (pinfunction "14_14") (pintype "passive"))
    )
    (net (code "443") (name "unconnected-(JP58-Pad15)") (class "Default")
      (node (ref "JP58") (pin "15") (pinfunction "15_15") (pintype "passive"))
    )
    (net (code "444") (name "unconnected-(JP58-Pad16)") (class "Default")
      (node (ref "JP58") (pin "16") (pinfunction "16_16") (pintype "passive"))
    )
    (net (code "445") (name "unconnected-(JP59-Pad2)") (class "Default")
      (node (ref "JP59") (pin "2") (pinfunction "2_2") (pintype "passive"))
    )
    (net (code "446") (name "unconnected-(JP59-Pad3)") (class "Default")
      (node (ref "JP59") (pin "3") (pinfunction "3_3") (pintype "passive"))
    )
    (net (code "447") (name "unconnected-(JP59-Pad4)") (class "Default")
      (node (ref "JP59") (pin "4") (pinfunction "4_4") (pintype "passive"))
    )
    (net (code "448") (name "unconnected-(JP59-Pad5)") (class "Default")
      (node (ref "JP59") (pin "5") (pinfunction "5_5") (pintype "passive"))
    )
    (net (code "449") (name "unconnected-(JP59-Pad6)") (class "Default")
      (node (ref "JP59") (pin "6") (pinfunction "6_6") (pintype "passive"))
    )
    (net (code "450") (name "unconnected-(JP59-Pad7)") (class "Default")
      (node (ref "JP59") (pin "7") (pinfunction "7_7") (pintype "passive"))
    )
    (net (code "451") (name "unconnected-(JP59-Pad8)") (class "Default")
      (node (ref "JP59") (pin "8") (pinfunction "8_8") (pintype "passive"))
    )
    (net (code "452") (name "unconnected-(JP59-Pad9)") (class "Default")
      (node (ref "JP59") (pin "9") (pinfunction "9_9") (pintype "passive"))
    )
    (net (code "453") (name "unconnected-(JP59-Pad10)") (class "Default")
      (node (ref "JP59") (pin "10") (pinfunction "10_10") (pintype "passive"))
    )
    (net (code "454") (name "unconnected-(JP59-Pad11)") (class "Default")
      (node (ref "JP59") (pin "11") (pinfunction "11_11") (pintype "passive"))
    )
    (net (code "455") (name "unconnected-(JP59-Pad12)") (class "Default")
      (node (ref "JP59") (pin "12") (pinfunction "12_12") (pintype "passive"))
    )
    (net (code "456") (name "unconnected-(JP59-Pad13)") (class "Default")
      (node (ref "JP59") (pin "13") (pinfunction "13_13") (pintype "passive"))
    )
    (net (code "457") (name "unconnected-(JP59-Pad14)") (class "Default")
      (node (ref "JP59") (pin "14") (pinfunction "14_14") (pintype "passive"))
    )
    (net (code "458") (name "unconnected-(JP59-Pad15)") (class "Default")
      (node (ref "JP59") (pin "15") (pinfunction "15_15") (pintype "passive"))
    )
    (net (code "459") (name "unconnected-(JP59-Pad16)") (class "Default")
      (node (ref "JP59") (pin "16") (pinfunction "16_16") (pintype "passive"))
    )
    (net (code "460") (name "unconnected-(JP60-Pad2)") (class "Default")
      (node (ref "JP60") (pin "2") (pinfunction "2_2") (pintype "passive"))
    )
    (net (code "461") (name "unconnected-(JP60-Pad3)") (class "Default")
      (node (ref "JP60") (pin "3") (pinfunction "3_3") (pintype "passive"))
    )
    (net (code "462") (name "unconnected-(JP60-Pad4)") (class "Default")
      (node (ref "JP60") (pin "4") (pinfunction "4_4") (pintype "passive"))
    )
    (net (code "463") (name "unconnected-(JP60-Pad5)") (class "Default")
      (node (ref "JP60") (pin "5") (pinfunction "5_5") (pintype "passive"))
    )
    (net (code "464") (name "unconnected-(JP60-Pad6)") (class "Default")
      (node (ref "JP60") (pin "6") (pinfunction "6_6") (pintype "passive"))
    )
    (net (code "465") (name "unconnected-(JP60-Pad7)") (class "Default")
      (node (ref "JP60") (pin "7") (pinfunction "7_7") (pintype "passive"))
    )
    (net (code "466") (name "unconnected-(JP60-Pad8)") (class "Default")
      (node (ref "JP60") (pin "8") (pinfunction "8_8") (pintype "passive"))
    )
    (net (code "467") (name "unconnected-(JP60-Pad9)") (class "Default")
      (node (ref "JP60") (pin "9") (pinfunction "9_9") (pintype "passive"))
    )
    (net (code "468") (name "unconnected-(JP60-Pad10)") (class "Default")
      (node (ref "JP60") (pin "10") (pinfunction "10_10") (pintype "passive"))
    )
    (net (code "469") (name "unconnected-(JP60-Pad11)") (class "Default")
      (node (ref "JP60") (pin "11") (pinfunction "11_11") (pintype "passive"))
    )
    (net (code "470") (name "unconnected-(JP60-Pad12)") (class "Default")
      (node (ref "JP60") (pin "12") (pinfunction "12_12") (pintype "passive"))
    )
    (net (code "471") (name "unconnected-(JP60-Pad13)") (class "Default")
      (node (ref "JP60") (pin "13") (pinfunction "13_13") (pintype "passive"))
    )
    (net (code "472") (name "unconnected-(JP60-Pad14)") (class "Default")
      (node (ref "JP60") (pin "14") (pinfunction "14_14") (pintype "passive"))
    )
    (net (code "473") (name "unconnected-(JP60-Pad15)") (class "Default")
      (node (ref "JP60") (pin "15") (pinfunction "15_15") (pintype "passive"))
    )
    (net (code "474") (name "unconnected-(JP60-Pad16)") (class "Default")
      (node (ref "JP60") (pin "16") (pinfunction "16_16") (pintype "passive"))
    )
    (net (code "475") (name "unconnected-(JP61-Pad2)") (class "Default")
      (node (ref "JP61") (pin "2") (pinfunction "2_2") (pintype "passive"))
    )
    (net (code "476") (name "unconnected-(JP61-Pad3)") (class "Default")
      (node (ref "JP61") (pin "3") (pinfunction "3_3") (pintype "passive"))
    )
    (net (code "477") (name "unconnected-(JP61-Pad4)") (class "Default")
      (node (ref "JP61") (pin "4") (pinfunction "4_4") (pintype "passive"))
    )
    (net (code "478") (name "unconnected-(JP61-Pad5)") (class "Default")
      (node (ref "JP61") (pin "5") (pinfunction "5_5") (pintype "passive"))
    )
    (net (code "479") (name "unconnected-(JP61-Pad6)") (class "Default")
      (node (ref "JP61") (pin "6") (pinfunction "6_6") (pintype "passive"))
    )
    (net (code "480") (name "unconnected-(JP61-Pad7)") (class "Default")
      (node (ref "JP61") (pin "7") (pinfunction "7_7") (pintype "passive"))
    )
    (net (code "481") (name "unconnected-(JP61-Pad8)") (class "Default")
      (node (ref "JP61") (pin "8") (pinfunction "8_8") (pintype "passive"))
    )
    (net (code "482") (name "unconnected-(JP61-Pad9)") (class "Default")
      (node (ref "JP61") (pin "9") (pinfunction "9_9") (pintype "passive"))
    )
    (net (code "483") (name "unconnected-(JP61-Pad10)") (class "Default")
      (node (ref "JP61") (pin "10") (pinfunction "10_10") (pintype "passive"))
    )
    (net (code "484") (name "unconnected-(JP61-Pad11)") (class "Default")
      (node (ref "JP61") (pin "11") (pinfunction "11_11") (pintype "passive"))
    )
    (net (code "485") (name "unconnected-(JP61-Pad12)") (class "Default")
      (node (ref "JP61") (pin "12") (pinfunction "12_12") (pintype "passive"))
    )
    (net (code "486") (name "unconnected-(JP61-Pad13)") (class "Default")
      (node (ref "JP61") (pin "13") (pinfunction "13_13") (pintype "passive"))
    )
    (net (code "487") (name "unconnected-(JP61-Pad14)") (class "Default")
      (node (ref "JP61") (pin "14") (pinfunction "14_14") (pintype "passive"))
    )
    (net (code "488") (name "unconnected-(JP61-Pad15)") (class "Default")
      (node (ref "JP61") (pin "15") (pinfunction "15_15") (pintype "passive"))
    )
    (net (code "489") (name "unconnected-(JP61-Pad16)") (class "Default")
      (node (ref "JP61") (pin "16") (pinfunction "16_16") (pintype "passive"))
    )
    (net (code "490") (name "unconnected-(JP62-Pad2)") (class "Default")
      (node (ref "JP62") (pin "2") (pinfunction "2_2") (pintype "passive"))
    )
    (net (code "491") (name "unconnected-(JP62-Pad3)") (class "Default")
      (node (ref "JP62") (pin "3") (pinfunction "3_3") (pintype "passive"))
    )
    (net (code "492") (name "unconnected-(JP62-Pad4)") (class "Default")
      (node (ref "JP62") (pin "4") (pinfunction "4_4") (pintype "passive"))
    )
    (net (code "493") (name "unconnected-(JP62-Pad5)") (class "Default")
      (node (ref "JP62") (pin "5") (pinfunction "5_5") (pintype "passive"))
    )
    (net (code "494") (name "unconnected-(JP62-Pad6)") (class "Default")
      (node (ref "JP62") (pin "6") (pinfunction "6_6") (pintype "passive"))
    )
    (net (code "495") (name "unconnected-(JP62-Pad7)") (class "Default")
      (node (ref "JP62") (pin "7") (pinfunction "7_7") (pintype "passive"))
    )
    (net (code "496") (name "unconnected-(JP62-Pad8)") (class "Default")
      (node (ref "JP62") (pin "8") (pinfunction "8_8") (pintype "passive"))
    )
    (net (code "497") (name "unconnected-(JP62-Pad9)") (class "Default")
      (node (ref "JP62") (pin "9") (pinfunction "9_9") (pintype "passive"))
    )
    (net (code "498") (name "unconnected-(JP62-Pad10)") (class "Default")
      (node (ref "JP62") (pin "10") (pinfunction "10_10") (pintype "passive"))
    )
    (net (code "499") (name "unconnected-(JP62-Pad11)") (class "Default")
      (node (ref "JP62") (pin "11") (pinfunction "11_11") (pintype "passive"))
    )
    (net (code "500") (name "unconnected-(JP62-Pad12)") (class "Default")
      (node (ref "JP62") (pin "12") (pinfunction "12_12") (pintype "passive"))
    )
    (net (code "501") (name "unconnected-(JP62-Pad13)") (class "Default")
      (node (ref "JP62") (pin "13") (pinfunction "13_13") (pintype "passive"))
    )
    (net (code "502") (name "unconnected-(JP62-Pad14)") (class "Default")
      (node (ref "JP62") (pin "14") (pinfunction "14_14") (pintype "passive"))
    )
    (net (code "503") (name "unconnected-(JP62-Pad15)") (class "Default")
      (node (ref "JP62") (pin "15") (pinfunction "15_15") (pintype "passive"))
    )
    (net (code "504") (name "unconnected-(JP62-Pad16)") (class "Default")
      (node (ref "JP62") (pin "16") (pinfunction "16_16") (pintype "passive"))
    )
    (net (code "505") (name "unconnected-(JP63-Pad2)") (class "Default")
      (node (ref "JP63") (pin "2") (pinfunction "2_2") (pintype "passive"))
    )
    (net (code "506") (name "unconnected-(JP63-Pad3)") (class "Default")
      (node (ref "JP63") (pin "3") (pinfunction "3_3") (pintype "passive"))
    )
    (net (code "507") (name "unconnected-(JP63-Pad4)") (class "Default")
      (node (ref "JP63") (pin "4") (pinfunction "4_4") (pintype "passive"))
    )
    (net (code "508") (name "unconnected-(JP63-Pad5)") (class "Default")
      (node (ref "JP63") (pin "5") (pinfunction "5_5") (pintype "passive"))
    )
    (net (code "509") (name "unconnected-(JP63-Pad6)") (class "Default")
      (node (ref "JP63") (pin "6") (pinfunction "6_6") (pintype "passive"))
    )
    (net (code "510") (name "unconnected-(JP63-Pad7)") (class "Default")
      (node (ref "JP63") (pin "7") (pinfunction "7_7") (pintype "passive"))
    )
    (net (code "511") (name "unconnected-(JP63-Pad8)") (class "Default")
      (node (ref "JP63") (pin "8") (pinfunction "8_8") (pintype "passive"))
    )
    (net (code "512") (name "unconnected-(JP63-Pad9)") (class "Default")
      (node (ref "JP63") (pin "9") (pinfunction "9_9") (pintype "passive"))
    )
    (net (code "513") (name "unconnected-(JP63-Pad10)") (class "Default")
      (node (ref "JP63") (pin "10") (pinfunction "10_10") (pintype "passive"))
    )
    (net (code "514") (name "unconnected-(JP63-Pad11)") (class "Default")
      (node (ref "JP63") (pin "11") (pinfunction "11_11") (pintype "passive"))
    )
    (net (code "515") (name "unconnected-(JP63-Pad12)") (class "Default")
      (node (ref "JP63") (pin "12") (pinfunction "12_12") (pintype "passive"))
    )
    (net (code "516") (name "unconnected-(JP63-Pad13)") (class "Default")
      (node (ref "JP63") (pin "13") (pinfunction "13_13") (pintype "passive"))
    )
    (net (code "517") (name "unconnected-(JP63-Pad14)") (class "Default")
      (node (ref "JP63") (pin "14") (pinfunction "14_14") (pintype "passive"))
    )
    (net (code "518") (name "unconnected-(JP63-Pad15)") (class "Default")
      (node (ref "JP63") (pin "15") (pinfunction "15_15") (pintype "passive"))
    )
    (net (code "519") (name "unconnected-(JP63-Pad16)") (class "Default")
      (node (ref "JP63") (pin "16") (pinfunction "16_16") (pintype "passive"))
    )
    (net (code "520") (name "unconnected-(JP64-Pad2)") (class "Default")
      (node (ref "JP64") (pin "2") (pinfunction "2_2") (pintype "passive"))
    )
    (net (code "521") (name "unconnected-(JP64-Pad3)") (class "Default")
      (node (ref "JP64") (pin "3") (pinfunction "3_3") (pintype "passive"))
    )
    (net (code "522") (name "unconnected-(JP64-Pad4)") (class "Default")
      (node (ref "JP64") (pin "4") (pinfunction "4_4") (pintype "passive"))
    )
    (net (code "523") (name "unconnected-(JP64-Pad5)") (class "Default")
      (node (ref "JP64") (pin "5") (pinfunction "5_5") (pintype "passive"))
    )
    (net (code "524") (name "unconnected-(JP64-Pad6)") (class "Default")
      (node (ref "JP64") (pin "6") (pinfunction "6_6") (pintype "passive"))
    )
    (net (code "525") (name "unconnected-(JP64-Pad7)") (class "Default")
      (node (ref "JP64") (pin "7") (pinfunction "7_7") (pintype "passive"))
    )
    (net (code "526") (name "unconnected-(JP64-Pad8)") (class "Default")
      (node (ref "JP64") (pin "8") (pinfunction "8_8") (pintype "passive"))
    )
    (net (code "527") (name "unconnected-(JP64-Pad9)") (class "Default")
      (node (ref "JP64") (pin "9") (pinfunction "9_9") (pintype "passive"))
    )
    (net (code "528") (name "unconnected-(JP64-Pad10)") (class "Default")
      (node (ref "JP64") (pin "10") (pinfunction "10_10") (pintype "passive"))
    )
    (net (code "529") (name "unconnected-(JP64-Pad11)") (class "Default")
      (node (ref "JP64") (pin "11") (pinfunction "11_11") (pintype "passive"))
    )
    (net (code "530") (name "unconnected-(JP64-Pad12)") (class "Default")
      (node (ref "JP64") (pin "12") (pinfunction "12_12") (pintype "passive"))
    )
    (net (code "531") (name "unconnected-(JP64-Pad13)") (class "Default")
      (node (ref "JP64") (pin "13") (pinfunction "13_13") (pintype "passive"))
    )
    (net (code "532") (name "unconnected-(JP64-Pad14)") (class "Default")
      (node (ref "JP64") (pin "14") (pinfunction "14_14") (pintype "passive"))
    )
    (net (code "533") (name "unconnected-(JP64-Pad15)") (class "Default")
      (node (ref "JP64") (pin "15") (pinfunction "15_15") (pintype "passive"))
    )
    (net (code "534") (name "unconnected-(JP64-Pad16)") (class "Default")
      (node (ref "JP64") (pin "16") (pinfunction "16_16") (pintype "passive"))
    )
    (net (code "535") (name "unconnected-(JP65-Pad2)") (class "Default")
      (node (ref "JP65") (pin "2") (pinfunction "2_2") (pintype "passive"))
    )
    (net (code "536") (name "unconnected-(JP65-Pad3)") (class "Default")
      (node (ref "JP65") (pin "3") (pinfunction "3_3") (pintype "passive"))
    )
    (net (code "537") (name "unconnected-(JP65-Pad4)") (class "Default")
      (node (ref "JP65") (pin "4") (pinfunction "4_4") (pintype "passive"))
    )
    (net (code "538") (name "unconnected-(JP65-Pad5)") (class "Default")
      (node (ref "JP65") (pin "5") (pinfunction "5_5") (pintype "passive"))
    )
    (net (code "539") (name "unconnected-(JP65-Pad6)") (class "Default")
      (node (ref "JP65") (pin "6") (pinfunction "6_6") (pintype "passive"))
    )
    (net (code "540") (name "unconnected-(JP65-Pad7)") (class "Default")
      (node (ref "JP65") (pin "7") (pinfunction "7_7") (pintype "passive"))
    )
    (net (code "541") (name "unconnected-(JP65-Pad8)") (class "Default")
      (node (ref "JP65") (pin "8") (pinfunction "8_8") (pintype "passive"))
    )
    (net (code "542") (name "unconnected-(JP65-Pad9)") (class "Default")
      (node (ref "JP65") (pin "9") (pinfunction "9_9") (pintype "passive"))
    )
    (net (code "543") (name "unconnected-(JP65-Pad10)") (class "Default")
      (node (ref "JP65") (pin "10") (pinfunction "10_10") (pintype "passive"))
    )
    (net (code "544") (name "unconnected-(JP65-Pad11)") (class "Default")
      (node (ref "JP65") (pin "11") (pinfunction "11_11") (pintype "passive"))
    )
    (net (code "545") (name "unconnected-(JP65-Pad12)") (class "Default")
      (node (ref "JP65") (pin "12") (pinfunction "12_12") (pintype "passive"))
    )
    (net (code "546") (name "unconnected-(JP65-Pad13)") (class "Default")
      (node (ref "JP65") (pin "13") (pinfunction "13_13") (pintype "passive"))
    )
    (net (code "547") (name "unconnected-(JP65-Pad14)") (class "Default")
      (node (ref "JP65") (pin "14") (pinfunction "14_14") (pintype "passive"))
    )
    (net (code "548") (name "unconnected-(JP65-Pad15)") (class "Default")
      (node (ref "JP65") (pin "15") (pinfunction "15_15") (pintype "passive"))
    )
    (net (code "549") (name "unconnected-(JP65-Pad16)") (class "Default")
      (node (ref "JP65") (pin "16") (pinfunction "16_16") (pintype "passive"))
    )
    (net (code "550") (name "unconnected-(JP66-Pad2)") (class "Default")
      (node (ref "JP66") (pin "2") (pinfunction "2_2") (pintype "passive"))
    )
    (net (code "551") (name "unconnected-(JP66-Pad3)") (class "Default")
      (node (ref "JP66") (pin "3") (pinfunction "3_3") (pintype "passive"))
    )
    (net (code "552") (name "unconnected-(JP66-Pad4)") (class "Default")
      (node (ref "JP66") (pin "4") (pinfunction "4_4") (pintype "passive"))
    )
    (net (code "553") (name "unconnected-(JP66-Pad5)") (class "Default")
      (node (ref "JP66") (pin "5") (pinfunction "5_5") (pintype "passive"))
    )
    (net (code "554") (name "unconnected-(JP66-Pad6)") (class "Default")
      (node (ref "JP66") (pin "6") (pinfunction "6_6") (pintype "passive"))
    )
    (net (code "555") (name "unconnected-(JP66-Pad7)") (class "Default")
      (node (ref "JP66") (pin "7") (pinfunction "7_7") (pintype "passive"))
    )
    (net (code "556") (name "unconnected-(JP66-Pad8)") (class "Default")
      (node (ref "JP66") (pin "8") (pinfunction "8_8") (pintype "passive"))
    )
    (net (code "557") (name "unconnected-(JP66-Pad9)") (class "Default")
      (node (ref "JP66") (pin "9") (pinfunction "9_9") (pintype "passive"))
    )
    (net (code "558") (name "unconnected-(JP66-Pad10)") (class "Default")
      (node (ref "JP66") (pin "10") (pinfunction "10_10") (pintype "passive"))
    )
    (net (code "559") (name "unconnected-(JP66-Pad11)") (class "Default")
      (node (ref "JP66") (pin "11") (pinfunction "11_11") (pintype "passive"))
    )
    (net (code "560") (name "unconnected-(JP66-Pad12)") (class "Default")
      (node (ref "JP66") (pin "12") (pinfunction "12_12") (pintype "passive"))
    )
    (net (code "561") (name "unconnected-(JP66-Pad13)") (class "Default")
      (node (ref "JP66") (pin "13") (pinfunction "13_13") (pintype "passive"))
    )
    (net (code "562") (name "unconnected-(JP66-Pad14)") (class "Default")
      (node (ref "JP66") (pin "14") (pinfunction "14_14") (pintype "passive"))
    )
    (net (code "563") (name "unconnected-(JP66-Pad15)") (class "Default")
      (node (ref "JP66") (pin "15") (pinfunction "15_15") (pintype "passive"))
    )
    (net (code "564") (name "unconnected-(JP66-Pad16)") (class "Default")
      (node (ref "JP66") (pin "16") (pinfunction "16_16") (pintype "passive"))
    )
    (net (code "565") (name "unconnected-(JP67-Pad2)") (class "Default")
      (node (ref "JP67") (pin "2") (pinfunction "2_2") (pintype "passive"))
    )
    (net (code "566") (name "unconnected-(JP67-Pad3)") (class "Default")
      (node (ref "JP67") (pin "3") (pinfunction "3_3") (pintype "passive"))
    )
    (net (code "567") (name "unconnected-(JP67-Pad4)") (class "Default")
      (node (ref "JP67") (pin "4") (pinfunction "4_4") (pintype "passive"))
    )
    (net (code "568") (name "unconnected-(JP67-Pad5)") (class "Default")
      (node (ref "JP67") (pin "5") (pinfunction "5_5") (pintype "passive"))
    )
    (net (code "569") (name "unconnected-(JP67-Pad6)") (class "Default")
      (node (ref "JP67") (pin "6") (pinfunction "6_6") (pintype "passive"))
    )
    (net (code "570") (name "unconnected-(JP67-Pad7)") (class "Default")
      (node (ref "JP67") (pin "7") (pinfunction "7_7") (pintype "passive"))
    )
    (net (code "571") (name "unconnected-(JP67-Pad8)") (class "Default")
      (node (ref "JP67") (pin "8") (pinfunction "8_8") (pintype "passive"))
    )
    (net (code "572") (name "unconnected-(JP67-Pad9)") (class "Default")
      (node (ref "JP67") (pin "9") (pinfunction "9_9") (pintype "passive"))
    )
    (net (code "573") (name "unconnected-(JP67-Pad10)") (class "Default")
      (node (ref "JP67") (pin "10") (pinfunction "10_10") (pintype "passive"))
    )
    (net (code "574") (name "unconnected-(JP67-Pad11)") (class "Default")
      (node (ref "JP67") (pin "11") (pinfunction "11_11") (pintype "passive"))
    )
    (net (code "575") (name "unconnected-(JP67-Pad12)") (class "Default")
      (node (ref "JP67") (pin "12") (pinfunction "12_12") (pintype "passive"))
    )
    (net (code "576") (name "unconnected-(JP67-Pad13)") (class "Default")
      (node (ref "JP67") (pin "13") (pinfunction "13_13") (pintype "passive"))
    )
    (net (code "577") (name "unconnected-(JP67-Pad14)") (class "Default")
      (node (ref "JP67") (pin "14") (pinfunction "14_14") (pintype "passive"))
    )
    (net (code "578") (name "unconnected-(JP67-Pad15)") (class "Default")
      (node (ref "JP67") (pin "15") (pinfunction "15_15") (pintype "passive"))
    )
    (net (code "579") (name "unconnected-(JP67-Pad16)") (class "Default")
      (node (ref "JP67") (pin "16") (pinfunction "16_16") (pintype "passive"))
    )
    (net (code "580") (name "unconnected-(JP68-Pad2)") (class "Default")
      (node (ref "JP68") (pin "2") (pinfunction "2_2") (pintype "passive"))
    )
    (net (code "581") (name "unconnected-(JP68-Pad3)") (class "Default")
      (node (ref "JP68") (pin "3") (pinfunction "3_3") (pintype "passive"))
    )
    (net (code "582") (name "unconnected-(JP68-Pad4)") (class "Default")
      (node (ref "JP68") (pin "4") (pinfunction "4_4") (pintype "passive"))
    )
    (net (code "583") (name "unconnected-(JP68-Pad5)") (class "Default")
      (node (ref "JP68") (pin "5") (pinfunction "5_5") (pintype "passive"))
    )
    (net (code "584") (name "unconnected-(JP68-Pad6)") (class "Default")
      (node (ref "JP68") (pin "6") (pinfunction "6_6") (pintype "passive"))
    )
    (net (code "585") (name "unconnected-(JP68-Pad7)") (class "Default")
      (node (ref "JP68") (pin "7") (pinfunction "7_7") (pintype "passive"))
    )
    (net (code "586") (name "unconnected-(JP68-Pad8)") (class "Default")
      (node (ref "JP68") (pin "8") (pinfunction "8_8") (pintype "passive"))
    )
    (net (code "587") (name "unconnected-(JP68-Pad9)") (class "Default")
      (node (ref "JP68") (pin "9") (pinfunction "9_9") (pintype "passive"))
    )
    (net (code "588") (name "unconnected-(JP68-Pad10)") (class "Default")
      (node (ref "JP68") (pin "10") (pinfunction "10_10") (pintype "passive"))
    )
    (net (code "589") (name "unconnected-(JP68-Pad11)") (class "Default")
      (node (ref "JP68") (pin "11") (pinfunction "11_11") (pintype "passive"))
    )
    (net (code "590") (name "unconnected-(JP68-Pad12)") (class "Default")
      (node (ref "JP68") (pin "12") (pinfunction "12_12") (pintype "passive"))
    )
    (net (code "591") (name "unconnected-(JP68-Pad13)") (class "Default")
      (node (ref "JP68") (pin "13") (pinfunction "13_13") (pintype "passive"))
    )
    (net (code "592") (name "unconnected-(JP68-Pad14)") (class "Default")
      (node (ref "JP68") (pin "14") (pinfunction "14_14") (pintype "passive"))
    )
    (net (code "593") (name "unconnected-(JP68-Pad15)") (class "Default")
      (node (ref "JP68") (pin "15") (pinfunction "15_15") (pintype "passive"))
    )
    (net (code "594") (name "unconnected-(JP68-Pad16)") (class "Default")
      (node (ref "JP68") (pin "16") (pinfunction "16_16") (pintype "passive"))
    )
    (net (code "595") (name "unconnected-(JP69-Pad2)") (class "Default")
      (node (ref "JP69") (pin "2") (pinfunction "2_2") (pintype "passive"))
    )
    (net (code "596") (name "unconnected-(JP69-Pad3)") (class "Default")
      (node (ref "JP69") (pin "3") (pinfunction "3_3") (pintype "passive"))
    )
    (net (code "597") (name "unconnected-(JP69-Pad4)") (class "Default")
      (node (ref "JP69") (pin "4") (pinfunction "4_4") (pintype "passive"))
    )
    (net (code "598") (name "unconnected-(JP69-Pad5)") (class "Default")
      (node (ref "JP69") (pin "5") (pinfunction "5_5") (pintype "passive"))
    )
    (net (code "599") (name "unconnected-(JP69-Pad6)") (class "Default")
      (node (ref "JP69") (pin "6") (pinfunction "6_6") (pintype "passive"))
    )
    (net (code "600") (name "unconnected-(JP69-Pad7)") (class "Default")
      (node (ref "JP69") (pin "7") (pinfunction "7_7") (pintype "passive"))
    )
    (net (code "601") (name "unconnected-(JP69-Pad8)") (class "Default")
      (node (ref "JP69") (pin "8") (pinfunction "8_8") (pintype "passive"))
    )
    (net (code "602") (name "unconnected-(JP69-Pad9)") (class "Default")
      (node (ref "JP69") (pin "9") (pinfunction "9_9") (pintype "passive"))
    )
    (net (code "603") (name "unconnected-(JP69-Pad10)") (class "Default")
      (node (ref "JP69") (pin "10") (pinfunction "10_10") (pintype "passive"))
    )
    (net (code "604") (name "unconnected-(JP69-Pad11)") (class "Default")
      (node (ref "JP69") (pin "11") (pinfunction "11_11") (pintype "passive"))
    )
    (net (code "605") (name "unconnected-(JP69-Pad12)") (class "Default")
      (node (ref "JP69") (pin "12") (pinfunction "12_12") (pintype "passive"))
    )
    (net (code "606") (name "unconnected-(JP69-Pad13)") (class "Default")
      (node (ref "JP69") (pin "13") (pinfunction "13_13") (pintype "passive"))
    )
    (net (code "607") (name "unconnected-(JP69-Pad14)") (class "Default")
      (node (ref "JP69") (pin "14") (pinfunction "14_14") (pintype "passive"))
    )
    (net (code "608") (name "unconnected-(JP69-Pad15)") (class "Default")
      (node (ref "JP69") (pin "15") (pinfunction "15_15") (pintype "passive"))
    )
    (net (code "609") (name "unconnected-(JP69-Pad16)") (class "Default")
      (node (ref "JP69") (pin "16") (pinfunction "16_16") (pintype "passive"))
    )
    (net (code "610") (name "unconnected-(JP70-Pad2)") (class "Default")
      (node (ref "JP70") (pin "2") (pinfunction "2_2") (pintype "passive"))
    )
    (net (code "611") (name "unconnected-(JP70-Pad3)") (class "Default")
      (node (ref "JP70") (pin "3") (pinfunction "3_3") (pintype "passive"))
    )
    (net (code "612") (name "unconnected-(JP70-Pad4)") (class "Default")
      (node (ref "JP70") (pin "4") (pinfunction "4_4") (pintype "passive"))
    )
    (net (code "613") (name "unconnected-(JP70-Pad5)") (class "Default")
      (node (ref "JP70") (pin "5") (pinfunction "5_5") (pintype "passive"))
    )
    (net (code "614") (name "unconnected-(JP70-Pad6)") (class "Default")
      (node (ref "JP70") (pin "6") (pinfunction "6_6") (pintype "passive"))
    )
    (net (code "615") (name "unconnected-(JP70-Pad7)") (class "Default")
      (node (ref "JP70") (pin "7") (pinfunction "7_7") (pintype "passive"))
    )
    (net (code "616") (name "unconnected-(JP70-Pad8)") (class "Default")
      (node (ref "JP70") (pin "8") (pinfunction "8_8") (pintype "passive"))
    )
    (net (code "617") (name "unconnected-(JP70-Pad9)") (class "Default")
      (node (ref "JP70") (pin "9") (pinfunction "9_9") (pintype "passive"))
    )
    (net (code "618") (name "unconnected-(JP70-Pad10)") (class "Default")
      (node (ref "JP70") (pin "10") (pinfunction "10_10") (pintype "passive"))
    )
    (net (code "619") (name "unconnected-(JP70-Pad11)") (class "Default")
      (node (ref "JP70") (pin "11") (pinfunction "11_11") (pintype "passive"))
    )
    (net (code "620") (name "unconnected-(JP70-Pad12)") (class "Default")
      (node (ref "JP70") (pin "12") (pinfunction "12_12") (pintype "passive"))
    )
    (net (code "621") (name "unconnected-(JP70-Pad13)") (class "Default")
      (node (ref "JP70") (pin "13") (pinfunction "13_13") (pintype "passive"))
    )
    (net (code "622") (name "unconnected-(JP70-Pad14)") (class "Default")
      (node (ref "JP70") (pin "14") (pinfunction "14_14") (pintype "passive"))
    )
    (net (code "623") (name "unconnected-(JP70-Pad15)") (class "Default")
      (node (ref "JP70") (pin "15") (pinfunction "15_15") (pintype "passive"))
    )
    (net (code "624") (name "unconnected-(JP70-Pad16)") (class "Default")
      (node (ref "JP70") (pin "16") (pinfunction "16_16") (pintype "passive"))
    )
  )
)
